# AIMLAB_TESTSTATION_ADC_V1.net
KiCad netlist of a schematic drawn in Altium Designer
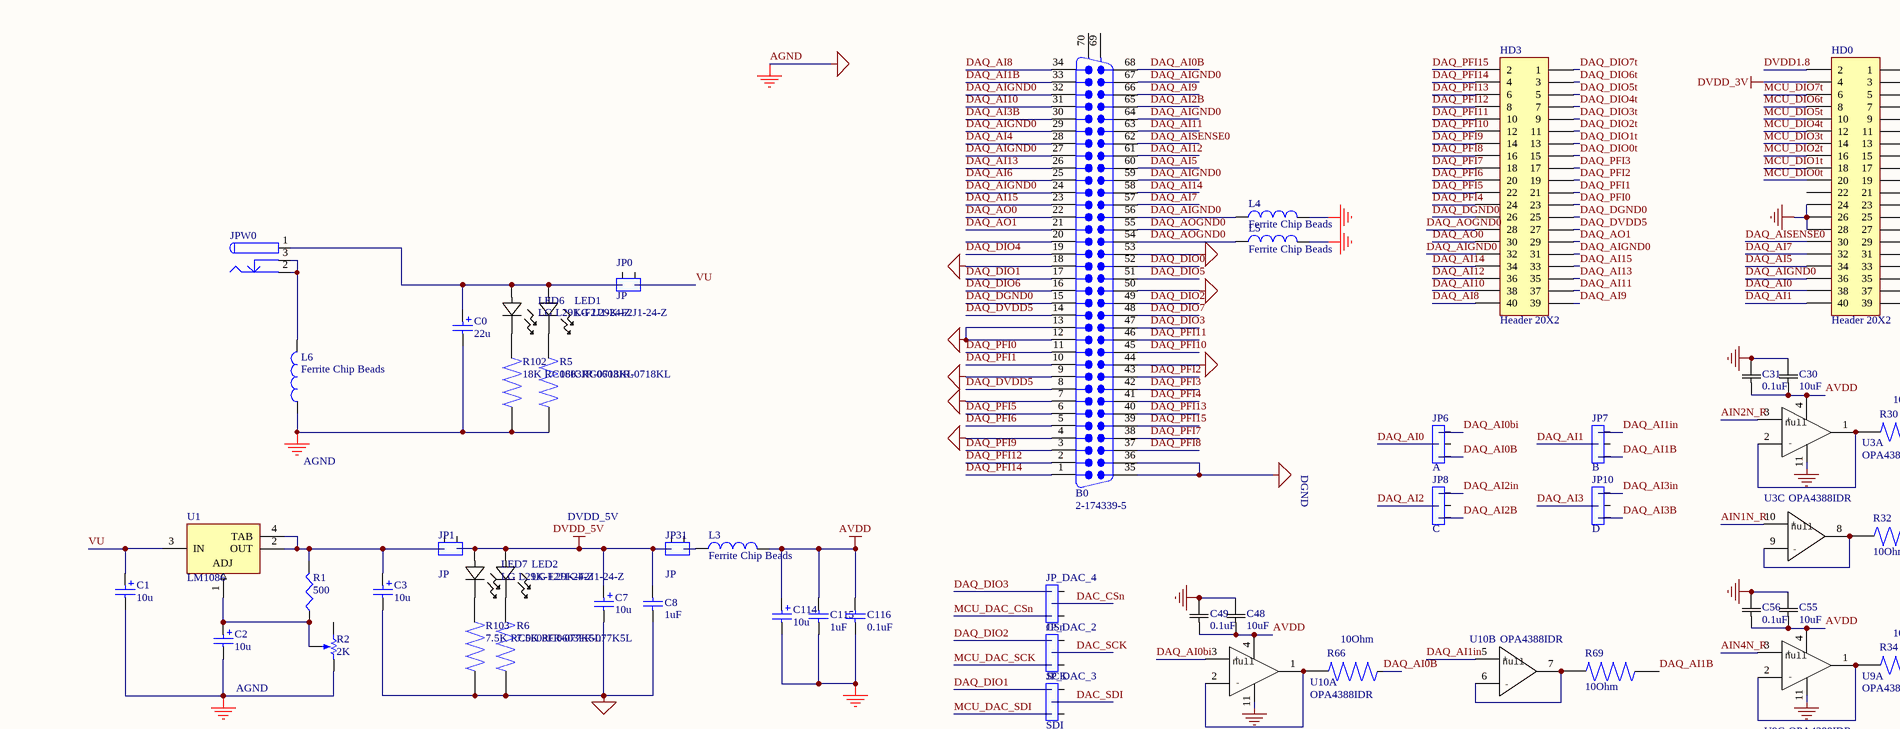
[diagram p0: AIMLAB_TESTSTATION_ADC_V1.schdoc, top left]
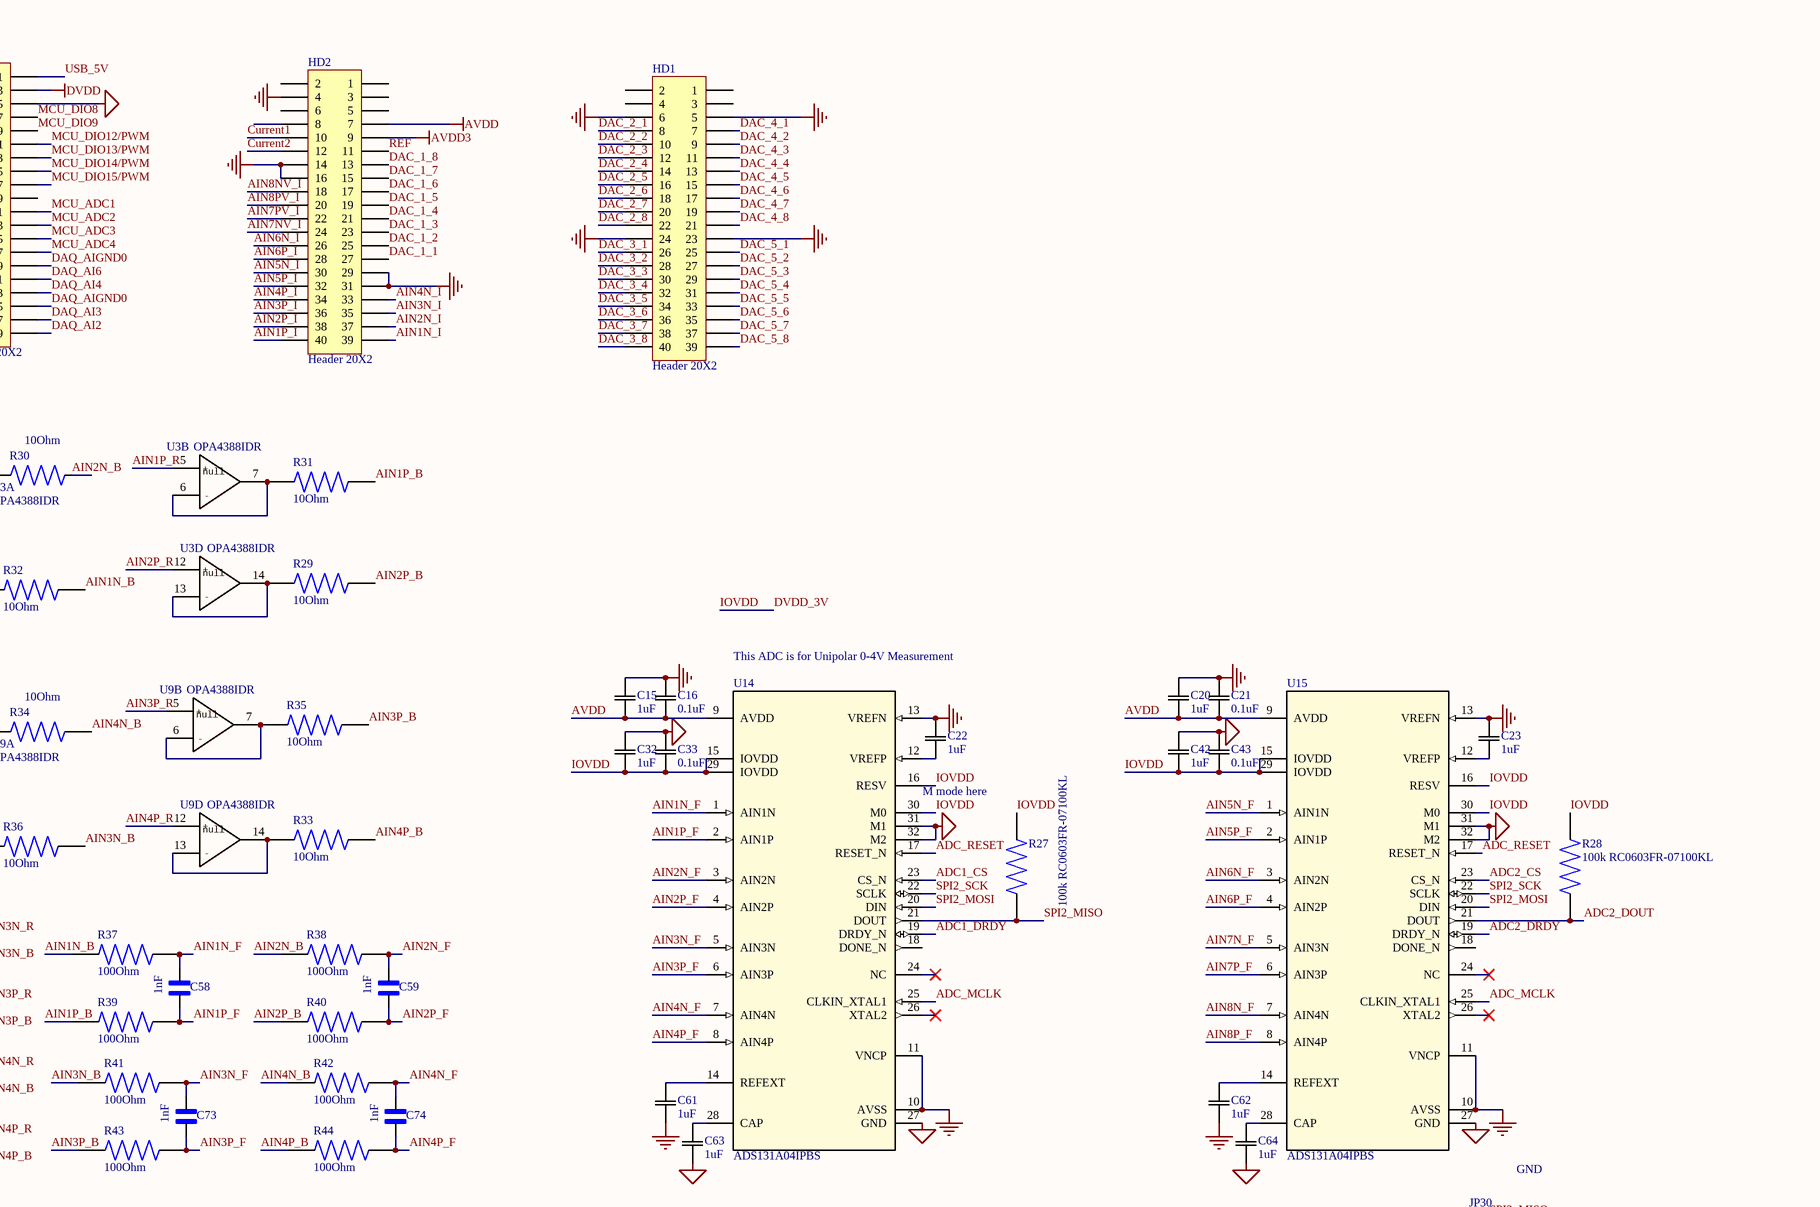
[diagram p1: AIMLAB_TESTSTATION_ADC_V1.schdoc, top right]
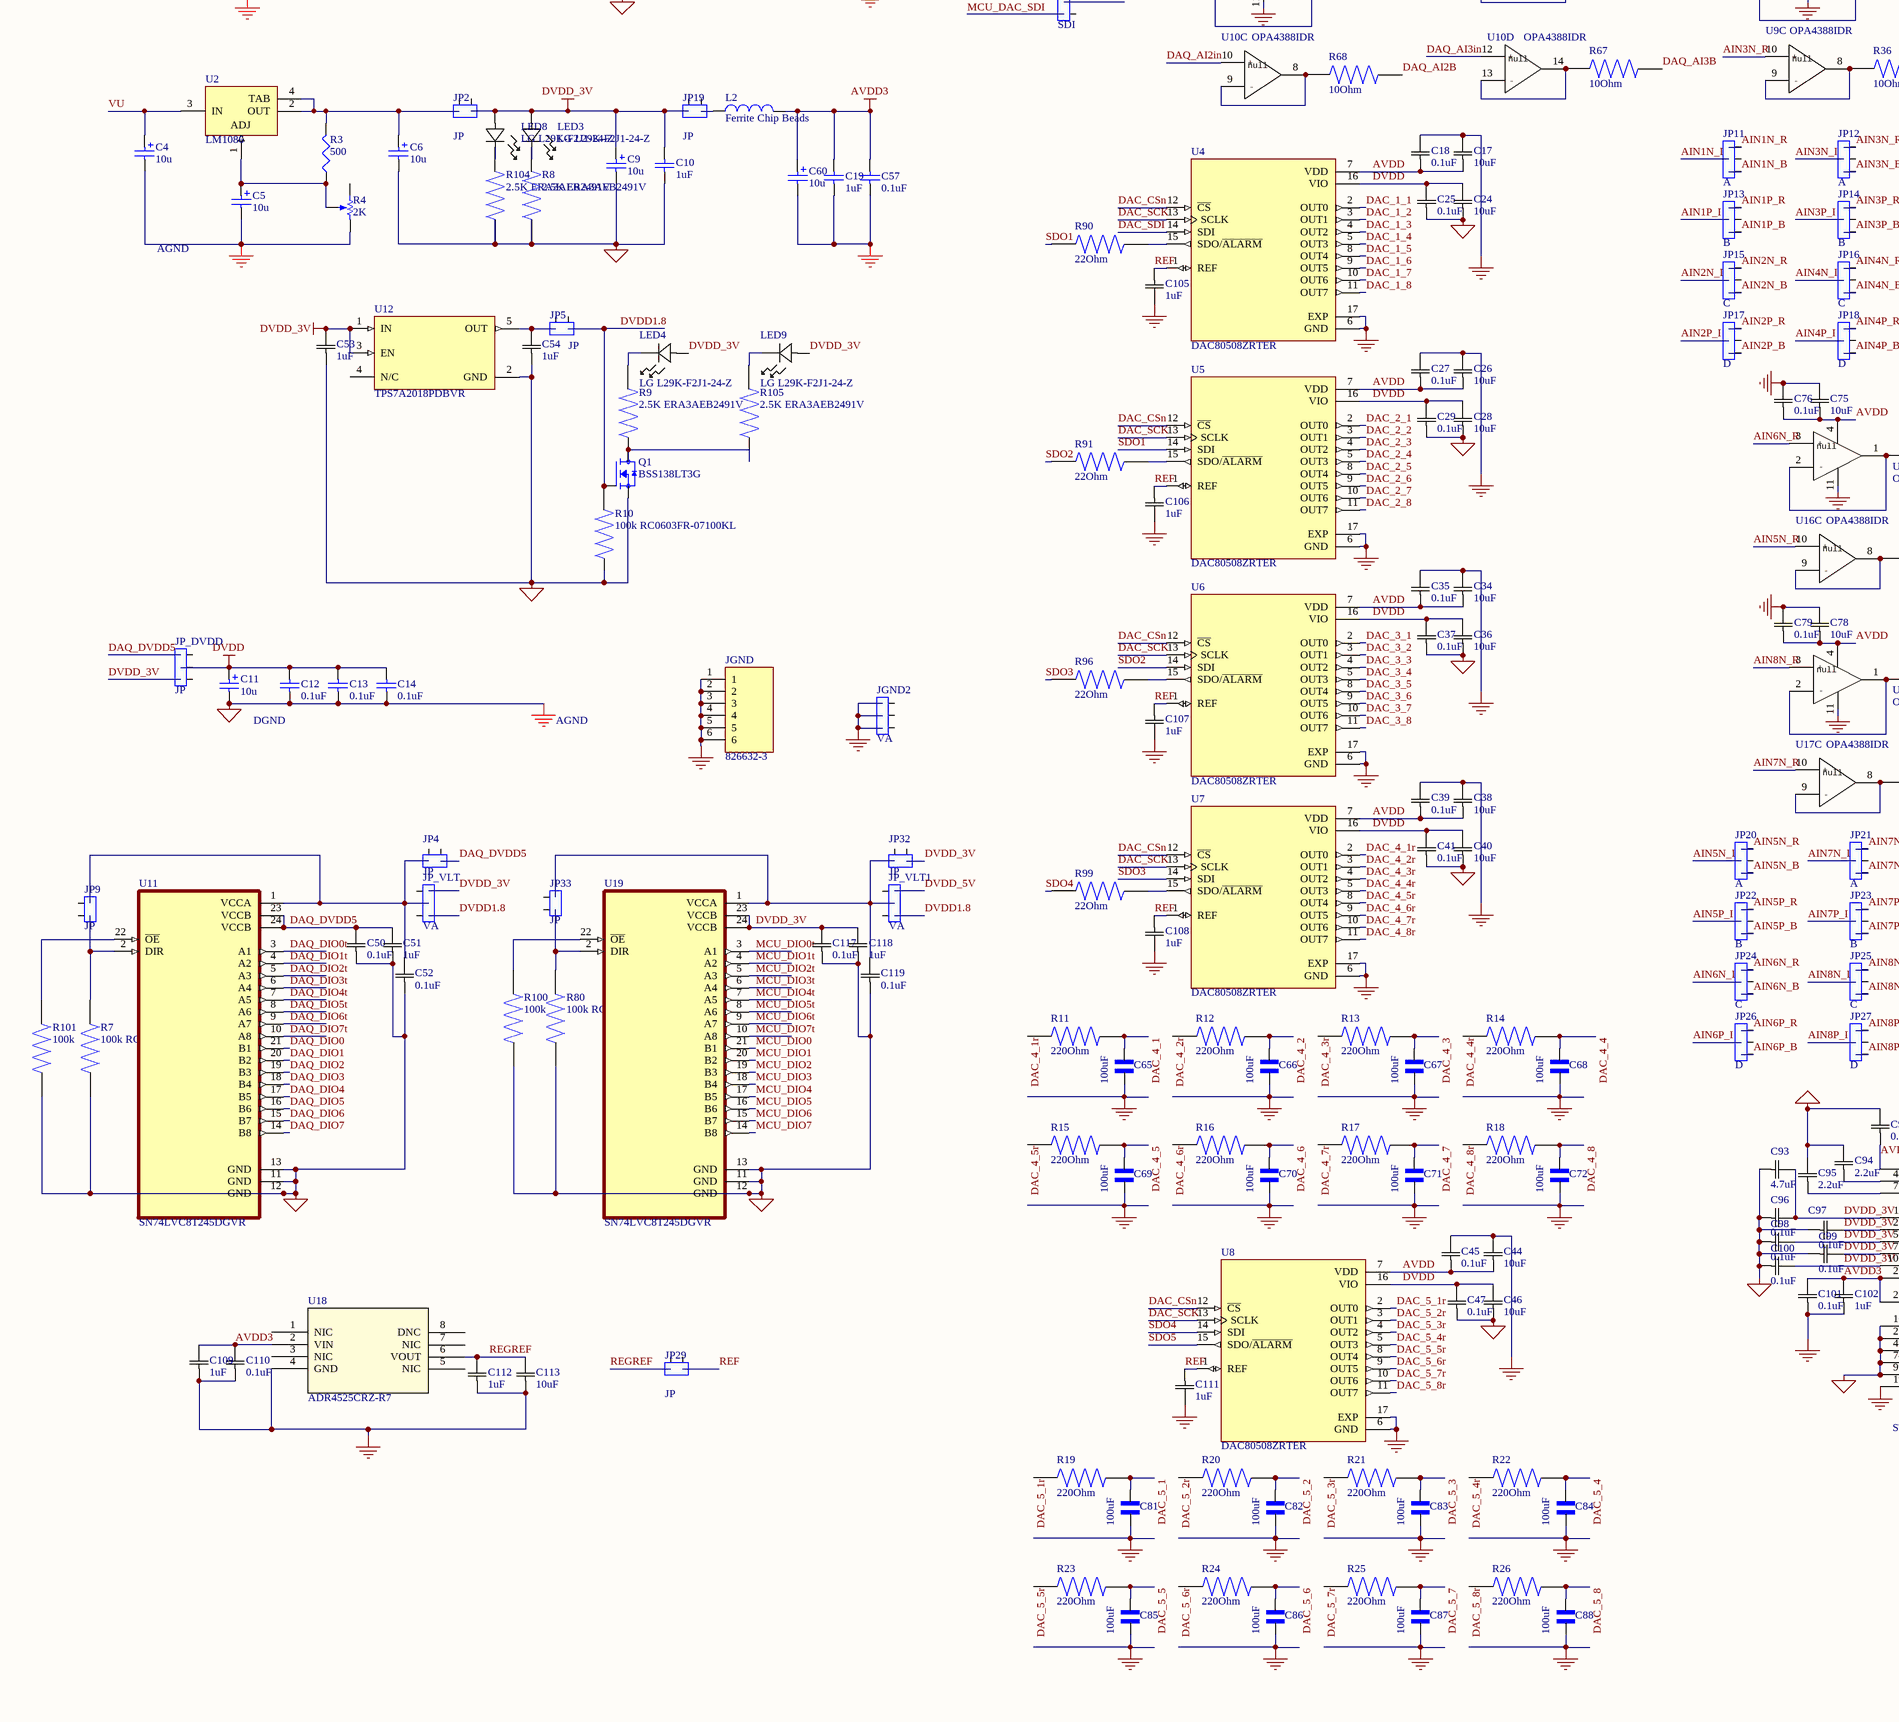
[diagram p2: AIMLAB_TESTSTATION_ADC_V1.schdoc, bottom left]
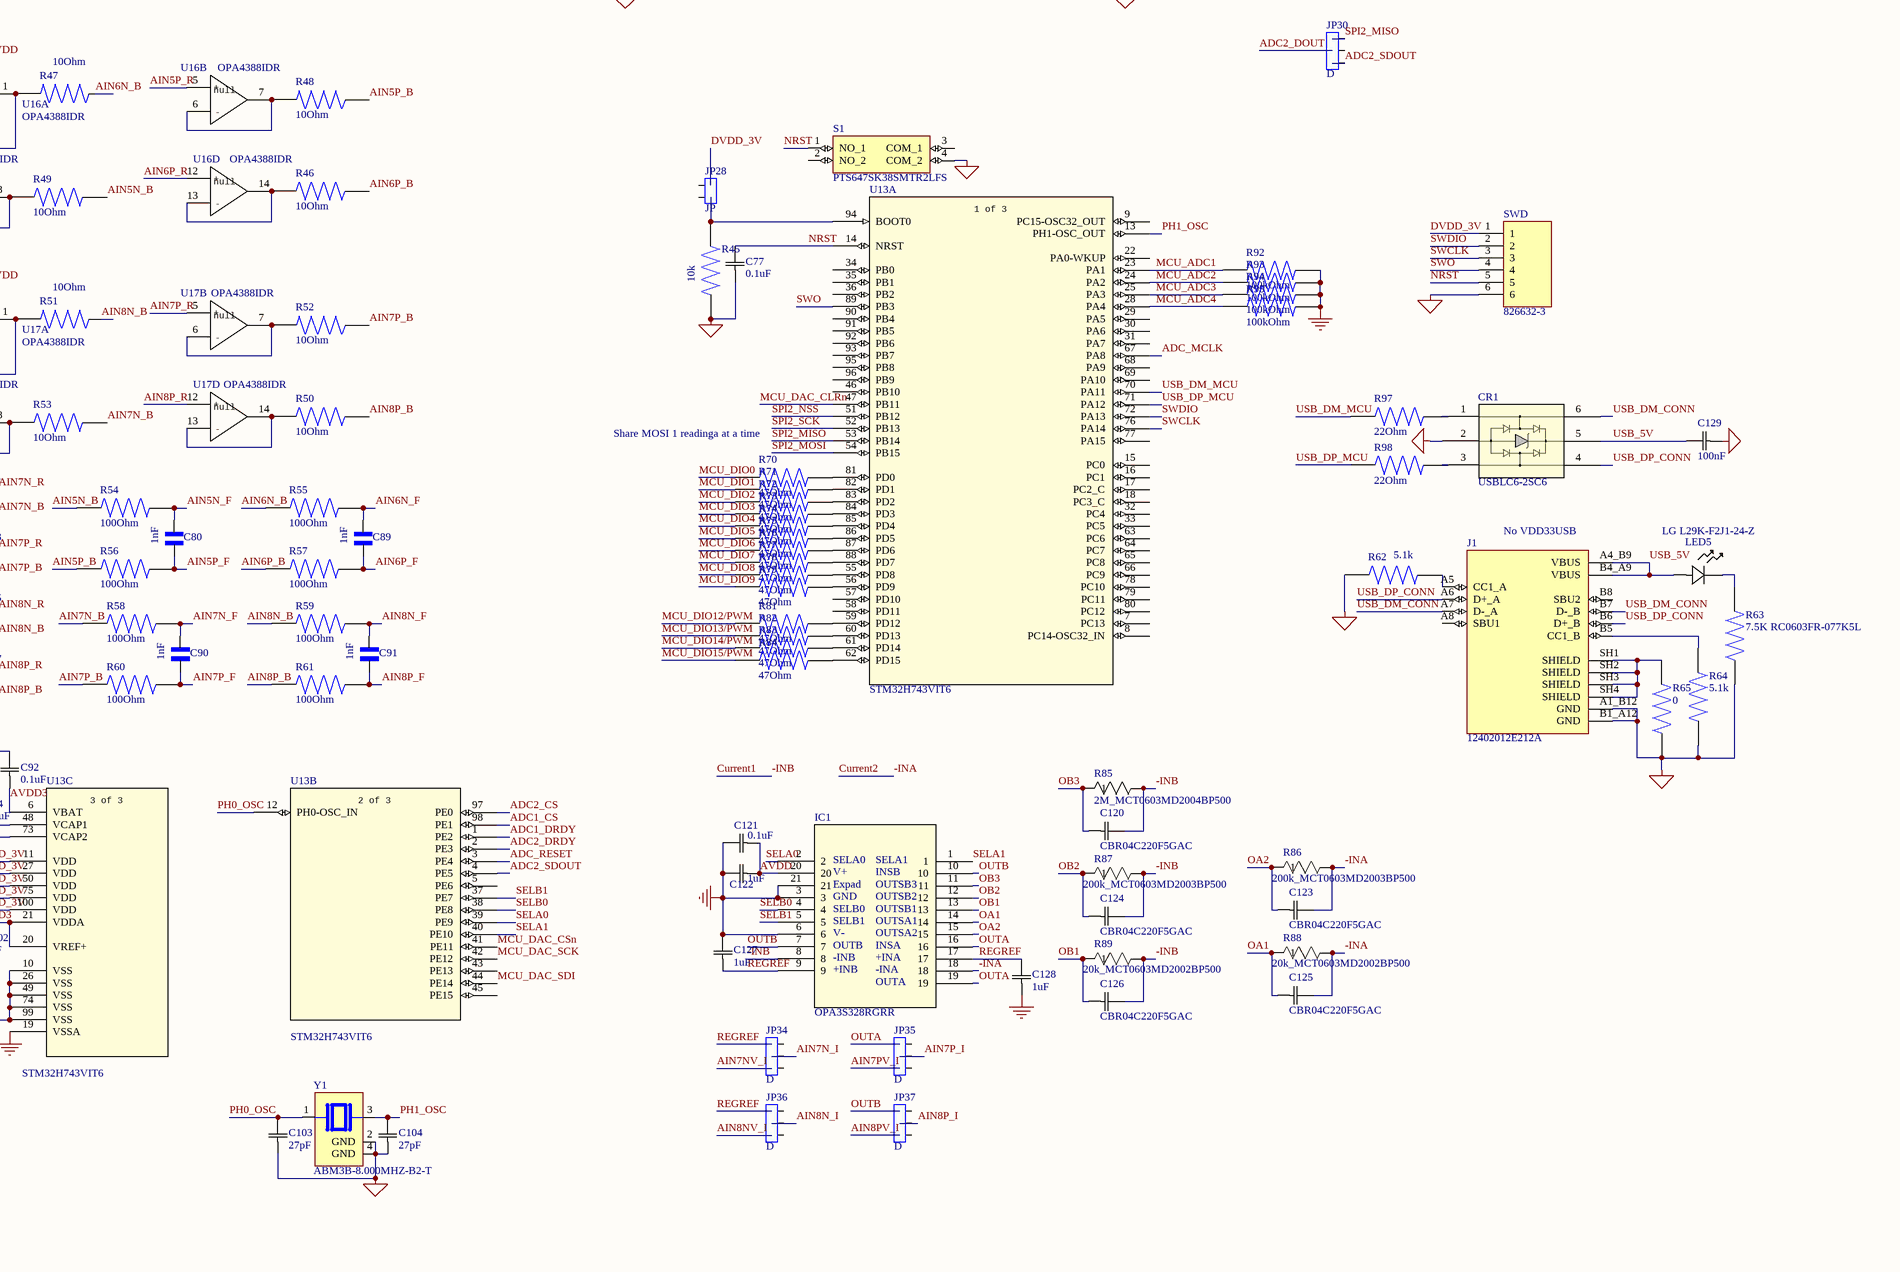
[diagram p3: AIMLAB_TESTSTATION_ADC_V1.schdoc, bottom right]

(export (version "E")
  (design (tool "Eeschema 10.0.6"))
  (components
    (comp (ref "B0")
      (value "2-174339-5")
      (footprint "newconn68:CONN68_5174339_TEC")
      (description "Cap Header, Vertical /M2.5 AMPLIMITE 050 Series II")
      (fields (field (name "PUBLISHER") "Altium Limited"))
      (libsource (lib "AMP D Subminiature 050 Series") (part "2-174339-5"))
    )
    (comp (ref "C0")
      (value "22u")
      (footprint "AimLab_TestStationM-v1.3.1-150922:PolarizedCap")
      (description "Polarized Capacitor (Surface Mount)")
      (fields (field (name "PUBLISHER") "Altium Limited"))
      (libsource (lib "Miscellaneous Devices") (part "Cap Pol3"))
    )
    (comp (ref "C1")
      (value "10u")
      (footprint "AimLab_TestStationM-v1.3.1-150922:PolarizedCap")
      (description "Polarized Capacitor (Surface Mount)")
      (fields (field (name "PUBLISHER") "Altium Limited"))
      (libsource (lib "Miscellaneous Devices") (part "Cap Pol3"))
    )
    (comp (ref "C2")
      (value "10u")
      (footprint "AimLab_TestStationM-v1.3.1-150922:PolarizedCap")
      (description "Polarized Capacitor (Surface Mount)")
      (fields (field (name "PUBLISHER") "Altium Limited"))
      (libsource (lib "Miscellaneous Devices") (part "Cap Pol3"))
    )
    (comp (ref "C3")
      (value "10u")
      (footprint "AimLab_TestStationM-v1.3.1-150922:PolarizedCap")
      (description "Polarized Capacitor (Surface Mount)")
      (fields (field (name "PUBLISHER") "Altium Limited"))
      (libsource (lib "Miscellaneous Devices") (part "Cap Pol3"))
    )
    (comp (ref "C4")
      (value "10u")
      (footprint "AimLab_TestStationM-v1.3.1-150922:PolarizedCap")
      (description "Polarized Capacitor (Surface Mount)")
      (fields (field (name "PUBLISHER") "Altium Limited"))
      (libsource (lib "Miscellaneous Devices") (part "Cap Pol3"))
    )
    (comp (ref "C5")
      (value "10u")
      (footprint "PolarizedCap")
      (description "Polarized Capacitor (Surface Mount)")
      (fields (field (name "PUBLISHER") "Altium Limited"))
      (libsource (lib "Miscellaneous Devices") (part "Cap Pol3"))
    )
    (comp (ref "C6")
      (value "10u")
      (footprint "AimLab_TestStationM-v1.3.1-150922:PolarizedCap")
      (description "Polarized Capacitor (Surface Mount)")
      (fields (field (name "PUBLISHER") "Altium Limited"))
      (libsource (lib "Miscellaneous Devices") (part "Cap Pol3"))
    )
    (comp (ref "C7")
      (value "10u")
      (footprint "AimLab_TestStationM-v1.3.1-150922:PolarizedCap")
      (description "Polarized Capacitor (Surface Mount)")
      (fields (field (name "PUBLISHER") "Altium Limited"))
      (libsource (lib "Miscellaneous Devices") (part "Cap Pol3"))
    )
    (comp (ref "C8")
      (value "1uF")
      (footprint "CAPC2012X140N")
      (description "Capacitor")
      (fields (field (name "PUBLISHER") "Altium Limited"))
      (libsource (lib "Miscellaneous Devices") (part "Cap"))
    )
    (comp (ref "C9")
      (value "10u")
      (footprint "AimLab_TestStationM-v1.3.1-150922:PolarizedCap")
      (description "Polarized Capacitor (Surface Mount)")
      (fields (field (name "PUBLISHER") "Altium Limited"))
      (libsource (lib "Miscellaneous Devices") (part "Cap Pol3"))
    )
    (comp (ref "C10")
      (value "1uF")
      (footprint "CAPC2012X140N")
      (description "Capacitor")
      (fields (field (name "PUBLISHER") "Altium Limited"))
      (libsource (lib "Miscellaneous Devices") (part "Cap"))
    )
    (comp (ref "C11")
      (value "10u")
      (footprint "AimLab_TestStationM-v1.3.1-150922:PolarizedCap")
      (description "Polarized Capacitor (Surface Mount)")
      (fields (field (name "PUBLISHER") "Altium Limited"))
      (libsource (lib "Miscellaneous Devices") (part "Cap Pol3"))
    )
    (comp (ref "C12")
      (value "0.1uF")
      (footprint "CAPC2012X140N")
      (description "Capacitor")
      (fields (field (name "PUBLISHER") "Altium Limited"))
      (libsource (lib "Miscellaneous Devices") (part "Cap"))
    )
    (comp (ref "C13")
      (value "0.1uF")
      (footprint "CAPC2012X140N")
      (description "Capacitor")
      (fields (field (name "PUBLISHER") "Altium Limited"))
      (libsource (lib "Miscellaneous Devices") (part "Cap"))
    )
    (comp (ref "C14")
      (value "0.1uF")
      (footprint "CAPC2012X140N")
      (description "Capacitor")
      (fields (field (name "PUBLISHER") "Altium Limited"))
      (libsource (lib "Miscellaneous Devices") (part "Cap"))
    )
    (comp (ref "C15")
      (value "1uF")
      (footprint "CAPC1608X90")
      (description "No Description Available")
      (fields
        (field (name "MANUFACTURER_PART_NUMBER") "CC0603KRX7R7BB105")
        (field (name "COPYRIGHT") "Copyright (C) 2025 Ultra Librarian. All rights reserved.")
      )
      (libsource (lib "AIMLAB_TESTSTATION-V1.3.1-150922_1") (part "CC0603KRX7R7BB105"))
    )
    (comp (ref "C16")
      (value "0.1uF")
      (footprint "CAPC1608X90")
      (description "No Description Available")
      (fields
        (field (name "MANUFACTURER_PART_NUMBER") "CC0603KRX7R7BB104")
        (field (name "COPYRIGHT") "Copyright (C) 2025 Ultra Librarian. All rights reserved.")
      )
      (libsource (lib "CC0603KRX7R7BB104") (part "CC0603KRX7R7BB104"))
    )
    (comp (ref "C17")
      (value "10uF")
      (footprint "CAPC2012X140N")
      (description "No Description Available")
      (fields
        (field (name "MANUFACTURER_PART_NUMBER") "CL21B106KOQNNNE")
        (field (name "COPYRIGHT") "Copyright (C) 2025 Ultra Librarian. All rights reserved.")
      )
      (libsource (lib "CL21B106KOQNNNE") (part "CL21B106KOQNNNE"))
    )
    (comp (ref "C18")
      (value "0.1uF")
      (footprint "CAPC1608X90")
      (description "No Description Available")
      (fields
        (field (name "MANUFACTURER_PART_NUMBER") "CC0603KRX7R7BB104")
        (field (name "COPYRIGHT") "Copyright (C) 2025 Ultra Librarian. All rights reserved.")
      )
      (libsource (lib "CC0603KRX7R7BB104") (part "CC0603KRX7R7BB104"))
    )
    (comp (ref "C19")
      (value "1uF")
      (footprint "CAPC2012X140N")
      (description "Capacitor")
      (fields (field (name "PUBLISHER") "Altium Limited"))
      (libsource (lib "Miscellaneous Devices") (part "Cap"))
    )
    (comp (ref "C20")
      (value "1uF")
      (footprint "CAPC1608X90")
      (description "No Description Available")
      (fields
        (field (name "MANUFACTURER_PART_NUMBER") "CC0603KRX7R7BB105")
        (field (name "COPYRIGHT") "Copyright (C) 2025 Ultra Librarian. All rights reserved.")
      )
      (libsource (lib "AIMLAB_TESTSTATION-V1.3.1-150922_1") (part "CC0603KRX7R7BB105"))
    )
    (comp (ref "C21")
      (value "0.1uF")
      (footprint "CAPC1608X90")
      (description "No Description Available")
      (fields
        (field (name "MANUFACTURER_PART_NUMBER") "CC0603KRX7R7BB104")
        (field (name "COPYRIGHT") "Copyright (C) 2025 Ultra Librarian. All rights reserved.")
      )
      (libsource (lib "CC0603KRX7R7BB104") (part "CC0603KRX7R7BB104"))
    )
    (comp (ref "C22")
      (value "1uF")
      (footprint "CAPC1608X90")
      (description "No Description Available")
      (fields
        (field (name "MANUFACTURER_PART_NUMBER") "CC0603KRX7R7BB105")
        (field (name "COPYRIGHT") "Copyright (C) 2025 Ultra Librarian. All rights reserved.")
      )
      (libsource (lib "AIMLAB_TESTSTATION-V1.3.1-150922_1") (part "CC0603KRX7R7BB105"))
    )
    (comp (ref "C23")
      (value "1uF")
      (footprint "CAPC1608X90")
      (description "No Description Available")
      (fields
        (field (name "MANUFACTURER_PART_NUMBER") "CC0603KRX7R7BB105")
        (field (name "COPYRIGHT") "Copyright (C) 2025 Ultra Librarian. All rights reserved.")
      )
      (libsource (lib "AIMLAB_TESTSTATION-V1.3.1-150922_1") (part "CC0603KRX7R7BB105"))
    )
    (comp (ref "C24")
      (value "10uF")
      (footprint "CAPC2012X140N")
      (description "No Description Available")
      (fields
        (field (name "MANUFACTURER_PART_NUMBER") "CL21B106KOQNNNE")
        (field (name "COPYRIGHT") "Copyright (C) 2025 Ultra Librarian. All rights reserved.")
      )
      (libsource (lib "CL21B106KOQNNNE") (part "CL21B106KOQNNNE"))
    )
    (comp (ref "C25")
      (value "0.1uF")
      (footprint "CAPC1608X90")
      (description "No Description Available")
      (fields
        (field (name "MANUFACTURER_PART_NUMBER") "CC0603KRX7R7BB104")
        (field (name "COPYRIGHT") "Copyright (C) 2025 Ultra Librarian. All rights reserved.")
      )
      (libsource (lib "CC0603KRX7R7BB104") (part "CC0603KRX7R7BB104"))
    )
    (comp (ref "C26")
      (value "10uF")
      (footprint "CAPC2012X140N")
      (description "No Description Available")
      (fields
        (field (name "MANUFACTURER_PART_NUMBER") "CL21B106KOQNNNE")
        (field (name "COPYRIGHT") "Copyright (C) 2025 Ultra Librarian. All rights reserved.")
      )
      (libsource (lib "CL21B106KOQNNNE") (part "CL21B106KOQNNNE"))
    )
    (comp (ref "C27")
      (value "0.1uF")
      (footprint "CAPC1608X90")
      (description "No Description Available")
      (fields
        (field (name "MANUFACTURER_PART_NUMBER") "CC0603KRX7R7BB104")
        (field (name "COPYRIGHT") "Copyright (C) 2025 Ultra Librarian. All rights reserved.")
      )
      (libsource (lib "CC0603KRX7R7BB104") (part "CC0603KRX7R7BB104"))
    )
    (comp (ref "C28")
      (value "10uF")
      (footprint "CAPC2012X140N")
      (description "No Description Available")
      (fields
        (field (name "MANUFACTURER_PART_NUMBER") "CL21B106KOQNNNE")
        (field (name "COPYRIGHT") "Copyright (C) 2025 Ultra Librarian. All rights reserved.")
      )
      (libsource (lib "CL21B106KOQNNNE") (part "CL21B106KOQNNNE"))
    )
    (comp (ref "C29")
      (value "0.1uF")
      (footprint "CAPC1608X90")
      (description "No Description Available")
      (fields
        (field (name "MANUFACTURER_PART_NUMBER") "CC0603KRX7R7BB104")
        (field (name "COPYRIGHT") "Copyright (C) 2025 Ultra Librarian. All rights reserved.")
      )
      (libsource (lib "CC0603KRX7R7BB104") (part "CC0603KRX7R7BB104"))
    )
    (comp (ref "C30")
      (value "10uF")
      (footprint "CAPC2012X140N")
      (description "No Description Available")
      (fields
        (field (name "MANUFACTURER_PART_NUMBER") "CL21B106KOQNNNE")
        (field (name "COPYRIGHT") "Copyright (C) 2025 Ultra Librarian. All rights reserved.")
      )
      (libsource (lib "CL21B106KOQNNNE") (part "CL21B106KOQNNNE"))
    )
    (comp (ref "C31")
      (value "0.1uF")
      (footprint "CAPC1608X90")
      (description "No Description Available")
      (fields
        (field (name "MANUFACTURER_PART_NUMBER") "CC0603KRX7R7BB104")
        (field (name "COPYRIGHT") "Copyright (C) 2025 Ultra Librarian. All rights reserved.")
      )
      (libsource (lib "CC0603KRX7R7BB104") (part "CC0603KRX7R7BB104"))
    )
    (comp (ref "C32")
      (value "1uF")
      (footprint "CAPC1608X90")
      (description "No Description Available")
      (fields
        (field (name "MANUFACTURER_PART_NUMBER") "CC0603KRX7R7BB105")
        (field (name "COPYRIGHT") "Copyright (C) 2025 Ultra Librarian. All rights reserved.")
      )
      (libsource (lib "AIMLAB_TESTSTATION-V1.3.1-150922_1") (part "CC0603KRX7R7BB105"))
    )
    (comp (ref "C33")
      (value "0.1uF")
      (footprint "CAPC1608X90")
      (description "No Description Available")
      (fields
        (field (name "MANUFACTURER_PART_NUMBER") "CC0603KRX7R7BB104")
        (field (name "COPYRIGHT") "Copyright (C) 2025 Ultra Librarian. All rights reserved.")
      )
      (libsource (lib "CC0603KRX7R7BB104") (part "CC0603KRX7R7BB104"))
    )
    (comp (ref "C34")
      (value "10uF")
      (footprint "CAPC2012X140N")
      (description "No Description Available")
      (fields
        (field (name "MANUFACTURER_PART_NUMBER") "CL21B106KOQNNNE")
        (field (name "COPYRIGHT") "Copyright (C) 2025 Ultra Librarian. All rights reserved.")
      )
      (libsource (lib "CL21B106KOQNNNE") (part "CL21B106KOQNNNE"))
    )
    (comp (ref "C35")
      (value "0.1uF")
      (footprint "CAPC1608X90")
      (description "No Description Available")
      (fields
        (field (name "MANUFACTURER_PART_NUMBER") "CC0603KRX7R7BB104")
        (field (name "COPYRIGHT") "Copyright (C) 2025 Ultra Librarian. All rights reserved.")
      )
      (libsource (lib "CC0603KRX7R7BB104") (part "CC0603KRX7R7BB104"))
    )
    (comp (ref "C36")
      (value "10uF")
      (footprint "CAPC2012X140N")
      (description "No Description Available")
      (fields
        (field (name "MANUFACTURER_PART_NUMBER") "CL21B106KOQNNNE")
        (field (name "COPYRIGHT") "Copyright (C) 2025 Ultra Librarian. All rights reserved.")
      )
      (libsource (lib "CL21B106KOQNNNE") (part "CL21B106KOQNNNE"))
    )
    (comp (ref "C37")
      (value "0.1uF")
      (footprint "CAPC1608X90")
      (description "No Description Available")
      (fields
        (field (name "MANUFACTURER_PART_NUMBER") "CC0603KRX7R7BB104")
        (field (name "COPYRIGHT") "Copyright (C) 2025 Ultra Librarian. All rights reserved.")
      )
      (libsource (lib "CC0603KRX7R7BB104") (part "CC0603KRX7R7BB104"))
    )
    (comp (ref "C38")
      (value "10uF")
      (footprint "CAPC2012X140N")
      (description "No Description Available")
      (fields
        (field (name "MANUFACTURER_PART_NUMBER") "CL21B106KOQNNNE")
        (field (name "COPYRIGHT") "Copyright (C) 2025 Ultra Librarian. All rights reserved.")
      )
      (libsource (lib "CL21B106KOQNNNE") (part "CL21B106KOQNNNE"))
    )
    (comp (ref "C39")
      (value "0.1uF")
      (footprint "CAPC1608X90")
      (description "No Description Available")
      (fields
        (field (name "MANUFACTURER_PART_NUMBER") "CC0603KRX7R7BB104")
        (field (name "COPYRIGHT") "Copyright (C) 2025 Ultra Librarian. All rights reserved.")
      )
      (libsource (lib "CC0603KRX7R7BB104") (part "CC0603KRX7R7BB104"))
    )
    (comp (ref "C40")
      (value "10uF")
      (footprint "CAPC2012X140N")
      (description "No Description Available")
      (fields
        (field (name "MANUFACTURER_PART_NUMBER") "CL21B106KOQNNNE")
        (field (name "COPYRIGHT") "Copyright (C) 2025 Ultra Librarian. All rights reserved.")
      )
      (libsource (lib "CL21B106KOQNNNE") (part "CL21B106KOQNNNE"))
    )
    (comp (ref "C41")
      (value "0.1uF")
      (footprint "CAPC1608X90")
      (description "No Description Available")
      (fields
        (field (name "MANUFACTURER_PART_NUMBER") "CC0603KRX7R7BB104")
        (field (name "COPYRIGHT") "Copyright (C) 2025 Ultra Librarian. All rights reserved.")
      )
      (libsource (lib "CC0603KRX7R7BB104") (part "CC0603KRX7R7BB104"))
    )
    (comp (ref "C42")
      (value "1uF")
      (footprint "CAPC1608X90")
      (description "No Description Available")
      (fields
        (field (name "MANUFACTURER_PART_NUMBER") "CC0603KRX7R7BB105")
        (field (name "COPYRIGHT") "Copyright (C) 2025 Ultra Librarian. All rights reserved.")
      )
      (libsource (lib "AIMLAB_TESTSTATION-V1.3.1-150922_1") (part "CC0603KRX7R7BB105"))
    )
    (comp (ref "C43")
      (value "0.1uF")
      (footprint "CAPC1608X90")
      (description "No Description Available")
      (fields
        (field (name "MANUFACTURER_PART_NUMBER") "CC0603KRX7R7BB104")
        (field (name "COPYRIGHT") "Copyright (C) 2025 Ultra Librarian. All rights reserved.")
      )
      (libsource (lib "CC0603KRX7R7BB104") (part "CC0603KRX7R7BB104"))
    )
    (comp (ref "C44")
      (value "10uF")
      (footprint "CAPC2012X140N")
      (description "No Description Available")
      (fields
        (field (name "MANUFACTURER_PART_NUMBER") "CL21B106KOQNNNE")
        (field (name "COPYRIGHT") "Copyright (C) 2025 Ultra Librarian. All rights reserved.")
      )
      (libsource (lib "CL21B106KOQNNNE") (part "CL21B106KOQNNNE"))
    )
    (comp (ref "C45")
      (value "0.1uF")
      (footprint "CAPC1608X90")
      (description "No Description Available")
      (fields
        (field (name "MANUFACTURER_PART_NUMBER") "CC0603KRX7R7BB104")
        (field (name "COPYRIGHT") "Copyright (C) 2025 Ultra Librarian. All rights reserved.")
      )
      (libsource (lib "CC0603KRX7R7BB104") (part "CC0603KRX7R7BB104"))
    )
    (comp (ref "C46")
      (value "10uF")
      (footprint "CAPC2012X140N")
      (description "No Description Available")
      (fields
        (field (name "MANUFACTURER_PART_NUMBER") "CL21B106KOQNNNE")
        (field (name "COPYRIGHT") "Copyright (C) 2025 Ultra Librarian. All rights reserved.")
      )
      (libsource (lib "CL21B106KOQNNNE") (part "CL21B106KOQNNNE"))
    )
    (comp (ref "C47")
      (value "0.1uF")
      (footprint "CAPC1608X90")
      (description "No Description Available")
      (fields
        (field (name "MANUFACTURER_PART_NUMBER") "CC0603KRX7R7BB104")
        (field (name "COPYRIGHT") "Copyright (C) 2025 Ultra Librarian. All rights reserved.")
      )
      (libsource (lib "CC0603KRX7R7BB104") (part "CC0603KRX7R7BB104"))
    )
    (comp (ref "C48")
      (value "10uF")
      (footprint "CAPC2012X140N")
      (description "No Description Available")
      (fields
        (field (name "MANUFACTURER_PART_NUMBER") "CL21B106KOQNNNE")
        (field (name "COPYRIGHT") "Copyright (C) 2025 Ultra Librarian. All rights reserved.")
      )
      (libsource (lib "CL21B106KOQNNNE") (part "CL21B106KOQNNNE"))
    )
    (comp (ref "C49")
      (value "0.1uF")
      (footprint "CAPC1608X90")
      (description "No Description Available")
      (fields
        (field (name "MANUFACTURER_PART_NUMBER") "CC0603KRX7R7BB104")
        (field (name "COPYRIGHT") "Copyright (C) 2025 Ultra Librarian. All rights reserved.")
      )
      (libsource (lib "CC0603KRX7R7BB104") (part "CC0603KRX7R7BB104"))
    )
    (comp (ref "C50")
      (value "0.1uF")
      (footprint "CAPC1608X90")
      (description "No Description Available")
      (fields
        (field (name "MANUFACTURER_PART_NUMBER") "CC0603KRX7R7BB104")
        (field (name "COPYRIGHT") "Copyright (C) 2025 Ultra Librarian. All rights reserved.")
      )
      (libsource (lib "AIMLAB_TESTSTATION-V1.3.1-150922_1") (part "CC0603KRX7R7BB104"))
    )
    (comp (ref "C51")
      (value "1uF")
      (footprint "CAPC1608X90")
      (description "No Description Available")
      (fields
        (field (name "MANUFACTURER_PART_NUMBER") "CC0603KRX7R7BB105")
        (field (name "COPYRIGHT") "Copyright (C) 2025 Ultra Librarian. All rights reserved.")
      )
      (libsource (lib "AIMLAB_TESTSTATION-V1.3.1-150922_1") (part "CC0603KRX7R7BB105"))
    )
    (comp (ref "C52")
      (value "0.1uF")
      (footprint "CAPC1608X90")
      (description "No Description Available")
      (fields
        (field (name "MANUFACTURER_PART_NUMBER") "CC0603KRX7R7BB104")
        (field (name "COPYRIGHT") "Copyright (C) 2025 Ultra Librarian. All rights reserved.")
      )
      (libsource (lib "AIMLAB_TESTSTATION-V1.3.1-150922_1") (part "CC0603KRX7R7BB104"))
    )
    (comp (ref "C53")
      (value "1uF")
      (footprint "CAPC2012X140N")
      (description "No Description Available")
      (fields
        (field (name "MANUFACTURER_PART_NUMBER") "CC0603KRX7R7BB105")
        (field (name "COPYRIGHT") "Copyright (C) 2025 Ultra Librarian. All rights reserved.")
      )
      (libsource (lib "CC0603KRX7R7BB105") (part "CC0603KRX7R7BB105"))
    )
    (comp (ref "C54")
      (value "1uF")
      (footprint "CAPC2012X140N")
      (description "No Description Available")
      (fields
        (field (name "MANUFACTURER_PART_NUMBER") "CC0603KRX7R7BB105")
        (field (name "COPYRIGHT") "Copyright (C) 2025 Ultra Librarian. All rights reserved.")
      )
      (libsource (lib "CC0603KRX7R7BB105") (part "CC0603KRX7R7BB105"))
    )
    (comp (ref "C55")
      (value "10uF")
      (footprint "CAPC2012X140N")
      (description "No Description Available")
      (fields
        (field (name "MANUFACTURER_PART_NUMBER") "CL21B106KOQNNNE")
        (field (name "COPYRIGHT") "Copyright (C) 2025 Ultra Librarian. All rights reserved.")
      )
      (libsource (lib "CL21B106KOQNNNE") (part "CL21B106KOQNNNE"))
    )
    (comp (ref "C56")
      (value "0.1uF")
      (footprint "CAPC1608X90")
      (description "No Description Available")
      (fields
        (field (name "MANUFACTURER_PART_NUMBER") "CC0603KRX7R7BB104")
        (field (name "COPYRIGHT") "Copyright (C) 2025 Ultra Librarian. All rights reserved.")
      )
      (libsource (lib "CC0603KRX7R7BB104") (part "CC0603KRX7R7BB104"))
    )
    (comp (ref "C57")
      (value "0.1uF")
      (footprint "CAPC2012X140N")
      (description "Capacitor")
      (fields (field (name "PUBLISHER") "Altium Limited"))
      (libsource (lib "Miscellaneous Devices") (part "Cap"))
    )
    (comp (ref "C58")
      (value "1nF")
      (footprint "CAPC2012X145N")
      (description "100 ÂµF Â±20% 6.3V Ceramic Capacitor X5R 0805 (2012 Metric)")
      (fields (field (name "MF") "Murata") (field (name "MP") "GRM21BR60J107ME15L"))
      (libsource (lib "GRM21BR60J107ME15L") (part "GRM21BR60J107ME15L"))
    )
    (comp (ref "C59")
      (value "1nF")
      (footprint "CAPC2012X145N")
      (description "100 ÂµF Â±20% 6.3V Ceramic Capacitor X5R 0805 (2012 Metric)")
      (fields (field (name "MF") "Murata") (field (name "MP") "GRM21BR60J107ME15L"))
      (libsource (lib "GRM21BR60J107ME15L") (part "GRM21BR60J107ME15L"))
    )
    (comp (ref "C60")
      (value "10u")
      (footprint "AimLab_TestStationM-v1.3.1-150922:PolarizedCap")
      (description "Polarized Capacitor (Surface Mount)")
      (fields (field (name "PUBLISHER") "Altium Limited"))
      (libsource (lib "Miscellaneous Devices") (part "Cap Pol3"))
    )
    (comp (ref "C61")
      (value "1uF")
      (footprint "CAPC1608X90")
      (description "No Description Available")
      (fields
        (field (name "MANUFACTURER_PART_NUMBER") "CC0603KRX7R7BB105")
        (field (name "COPYRIGHT") "Copyright (C) 2025 Ultra Librarian. All rights reserved.")
      )
      (libsource (lib "AIMLAB_TESTSTATION-V1.3.1-150922_1") (part "CC0603KRX7R7BB105"))
    )
    (comp (ref "C62")
      (value "1uF")
      (footprint "CAPC1608X90")
      (description "No Description Available")
      (fields
        (field (name "MANUFACTURER_PART_NUMBER") "CC0603KRX7R7BB105")
        (field (name "COPYRIGHT") "Copyright (C) 2025 Ultra Librarian. All rights reserved.")
      )
      (libsource (lib "AIMLAB_TESTSTATION-V1.3.1-150922_1") (part "CC0603KRX7R7BB105"))
    )
    (comp (ref "C63")
      (value "1uF")
      (footprint "CAPC1608X90")
      (description "No Description Available")
      (fields
        (field (name "MANUFACTURER_PART_NUMBER") "CC0603KRX7R7BB105")
        (field (name "COPYRIGHT") "Copyright (C) 2025 Ultra Librarian. All rights reserved.")
      )
      (libsource (lib "AIMLAB_TESTSTATION-V1.3.1-150922_1") (part "CC0603KRX7R7BB105"))
    )
    (comp (ref "C64")
      (value "1uF")
      (footprint "CAPC1608X90")
      (description "No Description Available")
      (fields
        (field (name "MANUFACTURER_PART_NUMBER") "CC0603KRX7R7BB105")
        (field (name "COPYRIGHT") "Copyright (C) 2025 Ultra Librarian. All rights reserved.")
      )
      (libsource (lib "AIMLAB_TESTSTATION-V1.3.1-150922_1") (part "CC0603KRX7R7BB105"))
    )
    (comp (ref "C65")
      (value "100uF")
      (footprint "CAPC2012X145N")
      (description "100 ÂµF Â±20% 6.3V Ceramic Capacitor X5R 0805 (2012 Metric)")
      (fields (field (name "MF") "Murata") (field (name "MP") "GRM21BR60J107ME15L"))
      (libsource (lib "GRM21BR60J107ME15L") (part "GRM21BR60J107ME15L"))
    )
    (comp (ref "C66")
      (value "100uF")
      (footprint "CAPC2012X145N")
      (description "100 ÂµF Â±20% 6.3V Ceramic Capacitor X5R 0805 (2012 Metric)")
      (fields (field (name "MF") "Murata") (field (name "MP") "GRM21BR60J107ME15L"))
      (libsource (lib "GRM21BR60J107ME15L") (part "GRM21BR60J107ME15L"))
    )
    (comp (ref "C67")
      (value "100uF")
      (footprint "CAPC2012X145N")
      (description "100 ÂµF Â±20% 6.3V Ceramic Capacitor X5R 0805 (2012 Metric)")
      (fields (field (name "MF") "Murata") (field (name "MP") "GRM21BR60J107ME15L"))
      (libsource (lib "GRM21BR60J107ME15L") (part "GRM21BR60J107ME15L"))
    )
    (comp (ref "C68")
      (value "100uF")
      (footprint "CAPC2012X145N")
      (description "100 ÂµF Â±20% 6.3V Ceramic Capacitor X5R 0805 (2012 Metric)")
      (fields (field (name "MF") "Murata") (field (name "MP") "GRM21BR60J107ME15L"))
      (libsource (lib "GRM21BR60J107ME15L") (part "GRM21BR60J107ME15L"))
    )
    (comp (ref "C69")
      (value "100uF")
      (footprint "CAPC2012X145N")
      (description "100 ÂµF Â±20% 6.3V Ceramic Capacitor X5R 0805 (2012 Metric)")
      (fields (field (name "MF") "Murata") (field (name "MP") "GRM21BR60J107ME15L"))
      (libsource (lib "GRM21BR60J107ME15L") (part "GRM21BR60J107ME15L"))
    )
    (comp (ref "C70")
      (value "100uF")
      (footprint "CAPC2012X145N")
      (description "100 ÂµF Â±20% 6.3V Ceramic Capacitor X5R 0805 (2012 Metric)")
      (fields (field (name "MF") "Murata") (field (name "MP") "GRM21BR60J107ME15L"))
      (libsource (lib "GRM21BR60J107ME15L") (part "GRM21BR60J107ME15L"))
    )
    (comp (ref "C71")
      (value "100uF")
      (footprint "CAPC2012X145N")
      (description "100 ÂµF Â±20% 6.3V Ceramic Capacitor X5R 0805 (2012 Metric)")
      (fields (field (name "MF") "Murata") (field (name "MP") "GRM21BR60J107ME15L"))
      (libsource (lib "GRM21BR60J107ME15L") (part "GRM21BR60J107ME15L"))
    )
    (comp (ref "C72")
      (value "100uF")
      (footprint "CAPC2012X145N")
      (description "100 ÂµF Â±20% 6.3V Ceramic Capacitor X5R 0805 (2012 Metric)")
      (fields (field (name "MF") "Murata") (field (name "MP") "GRM21BR60J107ME15L"))
      (libsource (lib "GRM21BR60J107ME15L") (part "GRM21BR60J107ME15L"))
    )
    (comp (ref "C73")
      (value "1nF")
      (footprint "CAPC2012X145N")
      (description "100 ÂµF Â±20% 6.3V Ceramic Capacitor X5R 0805 (2012 Metric)")
      (fields (field (name "MF") "Murata") (field (name "MP") "GRM21BR60J107ME15L"))
      (libsource (lib "GRM21BR60J107ME15L") (part "GRM21BR60J107ME15L"))
    )
    (comp (ref "C74")
      (value "1nF")
      (footprint "CAPC2012X145N")
      (description "100 ÂµF Â±20% 6.3V Ceramic Capacitor X5R 0805 (2012 Metric)")
      (fields (field (name "MF") "Murata") (field (name "MP") "GRM21BR60J107ME15L"))
      (libsource (lib "GRM21BR60J107ME15L") (part "GRM21BR60J107ME15L"))
    )
    (comp (ref "C75")
      (value "10uF")
      (footprint "CAPC2012X140N")
      (description "No Description Available")
      (fields
        (field (name "MANUFACTURER_PART_NUMBER") "CL21B106KOQNNNE")
        (field (name "COPYRIGHT") "Copyright (C) 2025 Ultra Librarian. All rights reserved.")
      )
      (libsource (lib "CL21B106KOQNNNE") (part "CL21B106KOQNNNE"))
    )
    (comp (ref "C76")
      (value "0.1uF")
      (footprint "CAPC1608X90")
      (description "No Description Available")
      (fields
        (field (name "MANUFACTURER_PART_NUMBER") "CC0603KRX7R7BB104")
        (field (name "COPYRIGHT") "Copyright (C) 2025 Ultra Librarian. All rights reserved.")
      )
      (libsource (lib "CC0603KRX7R7BB104") (part "CC0603KRX7R7BB104"))
    )
    (comp (ref "C77")
      (value "0.1uF")
      (footprint "CAPC1608X90")
      (description "No Description Available")
      (fields
        (field (name "MANUFACTURER_PART_NUMBER") "CC0603KRX7R7BB104")
        (field (name "COPYRIGHT") "Copyright (C) 2025 Ultra Librarian. All rights reserved.")
      )
      (libsource (lib "CC0603KRX7R7BB104") (part "CC0603KRX7R7BB104"))
    )
    (comp (ref "C78")
      (value "10uF")
      (footprint "CAPC2012X140N")
      (description "No Description Available")
      (fields
        (field (name "MANUFACTURER_PART_NUMBER") "CL21B106KOQNNNE")
        (field (name "COPYRIGHT") "Copyright (C) 2025 Ultra Librarian. All rights reserved.")
      )
      (libsource (lib "CL21B106KOQNNNE") (part "CL21B106KOQNNNE"))
    )
    (comp (ref "C79")
      (value "0.1uF")
      (footprint "CAPC1608X90")
      (description "No Description Available")
      (fields
        (field (name "MANUFACTURER_PART_NUMBER") "CC0603KRX7R7BB104")
        (field (name "COPYRIGHT") "Copyright (C) 2025 Ultra Librarian. All rights reserved.")
      )
      (libsource (lib "CC0603KRX7R7BB104") (part "CC0603KRX7R7BB104"))
    )
    (comp (ref "C80")
      (value "1nF")
      (footprint "CAPC2012X145N")
      (description "100 ÂµF Â±20% 6.3V Ceramic Capacitor X5R 0805 (2012 Metric)")
      (fields (field (name "MF") "Murata") (field (name "MP") "GRM21BR60J107ME15L"))
      (libsource (lib "GRM21BR60J107ME15L") (part "GRM21BR60J107ME15L"))
    )
    (comp (ref "C81")
      (value "100uF")
      (footprint "CAPC2012X145N")
      (description "100 ÂµF Â±20% 6.3V Ceramic Capacitor X5R 0805 (2012 Metric)")
      (fields (field (name "MF") "Murata") (field (name "MP") "GRM21BR60J107ME15L"))
      (libsource (lib "GRM21BR60J107ME15L") (part "GRM21BR60J107ME15L"))
    )
    (comp (ref "C82")
      (value "100uF")
      (footprint "CAPC2012X145N")
      (description "100 ÂµF Â±20% 6.3V Ceramic Capacitor X5R 0805 (2012 Metric)")
      (fields (field (name "MF") "Murata") (field (name "MP") "GRM21BR60J107ME15L"))
      (libsource (lib "GRM21BR60J107ME15L") (part "GRM21BR60J107ME15L"))
    )
    (comp (ref "C83")
      (value "100uF")
      (footprint "CAPC2012X145N")
      (description "100 ÂµF Â±20% 6.3V Ceramic Capacitor X5R 0805 (2012 Metric)")
      (fields (field (name "MF") "Murata") (field (name "MP") "GRM21BR60J107ME15L"))
      (libsource (lib "GRM21BR60J107ME15L") (part "GRM21BR60J107ME15L"))
    )
    (comp (ref "C84")
      (value "100uF")
      (footprint "CAPC2012X145N")
      (description "100 ÂµF Â±20% 6.3V Ceramic Capacitor X5R 0805 (2012 Metric)")
      (fields (field (name "MF") "Murata") (field (name "MP") "GRM21BR60J107ME15L"))
      (libsource (lib "GRM21BR60J107ME15L") (part "GRM21BR60J107ME15L"))
    )
    (comp (ref "C85")
      (value "100uF")
      (footprint "CAPC2012X145N")
      (description "100 ÂµF Â±20% 6.3V Ceramic Capacitor X5R 0805 (2012 Metric)")
      (fields (field (name "MF") "Murata") (field (name "MP") "GRM21BR60J107ME15L"))
      (libsource (lib "GRM21BR60J107ME15L") (part "GRM21BR60J107ME15L"))
    )
    (comp (ref "C86")
      (value "100uF")
      (footprint "CAPC2012X145N")
      (description "100 ÂµF Â±20% 6.3V Ceramic Capacitor X5R 0805 (2012 Metric)")
      (fields (field (name "MF") "Murata") (field (name "MP") "GRM21BR60J107ME15L"))
      (libsource (lib "GRM21BR60J107ME15L") (part "GRM21BR60J107ME15L"))
    )
    (comp (ref "C87")
      (value "100uF")
      (footprint "CAPC2012X145N")
      (description "100 ÂµF Â±20% 6.3V Ceramic Capacitor X5R 0805 (2012 Metric)")
      (fields (field (name "MF") "Murata") (field (name "MP") "GRM21BR60J107ME15L"))
      (libsource (lib "GRM21BR60J107ME15L") (part "GRM21BR60J107ME15L"))
    )
    (comp (ref "C88")
      (value "100uF")
      (footprint "CAPC2012X145N")
      (description "100 ÂµF Â±20% 6.3V Ceramic Capacitor X5R 0805 (2012 Metric)")
      (fields (field (name "MF") "Murata") (field (name "MP") "GRM21BR60J107ME15L"))
      (libsource (lib "GRM21BR60J107ME15L") (part "GRM21BR60J107ME15L"))
    )
    (comp (ref "C89")
      (value "1nF")
      (footprint "CAPC2012X145N")
      (description "100 ÂµF Â±20% 6.3V Ceramic Capacitor X5R 0805 (2012 Metric)")
      (fields (field (name "MF") "Murata") (field (name "MP") "GRM21BR60J107ME15L"))
      (libsource (lib "GRM21BR60J107ME15L") (part "GRM21BR60J107ME15L"))
    )
    (comp (ref "C90")
      (value "1nF")
      (footprint "CAPC2012X145N")
      (description "100 ÂµF Â±20% 6.3V Ceramic Capacitor X5R 0805 (2012 Metric)")
      (fields (field (name "MF") "Murata") (field (name "MP") "GRM21BR60J107ME15L"))
      (libsource (lib "GRM21BR60J107ME15L") (part "GRM21BR60J107ME15L"))
    )
    (comp (ref "C91")
      (value "1nF")
      (footprint "CAPC2012X145N")
      (description "100 ÂµF Â±20% 6.3V Ceramic Capacitor X5R 0805 (2012 Metric)")
      (fields (field (name "MF") "Murata") (field (name "MP") "GRM21BR60J107ME15L"))
      (libsource (lib "GRM21BR60J107ME15L") (part "GRM21BR60J107ME15L"))
    )
    (comp (ref "C92")
      (value "0.1uF")
      (footprint "CAPC1608X90")
      (description "No Description Available")
      (fields
        (field (name "MANUFACTURER_PART_NUMBER") "CC0603KRX7R7BB104")
        (field (name "COPYRIGHT") "Copyright (C) 2025 Ultra Librarian. All rights reserved.")
      )
      (libsource (lib "CC0603KRX7R7BB104") (part "CC0603KRX7R7BB104"))
    )
    (comp (ref "C93")
      (value "4.7uF")
      (footprint "CAPC1608X90")
      (description "No Description Available")
      (fields
        (field (name "MANUFACTURER_PART_NUMBER") "CC0603KRX7R7BB105")
        (field (name "COPYRIGHT") "Copyright (C) 2025 Ultra Librarian. All rights reserved.")
      )
      (libsource (lib "AIMLAB_TESTSTATION-V1.3.1-150922_1") (part "CC0603KRX7R7BB105"))
    )
    (comp (ref "C94")
      (value "2.2uF")
      (footprint "CAPC1608X90")
      (description "No Description Available")
      (fields
        (field (name "MANUFACTURER_PART_NUMBER") "CC0603KRX7R7BB105")
        (field (name "COPYRIGHT") "Copyright (C) 2025 Ultra Librarian. All rights reserved.")
      )
      (libsource (lib "AIMLAB_TESTSTATION-V1.3.1-150922_1") (part "CC0603KRX7R7BB105"))
    )
    (comp (ref "C95")
      (value "2.2uF")
      (footprint "CAPC1608X90")
      (description "No Description Available")
      (fields
        (field (name "MANUFACTURER_PART_NUMBER") "CC0603KRX7R7BB105")
        (field (name "COPYRIGHT") "Copyright (C) 2025 Ultra Librarian. All rights reserved.")
      )
      (libsource (lib "AIMLAB_TESTSTATION-V1.3.1-150922_1") (part "CC0603KRX7R7BB105"))
    )
    (comp (ref "C96")
      (value "0.1uF")
      (footprint "CAPC1608X90")
      (description "No Description Available")
      (fields
        (field (name "MANUFACTURER_PART_NUMBER") "CC0603KRX7R7BB104")
        (field (name "COPYRIGHT") "Copyright (C) 2025 Ultra Librarian. All rights reserved.")
      )
      (libsource (lib "CC0603KRX7R7BB104") (part "CC0603KRX7R7BB104"))
    )
    (comp (ref "C97")
      (value "0.1uF")
      (footprint "CAPC1608X90")
      (description "No Description Available")
      (fields
        (field (name "MANUFACTURER_PART_NUMBER") "CC0603KRX7R7BB104")
        (field (name "COPYRIGHT") "Copyright (C) 2025 Ultra Librarian. All rights reserved.")
      )
      (libsource (lib "CC0603KRX7R7BB104") (part "CC0603KRX7R7BB104"))
    )
    (comp (ref "C98")
      (value "0.1uF")
      (footprint "CAPC1608X90")
      (description "No Description Available")
      (fields
        (field (name "MANUFACTURER_PART_NUMBER") "CC0603KRX7R7BB104")
        (field (name "COPYRIGHT") "Copyright (C) 2025 Ultra Librarian. All rights reserved.")
      )
      (libsource (lib "CC0603KRX7R7BB104") (part "CC0603KRX7R7BB104"))
    )
    (comp (ref "C99")
      (value "0.1uF")
      (footprint "CAPC1608X90")
      (description "No Description Available")
      (fields
        (field (name "MANUFACTURER_PART_NUMBER") "CC0603KRX7R7BB104")
        (field (name "COPYRIGHT") "Copyright (C) 2025 Ultra Librarian. All rights reserved.")
      )
      (libsource (lib "CC0603KRX7R7BB104") (part "CC0603KRX7R7BB104"))
    )
    (comp (ref "C100")
      (value "0.1uF")
      (footprint "CAPC1608X90")
      (description "No Description Available")
      (fields
        (field (name "MANUFACTURER_PART_NUMBER") "CC0603KRX7R7BB104")
        (field (name "COPYRIGHT") "Copyright (C) 2025 Ultra Librarian. All rights reserved.")
      )
      (libsource (lib "CC0603KRX7R7BB104") (part "CC0603KRX7R7BB104"))
    )
    (comp (ref "C101")
      (value "0.1uF")
      (footprint "CAPC1608X90")
      (description "No Description Available")
      (fields
        (field (name "MANUFACTURER_PART_NUMBER") "CC0603KRX7R7BB104")
        (field (name "COPYRIGHT") "Copyright (C) 2025 Ultra Librarian. All rights reserved.")
      )
      (libsource (lib "CC0603KRX7R7BB104") (part "CC0603KRX7R7BB104"))
    )
    (comp (ref "C102")
      (value "1uF")
      (footprint "CAPC1608X90")
      (description "No Description Available")
      (fields
        (field (name "MANUFACTURER_PART_NUMBER") "CC0603KRX7R7BB105")
        (field (name "COPYRIGHT") "Copyright (C) 2025 Ultra Librarian. All rights reserved.")
      )
      (libsource (lib "AIMLAB_TESTSTATION-V1.3.1-150922_1") (part "CC0603KRX7R7BB105"))
    )
    (comp (ref "C103")
      (value "27pF")
      (footprint "CAPC1608X90")
      (description "No Description Available")
      (fields
        (field (name "MANUFACTURER_PART_NUMBER") "CC0603KRX7R7BB105")
        (field (name "COPYRIGHT") "Copyright (C) 2025 Ultra Librarian. All rights reserved.")
      )
      (libsource (lib "AIMLAB_TESTSTATION-V1.3.1-150922_1") (part "CC0603KRX7R7BB105"))
    )
    (comp (ref "C104")
      (value "27pF")
      (footprint "CAPC1608X90")
      (description "No Description Available")
      (fields
        (field (name "MANUFACTURER_PART_NUMBER") "CC0603KRX7R7BB105")
        (field (name "COPYRIGHT") "Copyright (C) 2025 Ultra Librarian. All rights reserved.")
      )
      (libsource (lib "AIMLAB_TESTSTATION-V1.3.1-150922_1") (part "CC0603KRX7R7BB105"))
    )
    (comp (ref "C105")
      (value "1uF")
      (footprint "CAPC1608X90")
      (description "No Description Available")
      (fields
        (field (name "MANUFACTURER_PART_NUMBER") "CC0603KRX7R7BB105")
        (field (name "COPYRIGHT") "Copyright (C) 2025 Ultra Librarian. All rights reserved.")
      )
      (libsource (lib "CC0603KRX7R7BB105") (part "CC0603KRX7R7BB105"))
    )
    (comp (ref "C106")
      (value "1uF")
      (footprint "CAPC1608X90")
      (description "No Description Available")
      (fields
        (field (name "MANUFACTURER_PART_NUMBER") "CC0603KRX7R7BB105")
        (field (name "COPYRIGHT") "Copyright (C) 2025 Ultra Librarian. All rights reserved.")
      )
      (libsource (lib "CC0603KRX7R7BB105") (part "CC0603KRX7R7BB105"))
    )
    (comp (ref "C107")
      (value "1uF")
      (footprint "CAPC1608X90")
      (description "No Description Available")
      (fields
        (field (name "MANUFACTURER_PART_NUMBER") "CC0603KRX7R7BB105")
        (field (name "COPYRIGHT") "Copyright (C) 2025 Ultra Librarian. All rights reserved.")
      )
      (libsource (lib "CC0603KRX7R7BB105") (part "CC0603KRX7R7BB105"))
    )
    (comp (ref "C108")
      (value "1uF")
      (footprint "CAPC1608X90")
      (description "No Description Available")
      (fields
        (field (name "MANUFACTURER_PART_NUMBER") "CC0603KRX7R7BB105")
        (field (name "COPYRIGHT") "Copyright (C) 2025 Ultra Librarian. All rights reserved.")
      )
      (libsource (lib "CC0603KRX7R7BB105") (part "CC0603KRX7R7BB105"))
    )
    (comp (ref "C109")
      (value "1uF")
      (footprint "CAPC1608X90")
      (description "No Description Available")
      (fields
        (field (name "MANUFACTURER_PART_NUMBER") "CC0603KRX7R7BB105")
        (field (name "COPYRIGHT") "Copyright (C) 2025 Ultra Librarian. All rights reserved.")
      )
      (libsource (lib "CC0603KRX7R7BB105") (part "CC0603KRX7R7BB105"))
    )
    (comp (ref "C110")
      (value "0.1uF")
      (footprint "CAPC1608X90")
      (description "No Description Available")
      (fields
        (field (name "MANUFACTURER_PART_NUMBER") "CC0603KRX7R7BB104")
        (field (name "COPYRIGHT") "Copyright (C) 2025 Ultra Librarian. All rights reserved.")
      )
      (libsource (lib "CC0603KRX7R7BB104") (part "CC0603KRX7R7BB104"))
    )
    (comp (ref "C111")
      (value "1uF")
      (footprint "CAPC1608X90")
      (description "No Description Available")
      (fields
        (field (name "MANUFACTURER_PART_NUMBER") "CC0603KRX7R7BB105")
        (field (name "COPYRIGHT") "Copyright (C) 2025 Ultra Librarian. All rights reserved.")
      )
      (libsource (lib "CC0603KRX7R7BB105") (part "CC0603KRX7R7BB105"))
    )
    (comp (ref "C112")
      (value "1uF")
      (footprint "CAPC1608X90")
      (description "No Description Available")
      (fields
        (field (name "MANUFACTURER_PART_NUMBER") "CC0603KRX7R7BB105")
        (field (name "COPYRIGHT") "Copyright (C) 2025 Ultra Librarian. All rights reserved.")
      )
      (libsource (lib "CC0603KRX7R7BB105") (part "CC0603KRX7R7BB105"))
    )
    (comp (ref "C113")
      (value "10uF")
      (footprint "CAPC2012X140N")
      (description "No Description Available")
      (fields
        (field (name "MANUFACTURER_PART_NUMBER") "CL21B106KOQNNNE")
        (field (name "COPYRIGHT") "Copyright (C) 2025 Ultra Librarian. All rights reserved.")
      )
      (libsource (lib "CL21B106KOQNNNE") (part "CL21B106KOQNNNE"))
    )
    (comp (ref "C114")
      (value "10u")
      (footprint "PolarizedCap")
      (description "Polarized Capacitor (Surface Mount)")
      (fields (field (name "PUBLISHER") "Altium Limited"))
      (libsource (lib "Miscellaneous Devices") (part "Cap Pol3"))
    )
    (comp (ref "C115")
      (value "1uF")
      (footprint "CAPC2012X140N")
      (description "Capacitor")
      (fields (field (name "PUBLISHER") "Altium Limited"))
      (libsource (lib "Miscellaneous Devices") (part "Cap"))
    )
    (comp (ref "C116")
      (value "0.1uF")
      (footprint "CAPC2012X140N")
      (description "Capacitor")
      (fields (field (name "PUBLISHER") "Altium Limited"))
      (libsource (lib "Miscellaneous Devices") (part "Cap"))
    )
    (comp (ref "C117")
      (value "0.1uF")
      (footprint "CAPC1608X90")
      (description "No Description Available")
      (fields
        (field (name "MANUFACTURER_PART_NUMBER") "CC0603KRX7R7BB104")
        (field (name "COPYRIGHT") "Copyright (C) 2025 Ultra Librarian. All rights reserved.")
      )
      (libsource (lib "AIMLAB_TESTSTATION-V1.3.1-150922_1") (part "CC0603KRX7R7BB104"))
    )
    (comp (ref "C118")
      (value "1uF")
      (footprint "CAPC1608X90")
      (description "No Description Available")
      (fields
        (field (name "MANUFACTURER_PART_NUMBER") "CC0603KRX7R7BB105")
        (field (name "COPYRIGHT") "Copyright (C) 2025 Ultra Librarian. All rights reserved.")
      )
      (libsource (lib "AIMLAB_TESTSTATION-V1.3.1-150922_1") (part "CC0603KRX7R7BB105"))
    )
    (comp (ref "C119")
      (value "0.1uF")
      (footprint "CAPC1608X90")
      (description "No Description Available")
      (fields
        (field (name "MANUFACTURER_PART_NUMBER") "CC0603KRX7R7BB104")
        (field (name "COPYRIGHT") "Copyright (C) 2025 Ultra Librarian. All rights reserved.")
      )
      (libsource (lib "AIMLAB_TESTSTATION-V1.3.1-150922_1") (part "CC0603KRX7R7BB104"))
    )
    (comp (ref "C120")
      (value "CBR04C220F5GAC")
      (footprint "CAPC1005X55N")
      (fields (field (name "COPYRIGHT") "Copyright (C) 2025 Ultra Librarian. All rights reserved."))
      (libsource (lib "CBR04C220F5GAC") (part "CBR04C220F5GAC"))
    )
    (comp (ref "C121")
      (value "0.1uF")
      (footprint "CAPC1608X90")
      (description "No Description Available")
      (fields
        (field (name "MANUFACTURER_PART_NUMBER") "CC0603KRX7R7BB105")
        (field (name "COPYRIGHT") "Copyright (C) 2025 Ultra Librarian. All rights reserved.")
      )
      (libsource (lib "CC0603KRX7R7BB105") (part "CC0603KRX7R7BB105"))
    )
    (comp (ref "C122")
      (value "1uF")
      (footprint "CAPC1608X90")
      (description "No Description Available")
      (fields
        (field (name "MANUFACTURER_PART_NUMBER") "CC0603KRX7R7BB105")
        (field (name "COPYRIGHT") "Copyright (C) 2025 Ultra Librarian. All rights reserved.")
      )
      (libsource (lib "CC0603KRX7R7BB105") (part "CC0603KRX7R7BB105"))
    )
    (comp (ref "C123")
      (value "CBR04C220F5GAC")
      (footprint "CAPC1005X55N")
      (fields (field (name "COPYRIGHT") "Copyright (C) 2025 Ultra Librarian. All rights reserved."))
      (libsource (lib "CBR04C220F5GAC") (part "CBR04C220F5GAC"))
    )
    (comp (ref "C124")
      (value "CBR04C220F5GAC")
      (footprint "CAPC1005X55N")
      (fields (field (name "COPYRIGHT") "Copyright (C) 2025 Ultra Librarian. All rights reserved."))
      (libsource (lib "CBR04C220F5GAC") (part "CBR04C220F5GAC"))
    )
    (comp (ref "C125")
      (value "CBR04C220F5GAC")
      (footprint "CAPC1005X55N")
      (fields (field (name "COPYRIGHT") "Copyright (C) 2025 Ultra Librarian. All rights reserved."))
      (libsource (lib "CBR04C220F5GAC") (part "CBR04C220F5GAC"))
    )
    (comp (ref "C126")
      (value "CBR04C220F5GAC")
      (footprint "CAPC1005X55N")
      (fields (field (name "COPYRIGHT") "Copyright (C) 2025 Ultra Librarian. All rights reserved."))
      (libsource (lib "CBR04C220F5GAC") (part "CBR04C220F5GAC"))
    )
    (comp (ref "C127")
      (value "1uF")
      (footprint "CAPC1608X90")
      (description "No Description Available")
      (fields
        (field (name "MANUFACTURER_PART_NUMBER") "CC0603KRX7R7BB105")
        (field (name "COPYRIGHT") "Copyright (C) 2025 Ultra Librarian. All rights reserved.")
      )
      (libsource (lib "CC0603KRX7R7BB105") (part "CC0603KRX7R7BB105"))
    )
    (comp (ref "C128")
      (value "1uF")
      (footprint "CAPC1608X90")
      (description "No Description Available")
      (fields
        (field (name "MANUFACTURER_PART_NUMBER") "CC0603KRX7R7BB105")
        (field (name "COPYRIGHT") "Copyright (C) 2025 Ultra Librarian. All rights reserved.")
      )
      (libsource (lib "CC0603KRX7R7BB105") (part "CC0603KRX7R7BB105"))
    )
    (comp (ref "C129")
      (value "100nF")
      (footprint "CAPC1608X90")
      (description "No Description Available")
      (fields
        (field (name "MANUFACTURER_PART_NUMBER") "CC0603KRX7R7BB105")
        (field (name "COPYRIGHT") "Copyright (C) 2025 Ultra Librarian. All rights reserved.")
      )
      (libsource (lib "AIMLAB_TESTSTATION-V1.3.1-150922_1") (part "CC0603KRX7R7BB105"))
    )
    (comp (ref "CR1")
      (value "USBLC6-2SC6")
      (footprint "SOT23-6L_STM")
      (description "ESD Protection for USB 2.0 High Speed")
      (fields (field (name "COPYRIGHT") "Copyright (C) 2025 Ultra Librarian. All rights reserved."))
      (libsource (lib "USBLC6-2SC6") (part "USBLC6-2SC6"))
    )
    (comp (ref "HD0")
      (value "Header 20X2")
      (footprint "ZIF40")
      (description "Header, 20-Pin, Dual row")
      (fields (field (name "PUBLISHER") "Altium Limited"))
      (libsource (lib "Miscellaneous Connectors") (part "Header 20X2"))
    )
    (comp (ref "HD1")
      (value "Header 20X2")
      (footprint "ZIF40")
      (description "Header, 20-Pin, Dual row")
      (fields (field (name "PUBLISHER") "Altium Limited"))
      (libsource (lib "Miscellaneous Connectors") (part "Header 20X2"))
    )
    (comp (ref "HD2")
      (value "Header 20X2")
      (footprint "ZIF40")
      (description "Header, 20-Pin, Dual row")
      (fields (field (name "PUBLISHER") "Altium Limited"))
      (libsource (lib "Miscellaneous Connectors") (part "Header 20X2"))
    )
    (comp (ref "HD3")
      (value "Header 20X2")
      (footprint "ZIF40")
      (description "Header, 20-Pin, Dual row")
      (fields (field (name "PUBLISHER") "Altium Limited"))
      (libsource (lib "Miscellaneous Connectors") (part "Header 20X2"))
    )
    (comp (ref "IC1")
      (value "OPA3S328RGRR")
      (footprint "VQFN20_3P5X3P5_TEX")
      (fields (field (name "COPYRIGHT") "Copyright (C) 2026 Ultra Librarian. All rights reserved."))
      (libsource (lib "OPA3S328RGRR") (part "OPA3S328RGRR"))
    )
    (comp (ref "J1")
      (value "12402012E212A")
      (footprint "12402012E212A:AMPHENOL_12402012E212A")
      (description "USB2.0, Type C, Top mount, CH 1.68mm, Dual Row SMT")
      (fields (field (name "MF") "Amphenol ICC (Commercial Products)"))
      (libsource (lib "12402012E212A") (part "12402012E212A"))
    )
    (comp (ref "JGND")
      (value "826632-3")
      (footprint "TE_826632-3")
      (description "PCB Breakaway Header, 2.54mm, 3 Way 2 Row, Gold, AMPMODU Headers Series ¦ TE Connectivity 826632-3")
      (fields (field (name "MF") "TE Connectivity"))
      (libsource (lib "826632-3") (part "826632-3"))
    )
    (comp (ref "JGND2")
      (value "VA")
      (footprint "HDR1X3")
      (description "Jumper")
      (libsource (lib "AIMLAB_TESTSTATION-V1.3.1-150922_1") (part "JP3_1"))
    )
    (comp (ref "JP0")
      (value "JP")
      (footprint "AimLab_TestStationM-v1.3.1-150922:HDR1X2")
      (description "Jumper")
      (libsource (lib "MySchLib") (part "JP2"))
    )
    (comp (ref "JP1")
      (value "JP")
      (footprint "AimLab_TestStationM-v1.3.1-150922:HDR1X2")
      (description "Jumper")
      (libsource (lib "MySchLib") (part "JP2"))
    )
    (comp (ref "JP2")
      (value "JP")
      (footprint "AimLab_TestStationM-v1.3.1-150922:HDR1X2")
      (description "Jumper")
      (libsource (lib "MySchLib") (part "JP2"))
    )
    (comp (ref "JP4")
      (value "JP")
      (footprint "AimLab_TestStationM-v1.3.1-150922:HDR1X2")
      (description "Jumper")
      (libsource (lib "") (part "JP2_1"))
    )
    (comp (ref "JP5")
      (value "JP")
      (footprint "AimLab_TestStationM-v1.3.1-150922:HDR1X2")
      (description "Jumper")
      (libsource (lib "MySchLib") (part "JP2"))
    )
    (comp (ref "JP6")
      (value "A")
      (footprint "JumperRes")
      (description "Jumper")
      (libsource (lib "AIMLAB_TESTSTATION-V1.3.1-150922_1") (part "JP3_1"))
    )
    (comp (ref "JP7")
      (value "B")
      (footprint "JumperRes")
      (description "Jumper")
      (libsource (lib "AIMLAB_TESTSTATION-V1.3.1-150922_1") (part "JP3_1"))
    )
    (comp (ref "JP8")
      (value "C")
      (footprint "JumperRes")
      (description "Jumper")
      (libsource (lib "AIMLAB_TESTSTATION-V1.3.1-150922_1") (part "JP3_1"))
    )
    (comp (ref "JP9")
      (value "JP")
      (footprint "HDR1X2")
      (description "Jumper")
      (libsource (lib "AIMLAB_TESTSTATION-V1.3.1-150922_1") (part "JP2"))
    )
    (comp (ref "JP10")
      (value "D")
      (footprint "JumperRes")
      (description "Jumper")
      (libsource (lib "AIMLAB_TESTSTATION-V1.3.1-150922_1") (part "JP3_1"))
    )
    (comp (ref "JP11")
      (value "A")
      (footprint "JumperRes")
      (description "Jumper")
      (libsource (lib "AIMLAB_TESTSTATION-V1.3.1-150922_1") (part "JP3_1"))
    )
    (comp (ref "JP12")
      (value "A")
      (footprint "JumperRes")
      (description "Jumper")
      (libsource (lib "AIMLAB_TESTSTATION-V1.3.1-150922_1") (part "JP3_1"))
    )
    (comp (ref "JP13")
      (value "B")
      (footprint "JumperRes")
      (description "Jumper")
      (libsource (lib "AIMLAB_TESTSTATION-V1.3.1-150922_1") (part "JP3_1"))
    )
    (comp (ref "JP14")
      (value "B")
      (footprint "JumperRes")
      (description "Jumper")
      (libsource (lib "AIMLAB_TESTSTATION-V1.3.1-150922_1") (part "JP3_1"))
    )
    (comp (ref "JP15")
      (value "C")
      (footprint "JumperRes")
      (description "Jumper")
      (libsource (lib "AIMLAB_TESTSTATION-V1.3.1-150922_1") (part "JP3_1"))
    )
    (comp (ref "JP16")
      (value "C")
      (footprint "JumperRes")
      (description "Jumper")
      (libsource (lib "AIMLAB_TESTSTATION-V1.3.1-150922_1") (part "JP3_1"))
    )
    (comp (ref "JP17")
      (value "D")
      (footprint "JumperRes")
      (description "Jumper")
      (libsource (lib "AIMLAB_TESTSTATION-V1.3.1-150922_1") (part "JP3_1"))
    )
    (comp (ref "JP18")
      (value "D")
      (footprint "JumperRes")
      (description "Jumper")
      (libsource (lib "AIMLAB_TESTSTATION-V1.3.1-150922_1") (part "JP3_1"))
    )
    (comp (ref "JP19")
      (value "JP")
      (footprint "AimLab_TestStationM-v1.3.1-150922:HDR1X2")
      (description "Jumper")
      (libsource (lib "MySchLib") (part "JP2"))
    )
    (comp (ref "JP20")
      (value "A")
      (footprint "JumperRes")
      (description "Jumper")
      (libsource (lib "AIMLAB_TESTSTATION-V1.3.1-150922_1") (part "JP3_1"))
    )
    (comp (ref "JP21")
      (value "A")
      (footprint "JumperRes")
      (description "Jumper")
      (libsource (lib "AIMLAB_TESTSTATION-V1.3.1-150922_1") (part "JP3_1"))
    )
    (comp (ref "JP22")
      (value "B")
      (footprint "JumperRes")
      (description "Jumper")
      (libsource (lib "AIMLAB_TESTSTATION-V1.3.1-150922_1") (part "JP3_1"))
    )
    (comp (ref "JP23")
      (value "B")
      (footprint "JumperRes")
      (description "Jumper")
      (libsource (lib "AIMLAB_TESTSTATION-V1.3.1-150922_1") (part "JP3_1"))
    )
    (comp (ref "JP24")
      (value "C")
      (footprint "JumperRes")
      (description "Jumper")
      (libsource (lib "AIMLAB_TESTSTATION-V1.3.1-150922_1") (part "JP3_1"))
    )
    (comp (ref "JP25")
      (value "C")
      (footprint "JumperRes")
      (description "Jumper")
      (libsource (lib "AIMLAB_TESTSTATION-V1.3.1-150922_1") (part "JP3_1"))
    )
    (comp (ref "JP26")
      (value "D")
      (footprint "JumperRes")
      (description "Jumper")
      (libsource (lib "AIMLAB_TESTSTATION-V1.3.1-150922_1") (part "JP3_1"))
    )
    (comp (ref "JP27")
      (value "D")
      (footprint "JumperRes")
      (description "Jumper")
      (libsource (lib "AIMLAB_TESTSTATION-V1.3.1-150922_1") (part "JP3_1"))
    )
    (comp (ref "JP28")
      (value "JP")
      (footprint "AimLab_TestStationM-v1.3.1-150922:HDR1X2")
      (description "Jumper")
      (libsource (lib "") (part "JP2_2"))
    )
    (comp (ref "JP29")
      (value "JP")
      (footprint "AIMLAB_TESTSTATION_ADC_V1:CAPC1608X90")
      (description "Jumper")
      (libsource (lib "MySchLib") (part "JP2"))
    )
    (comp (ref "JP30")
      (value "D")
      (footprint "JumperRes")
      (description "Jumper")
      (libsource (lib "AIMLAB_TESTSTATION-V1.3.1-150922_1") (part "JP3_1"))
    )
    (comp (ref "JP31")
      (value "JP")
      (footprint "HDR1X2")
      (description "Jumper")
      (libsource (lib "MySchLib") (part "JP2"))
    )
    (comp (ref "JP32")
      (value "JP")
      (footprint "HDR1X2")
      (description "Jumper")
      (libsource (lib "") (part "JP2_1"))
    )
    (comp (ref "JP33")
      (value "JP")
      (footprint "HDR1X2")
      (description "Jumper")
      (libsource (lib "AIMLAB_TESTSTATION-V1.3.1-150922_1") (part "JP2"))
    )
    (comp (ref "JP34")
      (value "D")
      (footprint "JumperRes")
      (description "Jumper")
      (libsource (lib "AIMLAB_TESTSTATION-V1.3.1-150922_1") (part "JP3_1"))
    )
    (comp (ref "JP35")
      (value "D")
      (footprint "JumperRes")
      (description "Jumper")
      (libsource (lib "AIMLAB_TESTSTATION-V1.3.1-150922_1") (part "JP3_1"))
    )
    (comp (ref "JP36")
      (value "D")
      (footprint "JumperRes")
      (description "Jumper")
      (libsource (lib "AIMLAB_TESTSTATION-V1.3.1-150922_1") (part "JP3_1"))
    )
    (comp (ref "JP37")
      (value "D")
      (footprint "JumperRes")
      (description "Jumper")
      (libsource (lib "AIMLAB_TESTSTATION-V1.3.1-150922_1") (part "JP3_1"))
    )
    (comp (ref "JPW0")
      (value "~")
      (footprint "AimLab_TestStationM-v1.3.1-150922:KLD-0202_")
      (description "Low Voltage Power Supply Connector")
      (fields (field (name "PUBLISHER") "Altium Limited"))
      (libsource (lib "MySchLib") (part "PWR2.5"))
    )
    (comp (ref "JP_DAC_2")
      (value "SCK")
      (footprint "HDR1X3")
      (description "Jumper")
      (libsource (lib "MySchLib") (part "JP3"))
    )
    (comp (ref "JP_DAC_3")
      (value "SDI")
      (footprint "HDR1X3")
      (description "Jumper")
      (libsource (lib "MySchLib") (part "JP3"))
    )
    (comp (ref "JP_DAC_4")
      (value "CSn")
      (footprint "HDR1X3")
      (description "Jumper")
      (libsource (lib "MySchLib") (part "JP3"))
    )
    (comp (ref "JP_DVDD")
      (value "JP")
      (footprint "AimLab_TestStationM-v1.3.1-150922:HDR1X3")
      (description "Jumper")
      (libsource (lib "MySchLib") (part "JP3"))
    )
    (comp (ref "JP_VLT")
      (value "VA")
      (footprint "HDR1X3")
      (description "Jumper")
      (libsource (lib "") (part "JP3_1_1"))
    )
    (comp (ref "JP_VLT1")
      (value "VA")
      (footprint "HDR1X3")
      (description "Jumper")
      (libsource (lib "") (part "JP3_1_1"))
    )
    (comp (ref "L2")
      (value "Ferrite Chip Beads")
      (footprint "AimLab_TestStationM-v1.3.1-150922:Inductor")
      (fields (field (name "PUBLISHER") "Altium Limited"))
      (libsource (lib "Miscellaneous Devices") (part "Inductor"))
    )
    (comp (ref "L3")
      (value "Ferrite Chip Beads")
      (footprint "Inductor")
      (fields (field (name "PUBLISHER") "Altium Limited"))
      (libsource (lib "Miscellaneous Devices") (part "Inductor"))
    )
    (comp (ref "L4")
      (value "Ferrite Chip Beads")
      (footprint "Inductor")
      (fields (field (name "PUBLISHER") "Altium Limited"))
      (libsource (lib "Miscellaneous Devices") (part "Inductor"))
    )
    (comp (ref "L5")
      (value "Ferrite Chip Beads")
      (footprint "Inductor")
      (fields (field (name "PUBLISHER") "Altium Limited"))
      (libsource (lib "Miscellaneous Devices") (part "Inductor"))
    )
    (comp (ref "L6")
      (value "Ferrite Chip Beads")
      (footprint "Inductor")
      (fields (field (name "PUBLISHER") "Altium Limited"))
      (libsource (lib "Miscellaneous Devices") (part "Inductor"))
    )
    (comp (ref "LED1")
      (value "LG L29K-F2J1-24-Z")
      (footprint "CAPC1608X90")
      (description "Description")
      (fields (field (name "COPYRIGHT") "Copyright (C) 2025 Ultra Librarian. All rights reserved."))
      (libsource (lib "LGL29K-F2J1-24-Z") (part "LG L29K-F2J1-24-Z"))
    )
    (comp (ref "LED2")
      (value "LG L29K-F2J1-24-Z")
      (footprint "CAPC1608X90")
      (description "Description")
      (fields (field (name "COPYRIGHT") "Copyright (C) 2025 Ultra Librarian. All rights reserved."))
      (libsource (lib "LGL29K-F2J1-24-Z") (part "LG L29K-F2J1-24-Z"))
    )
    (comp (ref "LED3")
      (value "LG L29K-F2J1-24-Z")
      (footprint "CAPC1608X90")
      (description "Description")
      (fields (field (name "COPYRIGHT") "Copyright (C) 2025 Ultra Librarian. All rights reserved."))
      (libsource (lib "LGL29K-F2J1-24-Z") (part "LG L29K-F2J1-24-Z"))
    )
    (comp (ref "LED4")
      (value "LG L29K-F2J1-24-Z")
      (footprint "CAPC1608X90")
      (description "Description")
      (fields (field (name "COPYRIGHT") "Copyright (C) 2025 Ultra Librarian. All rights reserved."))
      (libsource (lib "LGL29K-F2J1-24-Z") (part "LG L29K-F2J1-24-Z"))
    )
    (comp (ref "LED5")
      (value "LG L29K-F2J1-24-Z")
      (footprint "CAPC1608X90")
      (description "Description")
      (fields (field (name "COPYRIGHT") "Copyright (C) 2025 Ultra Librarian. All rights reserved."))
      (libsource (lib "LGL29K-F2J1-24-Z") (part "LG L29K-F2J1-24-Z"))
    )
    (comp (ref "LED6")
      (value "LG L29K-F2J1-24-Z")
      (footprint "CAPC1608X90")
      (description "Description")
      (fields (field (name "COPYRIGHT") "Copyright (C) 2025 Ultra Librarian. All rights reserved."))
      (libsource (lib "LGL29K-F2J1-24-Z") (part "LG L29K-F2J1-24-Z"))
    )
    (comp (ref "LED7")
      (value "LG L29K-F2J1-24-Z")
      (footprint "CAPC1608X90")
      (description "Description")
      (fields (field (name "COPYRIGHT") "Copyright (C) 2025 Ultra Librarian. All rights reserved."))
      (libsource (lib "LGL29K-F2J1-24-Z") (part "LG L29K-F2J1-24-Z"))
    )
    (comp (ref "LED8")
      (value "LG L29K-F2J1-24-Z")
      (footprint "CAPC1608X90")
      (description "Description")
      (fields (field (name "COPYRIGHT") "Copyright (C) 2025 Ultra Librarian. All rights reserved."))
      (libsource (lib "LGL29K-F2J1-24-Z") (part "LG L29K-F2J1-24-Z"))
    )
    (comp (ref "LED9")
      (value "LG L29K-F2J1-24-Z")
      (footprint "CAPC1608X90")
      (description "Description")
      (fields (field (name "COPYRIGHT") "Copyright (C) 2025 Ultra Librarian. All rights reserved."))
      (libsource (lib "LGL29K-F2J1-24-Z") (part "LG L29K-F2J1-24-Z"))
    )
    (comp (ref "Q1")
      (value "BSS138LT3G")
      (footprint "SOT95P237X111-3N:SOT95P237X111-3N")
      (fields (field (name "MF") "{'manufacturer': u'onsemi'}"))
      (libsource (lib "BSS138LT3G") (part "BSS138LT3G"))
    )
    (comp (ref "R1")
      (value "500")
      (footprint "AimLab_TestStationM-v1.3.1-150922:Resistor")
      (description "Resistor")
      (fields (field (name "PUBLISHER") "Altium Limited"))
      (libsource (lib "Miscellaneous Devices") (part "Res3"))
    )
    (comp (ref "R2")
      (value "2K")
      (footprint "AimLab_TestStationM-v1.3.1-150922:POT4MM-2")
      (description "Potentiometer")
      (fields (field (name "PUBLISHER") "Altium Limited"))
      (libsource (lib "MySchLib") (part "POT_"))
    )
    (comp (ref "R3")
      (value "500")
      (footprint "AimLab_TestStationM-v1.3.1-150922:Resistor")
      (description "Resistor")
      (fields (field (name "PUBLISHER") "Altium Limited"))
      (libsource (lib "Miscellaneous Devices") (part "Res3"))
    )
    (comp (ref "R4")
      (value "2K")
      (footprint "AimLab_TestStationM-v1.3.1-150922:POT4MM-2")
      (description "Potentiometer")
      (fields (field (name "PUBLISHER") "Altium Limited"))
      (libsource (lib "MySchLib") (part "POT_"))
    )
    (comp (ref "R5")
      (value "18K RC0603JR-0718KL")
      (footprint "RES_ERA3AEB2491V:RES_ERA3AEB2491V")
      (fields (field (name "MP") "ERA3AEB2491V"))
      (libsource (lib "ERA3AEB2491V") (part "ERA3AEB2491V"))
    )
    (comp (ref "R6")
      (value "7.5K RC0603FR-077K5L")
      (footprint "RES_ERA3AEB2491V:RES_ERA3AEB2491V")
      (fields (field (name "MP") "ERA3AEB2491V"))
      (libsource (lib "ERA3AEB2491V") (part "ERA3AEB2491V"))
    )
    (comp (ref "R7")
      (value "100k RC0603FR-07100KL")
      (footprint "RES_ERA3AEB2491V")
      (fields (field (name "MP") "ERA3AEB2491V"))
      (libsource (lib "ERA3AEB2491V") (part "ERA3AEB2491V"))
    )
    (comp (ref "R8")
      (value "2.5K ERA3AEB2491V")
      (footprint "RES_ERA3AEB2491V:RES_ERA3AEB2491V")
      (fields (field (name "MP") "ERA3AEB2491V"))
      (libsource (lib "ERA3AEB2491V") (part "ERA3AEB2491V"))
    )
    (comp (ref "R9")
      (value "2.5K ERA3AEB2491V")
      (footprint "RES_ERA3AEB2491V:RES_ERA3AEB2491V")
      (fields (field (name "MP") "ERA3AEB2491V"))
      (libsource (lib "ERA3AEB2491V") (part "ERA3AEB2491V"))
    )
    (comp (ref "R10")
      (value "100k RC0603FR-07100KL")
      (footprint "RES_ERA3AEB2491V:RES_ERA3AEB2491V")
      (fields (field (name "MP") "ERA3AEB2491V"))
      (libsource (lib "ERA3AEB2491V") (part "ERA3AEB2491V"))
    )
    (comp (ref "R11")
      (value "220Ohm")
      (footprint "RESC1608X50N:RESC1608X50N")
      (description "RG1608P-221-B-T5")
      (libsource (lib "RG1608P-221-B-T5") (part "RG1608P-221-B-T5"))
    )
    (comp (ref "R12")
      (value "220Ohm")
      (footprint "RESC1608X50N:RESC1608X50N")
      (description "RG1608P-221-B-T5")
      (libsource (lib "RG1608P-221-B-T5") (part "RG1608P-221-B-T5"))
    )
    (comp (ref "R13")
      (value "220Ohm")
      (footprint "RESC1608X50N:RESC1608X50N")
      (description "RG1608P-221-B-T5")
      (libsource (lib "RG1608P-221-B-T5") (part "RG1608P-221-B-T5"))
    )
    (comp (ref "R14")
      (value "220Ohm")
      (footprint "RESC1608X50N:RESC1608X50N")
      (description "RG1608P-221-B-T5")
      (libsource (lib "RG1608P-221-B-T5") (part "RG1608P-221-B-T5"))
    )
    (comp (ref "R15")
      (value "220Ohm")
      (footprint "RESC1608X50N:RESC1608X50N")
      (description "RG1608P-221-B-T5")
      (libsource (lib "RG1608P-221-B-T5") (part "RG1608P-221-B-T5"))
    )
    (comp (ref "R16")
      (value "220Ohm")
      (footprint "RESC1608X50N:RESC1608X50N")
      (description "RG1608P-221-B-T5")
      (libsource (lib "RG1608P-221-B-T5") (part "RG1608P-221-B-T5"))
    )
    (comp (ref "R17")
      (value "220Ohm")
      (footprint "RESC1608X50N:RESC1608X50N")
      (description "RG1608P-221-B-T5")
      (libsource (lib "RG1608P-221-B-T5") (part "RG1608P-221-B-T5"))
    )
    (comp (ref "R18")
      (value "220Ohm")
      (footprint "RESC1608X50N:RESC1608X50N")
      (description "RG1608P-221-B-T5")
      (libsource (lib "RG1608P-221-B-T5") (part "RG1608P-221-B-T5"))
    )
    (comp (ref "R19")
      (value "220Ohm")
      (footprint "RESC1608X50N:RESC1608X50N")
      (description "RG1608P-221-B-T5")
      (libsource (lib "RG1608P-221-B-T5") (part "RG1608P-221-B-T5"))
    )
    (comp (ref "R20")
      (value "220Ohm")
      (footprint "RESC1608X50N:RESC1608X50N")
      (description "RG1608P-221-B-T5")
      (libsource (lib "RG1608P-221-B-T5") (part "RG1608P-221-B-T5"))
    )
    (comp (ref "R21")
      (value "220Ohm")
      (footprint "RESC1608X50N:RESC1608X50N")
      (description "RG1608P-221-B-T5")
      (libsource (lib "RG1608P-221-B-T5") (part "RG1608P-221-B-T5"))
    )
    (comp (ref "R22")
      (value "220Ohm")
      (footprint "RESC1608X50N:RESC1608X50N")
      (description "RG1608P-221-B-T5")
      (libsource (lib "RG1608P-221-B-T5") (part "RG1608P-221-B-T5"))
    )
    (comp (ref "R23")
      (value "220Ohm")
      (footprint "RESC1608X50N:RESC1608X50N")
      (description "RG1608P-221-B-T5")
      (libsource (lib "RG1608P-221-B-T5") (part "RG1608P-221-B-T5"))
    )
    (comp (ref "R24")
      (value "220Ohm")
      (footprint "RESC1608X50N:RESC1608X50N")
      (description "RG1608P-221-B-T5")
      (libsource (lib "RG1608P-221-B-T5") (part "RG1608P-221-B-T5"))
    )
    (comp (ref "R25")
      (value "220Ohm")
      (footprint "RESC1608X50N:RESC1608X50N")
      (description "RG1608P-221-B-T5")
      (libsource (lib "RG1608P-221-B-T5") (part "RG1608P-221-B-T5"))
    )
    (comp (ref "R26")
      (value "220Ohm")
      (footprint "RESC1608X50N:RESC1608X50N")
      (description "RG1608P-221-B-T5")
      (libsource (lib "RG1608P-221-B-T5") (part "RG1608P-221-B-T5"))
    )
    (comp (ref "R27")
      (value "100k RC0603FR-07100KL")
      (footprint "RES_ERA3AEB2491V:RES_ERA3AEB2491V")
      (fields (field (name "MP") "ERA3AEB2491V"))
      (libsource (lib "ERA3AEB2491V") (part "ERA3AEB2491V"))
    )
    (comp (ref "R28")
      (value "100k RC0603FR-07100KL")
      (footprint "RES_ERA3AEB2491V:RES_ERA3AEB2491V")
      (fields (field (name "MP") "ERA3AEB2491V"))
      (libsource (lib "ERA3AEB2491V") (part "ERA3AEB2491V"))
    )
    (comp (ref "R29")
      (value "10Ohm")
      (footprint "RESC1608X50N:RESC1608X50N")
      (description "RG1608P-221-B-T5")
      (libsource (lib "RG1608P-221-B-T5") (part "RG1608P-221-B-T5"))
    )
    (comp (ref "R30")
      (value "10Ohm")
      (footprint "RESC1608X50N:RESC1608X50N")
      (description "RG1608P-221-B-T5")
      (libsource (lib "RG1608P-221-B-T5") (part "RG1608P-221-B-T5"))
    )
    (comp (ref "R31")
      (value "10Ohm")
      (footprint "RESC1608X50N:RESC1608X50N")
      (description "RG1608P-221-B-T5")
      (libsource (lib "RG1608P-221-B-T5") (part "RG1608P-221-B-T5"))
    )
    (comp (ref "R32")
      (value "10Ohm")
      (footprint "RESC1608X50N:RESC1608X50N")
      (description "RG1608P-221-B-T5")
      (libsource (lib "RG1608P-221-B-T5") (part "RG1608P-221-B-T5"))
    )
    (comp (ref "R33")
      (value "10Ohm")
      (footprint "RESC1608X50N:RESC1608X50N")
      (description "RG1608P-221-B-T5")
      (libsource (lib "RG1608P-221-B-T5") (part "RG1608P-221-B-T5"))
    )
    (comp (ref "R34")
      (value "10Ohm")
      (footprint "RESC1608X50N:RESC1608X50N")
      (description "RG1608P-221-B-T5")
      (libsource (lib "RG1608P-221-B-T5") (part "RG1608P-221-B-T5"))
    )
    (comp (ref "R35")
      (value "10Ohm")
      (footprint "RESC1608X50N:RESC1608X50N")
      (description "RG1608P-221-B-T5")
      (libsource (lib "RG1608P-221-B-T5") (part "RG1608P-221-B-T5"))
    )
    (comp (ref "R36")
      (value "10Ohm")
      (footprint "RESC1608X50N:RESC1608X50N")
      (description "RG1608P-221-B-T5")
      (libsource (lib "RG1608P-221-B-T5") (part "RG1608P-221-B-T5"))
    )
    (comp (ref "R37")
      (value "100Ohm")
      (footprint "RESC1608X50N:RESC1608X50N")
      (description "RG1608P-221-B-T5")
      (libsource (lib "RG1608P-221-B-T5") (part "RG1608P-221-B-T5"))
    )
    (comp (ref "R38")
      (value "100Ohm")
      (footprint "RESC1608X50N:RESC1608X50N")
      (description "RG1608P-221-B-T5")
      (libsource (lib "RG1608P-221-B-T5") (part "RG1608P-221-B-T5"))
    )
    (comp (ref "R39")
      (value "100Ohm")
      (footprint "RESC1608X50N:RESC1608X50N")
      (description "RG1608P-221-B-T5")
      (libsource (lib "RG1608P-221-B-T5") (part "RG1608P-221-B-T5"))
    )
    (comp (ref "R40")
      (value "100Ohm")
      (footprint "RESC1608X50N:RESC1608X50N")
      (description "RG1608P-221-B-T5")
      (libsource (lib "RG1608P-221-B-T5") (part "RG1608P-221-B-T5"))
    )
    (comp (ref "R41")
      (value "100Ohm")
      (footprint "RESC1608X50N:RESC1608X50N")
      (description "RG1608P-221-B-T5")
      (libsource (lib "RG1608P-221-B-T5") (part "RG1608P-221-B-T5"))
    )
    (comp (ref "R42")
      (value "100Ohm")
      (footprint "RESC1608X50N:RESC1608X50N")
      (description "RG1608P-221-B-T5")
      (libsource (lib "RG1608P-221-B-T5") (part "RG1608P-221-B-T5"))
    )
    (comp (ref "R43")
      (value "100Ohm")
      (footprint "RESC1608X50N:RESC1608X50N")
      (description "RG1608P-221-B-T5")
      (libsource (lib "RG1608P-221-B-T5") (part "RG1608P-221-B-T5"))
    )
    (comp (ref "R44")
      (value "100Ohm")
      (footprint "RESC1608X50N:RESC1608X50N")
      (description "RG1608P-221-B-T5")
      (libsource (lib "RG1608P-221-B-T5") (part "RG1608P-221-B-T5"))
    )
    (comp (ref "R45")
      (value "10k")
      (footprint "RES_ERA3AEB2491V:RES_ERA3AEB2491V")
      (fields (field (name "MP") "ERA3AEB2491V"))
      (libsource (lib "ERA3AEB2491V") (part "ERA3AEB2491V"))
    )
    (comp (ref "R46")
      (value "10Ohm")
      (footprint "RESC1608X50N:RESC1608X50N")
      (description "RG1608P-221-B-T5")
      (libsource (lib "RG1608P-221-B-T5") (part "RG1608P-221-B-T5"))
    )
    (comp (ref "R47")
      (value "10Ohm")
      (footprint "RESC1608X50N:RESC1608X50N")
      (description "RG1608P-221-B-T5")
      (libsource (lib "RG1608P-221-B-T5") (part "RG1608P-221-B-T5"))
    )
    (comp (ref "R48")
      (value "10Ohm")
      (footprint "RESC1608X50N:RESC1608X50N")
      (description "RG1608P-221-B-T5")
      (libsource (lib "RG1608P-221-B-T5") (part "RG1608P-221-B-T5"))
    )
    (comp (ref "R49")
      (value "10Ohm")
      (footprint "RESC1608X50N:RESC1608X50N")
      (description "RG1608P-221-B-T5")
      (libsource (lib "RG1608P-221-B-T5") (part "RG1608P-221-B-T5"))
    )
    (comp (ref "R50")
      (value "10Ohm")
      (footprint "RESC1608X50N:RESC1608X50N")
      (description "RG1608P-221-B-T5")
      (libsource (lib "RG1608P-221-B-T5") (part "RG1608P-221-B-T5"))
    )
    (comp (ref "R51")
      (value "10Ohm")
      (footprint "RESC1608X50N:RESC1608X50N")
      (description "RG1608P-221-B-T5")
      (libsource (lib "RG1608P-221-B-T5") (part "RG1608P-221-B-T5"))
    )
    (comp (ref "R52")
      (value "10Ohm")
      (footprint "RESC1608X50N:RESC1608X50N")
      (description "RG1608P-221-B-T5")
      (libsource (lib "RG1608P-221-B-T5") (part "RG1608P-221-B-T5"))
    )
    (comp (ref "R53")
      (value "10Ohm")
      (footprint "RESC1608X50N:RESC1608X50N")
      (description "RG1608P-221-B-T5")
      (libsource (lib "RG1608P-221-B-T5") (part "RG1608P-221-B-T5"))
    )
    (comp (ref "R54")
      (value "100Ohm")
      (footprint "RESC1608X50N:RESC1608X50N")
      (description "RG1608P-221-B-T5")
      (libsource (lib "RG1608P-221-B-T5") (part "RG1608P-221-B-T5"))
    )
    (comp (ref "R55")
      (value "100Ohm")
      (footprint "RESC1608X50N:RESC1608X50N")
      (description "RG1608P-221-B-T5")
      (libsource (lib "RG1608P-221-B-T5") (part "RG1608P-221-B-T5"))
    )
    (comp (ref "R56")
      (value "100Ohm")
      (footprint "RESC1608X50N:RESC1608X50N")
      (description "RG1608P-221-B-T5")
      (libsource (lib "RG1608P-221-B-T5") (part "RG1608P-221-B-T5"))
    )
    (comp (ref "R57")
      (value "100Ohm")
      (footprint "RESC1608X50N:RESC1608X50N")
      (description "RG1608P-221-B-T5")
      (libsource (lib "RG1608P-221-B-T5") (part "RG1608P-221-B-T5"))
    )
    (comp (ref "R58")
      (value "100Ohm")
      (footprint "RESC1608X50N:RESC1608X50N")
      (description "RG1608P-221-B-T5")
      (libsource (lib "RG1608P-221-B-T5") (part "RG1608P-221-B-T5"))
    )
    (comp (ref "R59")
      (value "100Ohm")
      (footprint "RESC1608X50N:RESC1608X50N")
      (description "RG1608P-221-B-T5")
      (libsource (lib "RG1608P-221-B-T5") (part "RG1608P-221-B-T5"))
    )
    (comp (ref "R60")
      (value "100Ohm")
      (footprint "RESC1608X50N:RESC1608X50N")
      (description "RG1608P-221-B-T5")
      (libsource (lib "RG1608P-221-B-T5") (part "RG1608P-221-B-T5"))
    )
    (comp (ref "R61")
      (value "100Ohm")
      (footprint "RESC1608X50N:RESC1608X50N")
      (description "RG1608P-221-B-T5")
      (libsource (lib "RG1608P-221-B-T5") (part "RG1608P-221-B-T5"))
    )
    (comp (ref "R62")
      (value "5.1k")
      (footprint "RES_ERA3AEB2491V:RES_ERA3AEB2491V")
      (fields (field (name "MP") "ERA3AEB2491V"))
      (libsource (lib "ERA3AEB2491V") (part "ERA3AEB2491V"))
    )
    (comp (ref "R63")
      (value "7.5K RC0603FR-077K5L")
      (footprint "RES_ERA3AEB2491V:RES_ERA3AEB2491V")
      (fields (field (name "MP") "ERA3AEB2491V"))
      (libsource (lib "ERA3AEB2491V") (part "ERA3AEB2491V"))
    )
    (comp (ref "R64")
      (value "5.1k")
      (footprint "RES_ERA3AEB2491V:RES_ERA3AEB2491V")
      (fields (field (name "MP") "ERA3AEB2491V"))
      (libsource (lib "ERA3AEB2491V") (part "ERA3AEB2491V"))
    )
    (comp (ref "R65")
      (value "0")
      (footprint "RES_ERA3AEB2491V:RES_ERA3AEB2491V")
      (fields (field (name "MP") "ERA3AEB2491V"))
      (libsource (lib "ERA3AEB2491V") (part "ERA3AEB2491V"))
    )
    (comp (ref "R66")
      (value "10Ohm")
      (footprint "RESC1608X50N:RESC1608X50N")
      (description "RG1608P-221-B-T5")
      (libsource (lib "RG1608P-221-B-T5") (part "RG1608P-221-B-T5"))
    )
    (comp (ref "R67")
      (value "10Ohm")
      (footprint "RESC1608X50N:RESC1608X50N")
      (description "RG1608P-221-B-T5")
      (libsource (lib "RG1608P-221-B-T5") (part "RG1608P-221-B-T5"))
    )
    (comp (ref "R68")
      (value "10Ohm")
      (footprint "RESC1608X50N:RESC1608X50N")
      (description "RG1608P-221-B-T5")
      (libsource (lib "RG1608P-221-B-T5") (part "RG1608P-221-B-T5"))
    )
    (comp (ref "R69")
      (value "10Ohm")
      (footprint "RESC1608X50N:RESC1608X50N")
      (description "RG1608P-221-B-T5")
      (libsource (lib "RG1608P-221-B-T5") (part "RG1608P-221-B-T5"))
    )
    (comp (ref "R70")
      (value "47Ohm")
      (footprint "CAPC1608X90")
      (fields (field (name "MP") "ERA3AEB2491V"))
      (libsource (lib "ERA3AEB2491V") (part "ERA3AEB2491V"))
    )
    (comp (ref "R71")
      (value "47Ohm")
      (footprint "CAPC1608X90")
      (fields (field (name "MP") "ERA3AEB2491V"))
      (libsource (lib "ERA3AEB2491V") (part "ERA3AEB2491V"))
    )
    (comp (ref "R72")
      (value "47Ohm")
      (footprint "CAPC1608X90")
      (fields (field (name "MP") "ERA3AEB2491V"))
      (libsource (lib "ERA3AEB2491V") (part "ERA3AEB2491V"))
    )
    (comp (ref "R73")
      (value "47Ohm")
      (footprint "CAPC1608X90")
      (fields (field (name "MP") "ERA3AEB2491V"))
      (libsource (lib "ERA3AEB2491V") (part "ERA3AEB2491V"))
    )
    (comp (ref "R74")
      (value "47Ohm")
      (footprint "CAPC1608X90")
      (fields (field (name "MP") "ERA3AEB2491V"))
      (libsource (lib "ERA3AEB2491V") (part "ERA3AEB2491V"))
    )
    (comp (ref "R75")
      (value "47Ohm")
      (footprint "CAPC1608X90")
      (fields (field (name "MP") "ERA3AEB2491V"))
      (libsource (lib "ERA3AEB2491V") (part "ERA3AEB2491V"))
    )
    (comp (ref "R76")
      (value "47Ohm")
      (footprint "CAPC1608X90")
      (fields (field (name "MP") "ERA3AEB2491V"))
      (libsource (lib "ERA3AEB2491V") (part "ERA3AEB2491V"))
    )
    (comp (ref "R77")
      (value "47Ohm")
      (footprint "CAPC1608X90")
      (fields (field (name "MP") "ERA3AEB2491V"))
      (libsource (lib "ERA3AEB2491V") (part "ERA3AEB2491V"))
    )
    (comp (ref "R78")
      (value "47Ohm")
      (footprint "CAPC1608X90")
      (fields (field (name "MP") "ERA3AEB2491V"))
      (libsource (lib "ERA3AEB2491V") (part "ERA3AEB2491V"))
    )
    (comp (ref "R79")
      (value "47Ohm")
      (footprint "CAPC1608X90")
      (fields (field (name "MP") "ERA3AEB2491V"))
      (libsource (lib "ERA3AEB2491V") (part "ERA3AEB2491V"))
    )
    (comp (ref "R80")
      (value "100k RC0603FR-07100KL")
      (footprint "RES_ERA3AEB2491V")
      (fields (field (name "MP") "ERA3AEB2491V"))
      (libsource (lib "ERA3AEB2491V") (part "ERA3AEB2491V"))
    )
    (comp (ref "R81")
      (value "47Ohm")
      (footprint "CAPC1608X90")
      (fields (field (name "MP") "ERA3AEB2491V"))
      (libsource (lib "ERA3AEB2491V") (part "ERA3AEB2491V"))
    )
    (comp (ref "R82")
      (value "47Ohm")
      (footprint "CAPC1608X90")
      (fields (field (name "MP") "ERA3AEB2491V"))
      (libsource (lib "ERA3AEB2491V") (part "ERA3AEB2491V"))
    )
    (comp (ref "R83")
      (value "47Ohm")
      (footprint "CAPC1608X90")
      (fields (field (name "MP") "ERA3AEB2491V"))
      (libsource (lib "ERA3AEB2491V") (part "ERA3AEB2491V"))
    )
    (comp (ref "R84")
      (value "47Ohm")
      (footprint "CAPC1608X90")
      (fields (field (name "MP") "ERA3AEB2491V"))
      (libsource (lib "ERA3AEB2491V") (part "ERA3AEB2491V"))
    )
    (comp (ref "R85")
      (value "2M_MCT0603MD2004BP500")
      (footprint "AIMLAB_TESTSTATION_ADC_V1:CAPC1608X90")
      (description "MCT 0603-25 0.1% AT P5 2M0")
      (fields
        (field (name "MANUFACTURER_PART_NUMBER") "MCT0603MD2004BP500")
        (field (name "COPYRIGHT") "Copyright (C) 2025 Ultra Librarian. All rights reserved.")
      )
      (libsource (lib "MCT0603MD2004BP500") (part "MCT0603MD2004BP500"))
    )
    (comp (ref "R86")
      (value "200k_MCT0603MD2003BP500")
      (footprint "CAPC1608X90")
      (description "MCT 0603-25 0.1% AT P5 2M0")
      (fields
        (field (name "MANUFACTURER_PART_NUMBER") "MCT0603MD2004BP500")
        (field (name "COPYRIGHT") "Copyright (C) 2025 Ultra Librarian. All rights reserved.")
      )
      (libsource (lib "MCT0603MD2004BP500") (part "MCT0603MD2004BP500"))
    )
    (comp (ref "R87")
      (value "200k_MCT0603MD2003BP500")
      (footprint "CAPC1608X90")
      (description "MCT 0603-25 0.1% AT P5 2M0")
      (fields
        (field (name "MANUFACTURER_PART_NUMBER") "MCT0603MD2004BP500")
        (field (name "COPYRIGHT") "Copyright (C) 2025 Ultra Librarian. All rights reserved.")
      )
      (libsource (lib "MCT0603MD2004BP500") (part "MCT0603MD2004BP500"))
    )
    (comp (ref "R88")
      (value "20k_MCT0603MD2002BP500")
      (footprint "CAPC1608X90")
      (description "MCT 0603-25 0.1% AT P5 2M0")
      (fields
        (field (name "MANUFACTURER_PART_NUMBER") "MCT0603MD2004BP500")
        (field (name "COPYRIGHT") "Copyright (C) 2025 Ultra Librarian. All rights reserved.")
      )
      (libsource (lib "MCT0603MD2004BP500") (part "MCT0603MD2004BP500"))
    )
    (comp (ref "R89")
      (value "20k_MCT0603MD2002BP500")
      (footprint "CAPC1608X90")
      (description "MCT 0603-25 0.1% AT P5 2M0")
      (fields
        (field (name "MANUFACTURER_PART_NUMBER") "MCT0603MD2004BP500")
        (field (name "COPYRIGHT") "Copyright (C) 2025 Ultra Librarian. All rights reserved.")
      )
      (libsource (lib "MCT0603MD2004BP500") (part "MCT0603MD2004BP500"))
    )
    (comp (ref "R90")
      (value "22Ohm")
      (footprint "RES_ERA3AEB2491V")
      (fields (field (name "MP") "ERA3AEB2491V"))
      (libsource (lib "ERA3AEB2491V") (part "ERA3AEB2491V"))
    )
    (comp (ref "R91")
      (value "22Ohm")
      (footprint "RES_ERA3AEB2491V")
      (fields (field (name "MP") "ERA3AEB2491V"))
      (libsource (lib "ERA3AEB2491V") (part "ERA3AEB2491V"))
    )
    (comp (ref "R92")
      (value "100kOhm")
      (footprint "CAPC1608X90")
      (fields (field (name "MP") "ERA3AEB2491V"))
      (libsource (lib "ERA3AEB2491V") (part "ERA3AEB2491V"))
    )
    (comp (ref "R93")
      (value "100kOhm")
      (footprint "CAPC1608X90")
      (fields (field (name "MP") "ERA3AEB2491V"))
      (libsource (lib "ERA3AEB2491V") (part "ERA3AEB2491V"))
    )
    (comp (ref "R94")
      (value "100kOhm")
      (footprint "CAPC1608X90")
      (fields (field (name "MP") "ERA3AEB2491V"))
      (libsource (lib "ERA3AEB2491V") (part "ERA3AEB2491V"))
    )
    (comp (ref "R95")
      (value "100kOhm")
      (footprint "CAPC1608X90")
      (fields (field (name "MP") "ERA3AEB2491V"))
      (libsource (lib "ERA3AEB2491V") (part "ERA3AEB2491V"))
    )
    (comp (ref "R96")
      (value "22Ohm")
      (footprint "RES_ERA3AEB2491V")
      (fields (field (name "MP") "ERA3AEB2491V"))
      (libsource (lib "ERA3AEB2491V") (part "ERA3AEB2491V"))
    )
    (comp (ref "R97")
      (value "22Ohm")
      (footprint "RES_ERA3AEB2491V")
      (fields (field (name "MP") "ERA3AEB2491V"))
      (libsource (lib "ERA3AEB2491V") (part "ERA3AEB2491V"))
    )
    (comp (ref "R98")
      (value "22Ohm")
      (footprint "RES_ERA3AEB2491V")
      (fields (field (name "MP") "ERA3AEB2491V"))
      (libsource (lib "ERA3AEB2491V") (part "ERA3AEB2491V"))
    )
    (comp (ref "R99")
      (value "22Ohm")
      (footprint "RES_ERA3AEB2491V")
      (fields (field (name "MP") "ERA3AEB2491V"))
      (libsource (lib "ERA3AEB2491V") (part "ERA3AEB2491V"))
    )
    (comp (ref "R100")
      (value "100k")
      (footprint "RES_ERA3AEB2491V")
      (fields (field (name "MP") "ERA3AEB2491V"))
      (libsource (lib "ERA3AEB2491V") (part "ERA3AEB2491V"))
    )
    (comp (ref "R101")
      (value "100k")
      (footprint "RES_ERA3AEB2491V")
      (fields (field (name "MP") "ERA3AEB2491V"))
      (libsource (lib "ERA3AEB2491V") (part "ERA3AEB2491V"))
    )
    (comp (ref "R102")
      (value "18K RC0603JR-0718KL")
      (footprint "RES_ERA3AEB2491V")
      (fields (field (name "MP") "ERA3AEB2491V"))
      (libsource (lib "ERA3AEB2491V") (part "ERA3AEB2491V"))
    )
    (comp (ref "R103")
      (value "7.5K RC0603FR-077K5L")
      (footprint "RES_ERA3AEB2491V")
      (fields (field (name "MP") "ERA3AEB2491V"))
      (libsource (lib "ERA3AEB2491V") (part "ERA3AEB2491V"))
    )
    (comp (ref "R104")
      (value "2.5K ERA3AEB2491V")
      (footprint "RES_ERA3AEB2491V")
      (fields (field (name "MP") "ERA3AEB2491V"))
      (libsource (lib "ERA3AEB2491V") (part "ERA3AEB2491V"))
    )
    (comp (ref "R105")
      (value "2.5K ERA3AEB2491V")
      (footprint "RES_ERA3AEB2491V")
      (fields (field (name "MP") "ERA3AEB2491V"))
      (libsource (lib "ERA3AEB2491V") (part "ERA3AEB2491V"))
    )
    (comp (ref "S1")
      (value "PTS647SK38SMTR2LFS")
      (footprint "PTS647SK38SMTR2LFS")
      (description "Tactile Switch SPST-NO Top Actuated Surface Mount")
      (fields (field (name "MF") "C&K") (field (name "MP") "PTS 647 SK38 SMTR2 LFS"))
      (libsource (lib "PTS647SK38SMTR2LFS") (part "PTS647SK38SMTR2LFS"))
    )
    (comp (ref "SWD")
      (value "826632-3")
      (footprint "TE_826632-3:TE_826632-3")
      (description "PCB Breakaway Header, 2.54mm, 3 Way 2 Row, Gold, AMPMODU Headers Series ¦ TE Connectivity 826632-3")
      (fields (field (name "MF") "TE Connectivity"))
      (libsource (lib "826632-3") (part "826632-3"))
    )
    (comp (ref "U1")
      (value "LM1086")
      (footprint "AimLab_TestStationM-v1.3.1-150922:TO-263-3")
      (libsource (lib "MySchLib") (part "LM1086"))
    )
    (comp (ref "U2")
      (value "LM1086")
      (footprint "AimLab_TestStationM-v1.3.1-150922:TO-263-3")
      (libsource (lib "MySchLib") (part "LM1086"))
    )
    (comp (ref "U3")
      (value "OPA4388IDR")
      (footprint "D0014A-IPC_A")
      (fields (field (name "COPYRIGHT") "Copyright (C) 2026 Ultra Librarian. All rights reserved."))
      (libsource (lib "OPA4388IDR") (part "OPA4388IDR"))
    )
    (comp (ref "U4")
      (value "DAC80508ZRTER")
      (footprint "QFN50P300X300X80-17N")
      (libsource (lib "DAC80508ZRTER") (part "DAC80508ZRTER"))
    )
    (comp (ref "U5")
      (value "DAC80508ZRTER")
      (footprint "QFN50P300X300X80-17N")
      (libsource (lib "DAC80508ZRTER") (part "DAC80508ZRTER"))
    )
    (comp (ref "U6")
      (value "DAC80508ZRTER")
      (footprint "QFN50P300X300X80-17N")
      (libsource (lib "DAC80508ZRTER") (part "DAC80508ZRTER"))
    )
    (comp (ref "U7")
      (value "DAC80508ZRTER")
      (footprint "QFN50P300X300X80-17N")
      (libsource (lib "DAC80508ZRTER") (part "DAC80508ZRTER"))
    )
    (comp (ref "U8")
      (value "DAC80508ZRTER")
      (footprint "QFN50P300X300X80-17N")
      (libsource (lib "DAC80508ZRTER") (part "DAC80508ZRTER"))
    )
    (comp (ref "U9")
      (value "OPA4388IDR")
      (footprint "D0014A-IPC_A")
      (fields (field (name "COPYRIGHT") "Copyright (C) 2026 Ultra Librarian. All rights reserved."))
      (libsource (lib "OPA4388IDR") (part "OPA4388IDR"))
    )
    (comp (ref "U10")
      (value "OPA4388IDR")
      (footprint "D0014A-IPC_A")
      (fields (field (name "COPYRIGHT") "Copyright (C) 2026 Ultra Librarian. All rights reserved."))
      (libsource (lib "OPA4388IDR") (part "OPA4388IDR"))
    )
    (comp (ref "U11")
      (value "SN74LVC8T245DGVR")
      (footprint "SOP40P640X120-24N:SOP40P640X120-24N")
      (libsource (lib "SN74LVC8T245DGVR") (part "SN74LVC8T245DGVR"))
    )
    (comp (ref "U12")
      (value "TPS7A2018PDBVR")
      (footprint "SOT95P280X145-5N")
      (fields (field (name "MF") "{'manufacturer': u'Texas Instruments'}"))
      (libsource (lib "TPS7A2018PDBVR") (part "TPS7A2018PDBVR"))
    )
    (comp (ref "U13")
      (value "STM32H743VIT6")
      (footprint "LQFP100-14x14mm")
      (fields (field (name "COPYRIGHT") "Copyright (C) 2025 Ultra Librarian. All rights reserved."))
      (libsource (lib "STM32H743VIT6") (part "STM32H743VIT6"))
    )
    (comp (ref "U14")
      (value "ADS131A04IPBS")
      (footprint "PBS0032A_N")
      (description "24-bit 128-kSPS 4-channel simultaneous-sampling delta-sigma ADC 32-TQFP -40 to 125")
      (fields (field (name "COPYRIGHT") "Copyright (C) 2025 Ultra Librarian. All rights reserved."))
      (libsource (lib "ADS131A04IPBS") (part "ADS131A04IPBS"))
    )
    (comp (ref "U15")
      (value "ADS131A04IPBS")
      (footprint "PBS0032A_N")
      (description "24-bit 128-kSPS 4-channel simultaneous-sampling delta-sigma ADC 32-TQFP -40 to 125")
      (fields (field (name "COPYRIGHT") "Copyright (C) 2025 Ultra Librarian. All rights reserved."))
      (libsource (lib "ADS131A04IPBS") (part "ADS131A04IPBS"))
    )
    (comp (ref "U16")
      (value "OPA4388IDR")
      (footprint "D0014A-IPC_A")
      (fields (field (name "COPYRIGHT") "Copyright (C) 2026 Ultra Librarian. All rights reserved."))
      (libsource (lib "OPA4388IDR") (part "OPA4388IDR"))
    )
    (comp (ref "U17")
      (value "OPA4388IDR")
      (footprint "D0014A-IPC_A")
      (fields (field (name "COPYRIGHT") "Copyright (C) 2026 Ultra Librarian. All rights reserved."))
      (libsource (lib "OPA4388IDR") (part "OPA4388IDR"))
    )
    (comp (ref "U18")
      (value "ADR4525CRZ-R7")
      (footprint "R-8_ADI")
      (description "Ultra-Low-Noise, High-Accuracy 2.5V Voltage Reference")
      (fields (field (name "COPYRIGHT") "Copyright (C) 2025 Ultra Librarian. All rights reserved."))
      (libsource (lib "ADR4525CRZ-R7") (part "ADR4525CRZ-R7"))
    )
    (comp (ref "U19")
      (value "SN74LVC8T245DGVR")
      (footprint "SOP40P640X120-24N:SOP40P640X120-24N")
      (libsource (lib "SN74LVC8T245DGVR") (part "SN74LVC8T245DGVR"))
    )
    (comp (ref "Y1")
      (value "ABM3B-8.000MHZ-B2-T")
      (footprint "XTAL_ABM3B-8.000MHZ-B2-T")
      (description "8 MHz Â±20ppm Crystal 18pF 200 Ohms 4-SMD, No Lead")
      (fields (field (name "MF") "Abracon"))
      (libsource (lib "ABM3B-8.000MHZ-B2-T") (part "ABM3B-8.000MHZ-B2-T"))
    )
  )
  (nets
    (net (code "1") (name "/-INA") (class "Default")
      (node (ref "C123") (pin "2") (pinfunction "2_2") (pintype "passive"))
      (node (ref "C125") (pin "2") (pinfunction "2_2") (pintype "passive"))
      (node (ref "HD2") (pin "12") (pinfunction "12_12") (pintype "passive"))
      (node (ref "IC1") (pin "18") (pinfunction "18_18") (pintype "passive"))
      (node (ref "R86") (pin "2") (pinfunction "2_2") (pintype "passive"))
      (node (ref "R88") (pin "2") (pinfunction "2_2") (pintype "passive"))
    )
    (net (code "2") (name "/-INB") (class "Default")
      (node (ref "C120") (pin "2") (pinfunction "2_2") (pintype "passive"))
      (node (ref "C124") (pin "2") (pinfunction "2_2") (pintype "passive"))
      (node (ref "C126") (pin "2") (pinfunction "2_2") (pintype "passive"))
      (node (ref "HD2") (pin "10") (pinfunction "10_10") (pintype "passive"))
      (node (ref "IC1") (pin "8") (pinfunction "8_8") (pintype "passive"))
      (node (ref "R85") (pin "2") (pinfunction "2_2") (pintype "passive"))
      (node (ref "R87") (pin "2") (pinfunction "2_2") (pintype "passive"))
      (node (ref "R89") (pin "2") (pinfunction "2_2") (pintype "passive"))
    )
    (net (code "3") (name "/ADC1_CS") (class "Default")
      (node (ref "U13") (pin "98") (pinfunction "PE1_98") (pintype "bidirectional"))
      (node (ref "U14") (pin "23") (pinfunction "CS_N_23") (pintype "input"))
    )
    (net (code "4") (name "/ADC1_DRDY") (class "Default")
      (node (ref "U13") (pin "1") (pinfunction "PE2_1") (pintype "bidirectional"))
      (node (ref "U14") (pin "19") (pinfunction "DRDY_N_19") (pintype "bidirectional"))
    )
    (net (code "5") (name "/ADC2_CS") (class "Default")
      (node (ref "U13") (pin "97") (pinfunction "PE0_97") (pintype "bidirectional"))
      (node (ref "U15") (pin "23") (pinfunction "CS_N_23") (pintype "input"))
    )
    (net (code "6") (name "/ADC2_DOUT") (class "Default")
      (node (ref "JP30") (pin "2") (pinfunction "2_2") (pintype "passive"))
      (node (ref "R28") (pin "1") (pinfunction "1_1") (pintype "passive"))
      (node (ref "U15") (pin "21") (pinfunction "DOUT_21") (pintype "output"))
    )
    (net (code "7") (name "/ADC2_DRDY") (class "Default")
      (node (ref "U13") (pin "2") (pinfunction "PE3_2") (pintype "bidirectional"))
      (node (ref "U15") (pin "19") (pinfunction "DRDY_N_19") (pintype "bidirectional"))
    )
    (net (code "8") (name "/ADC2_SDOUT") (class "Default")
      (node (ref "JP30") (pin "3") (pinfunction "3_3") (pintype "passive"))
      (node (ref "U13") (pin "4") (pinfunction "PE5_4") (pintype "bidirectional"))
    )
    (net (code "9") (name "/ADC_MCLK") (class "Default")
      (node (ref "U13") (pin "67") (pinfunction "PA8_67") (pintype "bidirectional"))
      (node (ref "U14") (pin "25") (pinfunction "CLKIN_XTAL1_25") (pintype "input"))
      (node (ref "U15") (pin "25") (pinfunction "CLKIN_XTAL1_25") (pintype "input"))
    )
    (net (code "10") (name "/ADC_RESET") (class "Default")
      (node (ref "U13") (pin "3") (pinfunction "PE4_3") (pintype "bidirectional"))
      (node (ref "U14") (pin "17") (pinfunction "RESET_N_17") (pintype "input"))
      (node (ref "U15") (pin "17") (pinfunction "RESET_N_17") (pintype "input"))
    )
    (net (code "11") (name "/AIN1N_B") (class "Default")
      (node (ref "JP11") (pin "3") (pinfunction "3_3") (pintype "passive"))
      (node (ref "R32") (pin "2") (pinfunction "2_2") (pintype "passive"))
      (node (ref "R37") (pin "1") (pinfunction "1_1") (pintype "passive"))
    )
    (net (code "12") (name "/AIN1N_F") (class "Default")
      (node (ref "C58") (pin "2") (pinfunction "2_2") (pintype "passive"))
      (node (ref "R37") (pin "2") (pinfunction "2_2") (pintype "passive"))
      (node (ref "U14") (pin "1") (pinfunction "AIN1N_1") (pintype "input"))
    )
    (net (code "13") (name "/AIN1N_I") (class "Default")
      (node (ref "HD2") (pin "39") (pinfunction "39_39") (pintype "passive"))
      (node (ref "JP11") (pin "2") (pinfunction "2_2") (pintype "passive"))
    )
    (net (code "14") (name "/AIN1N_R") (class "Default")
      (node (ref "JP11") (pin "1") (pinfunction "1_1") (pintype "passive"))
      (node (ref "U3") (pin "10") (pinfunction "+IN_C_10") (pintype "tri_state"))
    )
    (net (code "15") (name "/AIN1P_B") (class "Default")
      (node (ref "JP13") (pin "3") (pinfunction "3_3") (pintype "passive"))
      (node (ref "R31") (pin "1") (pinfunction "1_1") (pintype "passive"))
      (node (ref "R39") (pin "1") (pinfunction "1_1") (pintype "passive"))
    )
    (net (code "16") (name "/AIN1P_F") (class "Default")
      (node (ref "C58") (pin "1") (pinfunction "1_1") (pintype "passive"))
      (node (ref "R39") (pin "2") (pinfunction "2_2") (pintype "passive"))
      (node (ref "U14") (pin "2") (pinfunction "AIN1P_2") (pintype "input"))
    )
    (net (code "17") (name "/AIN1P_I") (class "Default")
      (node (ref "HD2") (pin "40") (pinfunction "40_40") (pintype "passive"))
      (node (ref "JP13") (pin "2") (pinfunction "2_2") (pintype "passive"))
    )
    (net (code "18") (name "/AIN1P_R") (class "Default")
      (node (ref "JP13") (pin "1") (pinfunction "1_1") (pintype "passive"))
      (node (ref "U3") (pin "5") (pinfunction "+IN_B_5") (pintype "tri_state"))
    )
    (net (code "19") (name "/AIN2N_B") (class "Default")
      (node (ref "JP15") (pin "3") (pinfunction "3_3") (pintype "passive"))
      (node (ref "R30") (pin "1") (pinfunction "1_1") (pintype "passive"))
      (node (ref "R38") (pin "1") (pinfunction "1_1") (pintype "passive"))
    )
    (net (code "20") (name "/AIN2N_F") (class "Default")
      (node (ref "C59") (pin "2") (pinfunction "2_2") (pintype "passive"))
      (node (ref "R38") (pin "2") (pinfunction "2_2") (pintype "passive"))
      (node (ref "U14") (pin "3") (pinfunction "AIN2N_3") (pintype "input"))
    )
    (net (code "21") (name "/AIN2N_I") (class "Default")
      (node (ref "HD2") (pin "37") (pinfunction "37_37") (pintype "passive"))
      (node (ref "JP15") (pin "2") (pinfunction "2_2") (pintype "passive"))
    )
    (net (code "22") (name "/AIN2N_R") (class "Default")
      (node (ref "JP15") (pin "1") (pinfunction "1_1") (pintype "passive"))
      (node (ref "U3") (pin "3") (pinfunction "+IN_A_3") (pintype "tri_state"))
    )
    (net (code "23") (name "/AIN2P_B") (class "Default")
      (node (ref "JP17") (pin "3") (pinfunction "3_3") (pintype "passive"))
      (node (ref "R29") (pin "2") (pinfunction "2_2") (pintype "passive"))
      (node (ref "R40") (pin "1") (pinfunction "1_1") (pintype "passive"))
    )
    (net (code "24") (name "/AIN2P_F") (class "Default")
      (node (ref "C59") (pin "1") (pinfunction "1_1") (pintype "passive"))
      (node (ref "R40") (pin "2") (pinfunction "2_2") (pintype "passive"))
      (node (ref "U14") (pin "4") (pinfunction "AIN2P_4") (pintype "input"))
    )
    (net (code "25") (name "/AIN2P_I") (class "Default")
      (node (ref "HD2") (pin "38") (pinfunction "38_38") (pintype "passive"))
      (node (ref "JP17") (pin "2") (pinfunction "2_2") (pintype "passive"))
    )
    (net (code "26") (name "/AIN2P_R") (class "Default")
      (node (ref "JP17") (pin "1") (pinfunction "1_1") (pintype "passive"))
      (node (ref "U3") (pin "12") (pinfunction "+IN_D_12") (pintype "tri_state"))
    )
    (net (code "27") (name "/AIN3N_B") (class "Default")
      (node (ref "JP12") (pin "3") (pinfunction "3_3") (pintype "passive"))
      (node (ref "R36") (pin "2") (pinfunction "2_2") (pintype "passive"))
      (node (ref "R41") (pin "1") (pinfunction "1_1") (pintype "passive"))
    )
    (net (code "28") (name "/AIN3N_F") (class "Default")
      (node (ref "C73") (pin "2") (pinfunction "2_2") (pintype "passive"))
      (node (ref "R41") (pin "2") (pinfunction "2_2") (pintype "passive"))
      (node (ref "U14") (pin "5") (pinfunction "AIN3N_5") (pintype "input"))
    )
    (net (code "29") (name "/AIN3N_I") (class "Default")
      (node (ref "HD2") (pin "35") (pinfunction "35_35") (pintype "passive"))
      (node (ref "JP12") (pin "2") (pinfunction "2_2") (pintype "passive"))
    )
    (net (code "30") (name "/AIN3N_R") (class "Default")
      (node (ref "JP12") (pin "1") (pinfunction "1_1") (pintype "passive"))
      (node (ref "U9") (pin "10") (pinfunction "+IN_C_10") (pintype "tri_state"))
    )
    (net (code "31") (name "/AIN3P_B") (class "Default")
      (node (ref "JP14") (pin "3") (pinfunction "3_3") (pintype "passive"))
      (node (ref "R35") (pin "1") (pinfunction "1_1") (pintype "passive"))
      (node (ref "R43") (pin "1") (pinfunction "1_1") (pintype "passive"))
    )
    (net (code "32") (name "/AIN3P_F") (class "Default")
      (node (ref "C73") (pin "1") (pinfunction "1_1") (pintype "passive"))
      (node (ref "R43") (pin "2") (pinfunction "2_2") (pintype "passive"))
      (node (ref "U14") (pin "6") (pinfunction "AIN3P_6") (pintype "input"))
    )
    (net (code "33") (name "/AIN3P_I") (class "Default")
      (node (ref "HD2") (pin "36") (pinfunction "36_36") (pintype "passive"))
      (node (ref "JP14") (pin "2") (pinfunction "2_2") (pintype "passive"))
    )
    (net (code "34") (name "/AIN3P_R") (class "Default")
      (node (ref "JP14") (pin "1") (pinfunction "1_1") (pintype "passive"))
      (node (ref "U9") (pin "5") (pinfunction "+IN_B_5") (pintype "tri_state"))
    )
    (net (code "35") (name "/AIN4N_B") (class "Default")
      (node (ref "JP16") (pin "3") (pinfunction "3_3") (pintype "passive"))
      (node (ref "R34") (pin "1") (pinfunction "1_1") (pintype "passive"))
      (node (ref "R42") (pin "1") (pinfunction "1_1") (pintype "passive"))
    )
    (net (code "36") (name "/AIN4N_F") (class "Default")
      (node (ref "C74") (pin "2") (pinfunction "2_2") (pintype "passive"))
      (node (ref "R42") (pin "2") (pinfunction "2_2") (pintype "passive"))
      (node (ref "U14") (pin "7") (pinfunction "AIN4N_7") (pintype "input"))
    )
    (net (code "37") (name "/AIN4N_I") (class "Default")
      (node (ref "HD2") (pin "33") (pinfunction "33_33") (pintype "passive"))
      (node (ref "JP16") (pin "2") (pinfunction "2_2") (pintype "passive"))
    )
    (net (code "38") (name "/AIN4N_R") (class "Default")
      (node (ref "JP16") (pin "1") (pinfunction "1_1") (pintype "passive"))
      (node (ref "U9") (pin "3") (pinfunction "+IN_A_3") (pintype "tri_state"))
    )
    (net (code "39") (name "/AIN4P_B") (class "Default")
      (node (ref "JP18") (pin "3") (pinfunction "3_3") (pintype "passive"))
      (node (ref "R33") (pin "2") (pinfunction "2_2") (pintype "passive"))
      (node (ref "R44") (pin "1") (pinfunction "1_1") (pintype "passive"))
    )
    (net (code "40") (name "/AIN4P_F") (class "Default")
      (node (ref "C74") (pin "1") (pinfunction "1_1") (pintype "passive"))
      (node (ref "R44") (pin "2") (pinfunction "2_2") (pintype "passive"))
      (node (ref "U14") (pin "8") (pinfunction "AIN4P_8") (pintype "input"))
    )
    (net (code "41") (name "/AIN4P_I") (class "Default")
      (node (ref "HD2") (pin "34") (pinfunction "34_34") (pintype "passive"))
      (node (ref "JP18") (pin "2") (pinfunction "2_2") (pintype "passive"))
    )
    (net (code "42") (name "/AIN4P_R") (class "Default")
      (node (ref "JP18") (pin "1") (pinfunction "1_1") (pintype "passive"))
      (node (ref "U9") (pin "12") (pinfunction "+IN_D_12") (pintype "tri_state"))
    )
    (net (code "43") (name "/AIN5N_B") (class "Default")
      (node (ref "JP20") (pin "3") (pinfunction "3_3") (pintype "passive"))
      (node (ref "R49") (pin "2") (pinfunction "2_2") (pintype "passive"))
      (node (ref "R54") (pin "1") (pinfunction "1_1") (pintype "passive"))
    )
    (net (code "44") (name "/AIN5N_F") (class "Default")
      (node (ref "C80") (pin "2") (pinfunction "2_2") (pintype "passive"))
      (node (ref "R54") (pin "2") (pinfunction "2_2") (pintype "passive"))
      (node (ref "U15") (pin "1") (pinfunction "AIN1N_1") (pintype "input"))
    )
    (net (code "45") (name "/AIN5N_I") (class "Default")
      (node (ref "HD2") (pin "30") (pinfunction "30_30") (pintype "passive"))
      (node (ref "JP20") (pin "2") (pinfunction "2_2") (pintype "passive"))
    )
    (net (code "46") (name "/AIN5N_R") (class "Default")
      (node (ref "JP20") (pin "1") (pinfunction "1_1") (pintype "passive"))
      (node (ref "U16") (pin "10") (pinfunction "+IN_C_10") (pintype "tri_state"))
    )
    (net (code "47") (name "/AIN5P_B") (class "Default")
      (node (ref "JP22") (pin "3") (pinfunction "3_3") (pintype "passive"))
      (node (ref "R48") (pin "1") (pinfunction "1_1") (pintype "passive"))
      (node (ref "R56") (pin "1") (pinfunction "1_1") (pintype "passive"))
    )
    (net (code "48") (name "/AIN5P_F") (class "Default")
      (node (ref "C80") (pin "1") (pinfunction "1_1") (pintype "passive"))
      (node (ref "R56") (pin "2") (pinfunction "2_2") (pintype "passive"))
      (node (ref "U15") (pin "2") (pinfunction "AIN1P_2") (pintype "input"))
    )
    (net (code "49") (name "/AIN5P_I") (class "Default")
      (node (ref "HD2") (pin "32") (pinfunction "32_32") (pintype "passive"))
      (node (ref "JP22") (pin "2") (pinfunction "2_2") (pintype "passive"))
    )
    (net (code "50") (name "/AIN5P_R") (class "Default")
      (node (ref "JP22") (pin "1") (pinfunction "1_1") (pintype "passive"))
      (node (ref "U16") (pin "5") (pinfunction "+IN_B_5") (pintype "tri_state"))
    )
    (net (code "51") (name "/AIN6N_B") (class "Default")
      (node (ref "JP24") (pin "3") (pinfunction "3_3") (pintype "passive"))
      (node (ref "R47") (pin "1") (pinfunction "1_1") (pintype "passive"))
      (node (ref "R55") (pin "1") (pinfunction "1_1") (pintype "passive"))
    )
    (net (code "52") (name "/AIN6N_F") (class "Default")
      (node (ref "C89") (pin "2") (pinfunction "2_2") (pintype "passive"))
      (node (ref "R55") (pin "2") (pinfunction "2_2") (pintype "passive"))
      (node (ref "U15") (pin "3") (pinfunction "AIN2N_3") (pintype "input"))
    )
    (net (code "53") (name "/AIN6N_I") (class "Default")
      (node (ref "HD2") (pin "26") (pinfunction "26_26") (pintype "passive"))
      (node (ref "JP24") (pin "2") (pinfunction "2_2") (pintype "passive"))
    )
    (net (code "54") (name "/AIN6N_R") (class "Default")
      (node (ref "JP24") (pin "1") (pinfunction "1_1") (pintype "passive"))
      (node (ref "U16") (pin "3") (pinfunction "+IN_A_3") (pintype "tri_state"))
    )
    (net (code "55") (name "/AIN6P_B") (class "Default")
      (node (ref "JP26") (pin "3") (pinfunction "3_3") (pintype "passive"))
      (node (ref "R46") (pin "2") (pinfunction "2_2") (pintype "passive"))
      (node (ref "R57") (pin "1") (pinfunction "1_1") (pintype "passive"))
    )
    (net (code "56") (name "/AIN6P_F") (class "Default")
      (node (ref "C89") (pin "1") (pinfunction "1_1") (pintype "passive"))
      (node (ref "R57") (pin "2") (pinfunction "2_2") (pintype "passive"))
      (node (ref "U15") (pin "4") (pinfunction "AIN2P_4") (pintype "input"))
    )
    (net (code "57") (name "/AIN6P_I") (class "Default")
      (node (ref "HD2") (pin "28") (pinfunction "28_28") (pintype "passive"))
      (node (ref "JP26") (pin "2") (pinfunction "2_2") (pintype "passive"))
    )
    (net (code "58") (name "/AIN6P_R") (class "Default")
      (node (ref "JP26") (pin "1") (pinfunction "1_1") (pintype "passive"))
      (node (ref "U16") (pin "12") (pinfunction "+IN_D_12") (pintype "tri_state"))
    )
    (net (code "59") (name "/AIN7NV_I") (class "Default")
      (node (ref "HD2") (pin "24") (pinfunction "24_24") (pintype "passive"))
      (node (ref "JP34") (pin "3") (pinfunction "3_3") (pintype "passive"))
    )
    (net (code "60") (name "/AIN7N_B") (class "Default")
      (node (ref "JP21") (pin "3") (pinfunction "3_3") (pintype "passive"))
      (node (ref "R53") (pin "2") (pinfunction "2_2") (pintype "passive"))
      (node (ref "R58") (pin "1") (pinfunction "1_1") (pintype "passive"))
    )
    (net (code "61") (name "/AIN7N_F") (class "Default")
      (node (ref "C90") (pin "2") (pinfunction "2_2") (pintype "passive"))
      (node (ref "R58") (pin "2") (pinfunction "2_2") (pintype "passive"))
      (node (ref "U15") (pin "5") (pinfunction "AIN3N_5") (pintype "input"))
    )
    (net (code "62") (name "/AIN7N_I") (class "Default")
      (node (ref "JP21") (pin "2") (pinfunction "2_2") (pintype "passive"))
      (node (ref "JP34") (pin "2") (pinfunction "2_2") (pintype "passive"))
    )
    (net (code "63") (name "/AIN7N_R") (class "Default")
      (node (ref "JP21") (pin "1") (pinfunction "1_1") (pintype "passive"))
      (node (ref "U17") (pin "10") (pinfunction "+IN_C_10") (pintype "tri_state"))
    )
    (net (code "64") (name "/AIN7PV_I") (class "Default")
      (node (ref "HD2") (pin "22") (pinfunction "22_22") (pintype "passive"))
      (node (ref "JP35") (pin "3") (pinfunction "3_3") (pintype "passive"))
    )
    (net (code "65") (name "/AIN7P_B") (class "Default")
      (node (ref "JP23") (pin "3") (pinfunction "3_3") (pintype "passive"))
      (node (ref "R52") (pin "1") (pinfunction "1_1") (pintype "passive"))
      (node (ref "R60") (pin "1") (pinfunction "1_1") (pintype "passive"))
    )
    (net (code "66") (name "/AIN7P_F") (class "Default")
      (node (ref "C90") (pin "1") (pinfunction "1_1") (pintype "passive"))
      (node (ref "R60") (pin "2") (pinfunction "2_2") (pintype "passive"))
      (node (ref "U15") (pin "6") (pinfunction "AIN3P_6") (pintype "input"))
    )
    (net (code "67") (name "/AIN7P_I") (class "Default")
      (node (ref "JP23") (pin "2") (pinfunction "2_2") (pintype "passive"))
      (node (ref "JP35") (pin "2") (pinfunction "2_2") (pintype "passive"))
    )
    (net (code "68") (name "/AIN7P_R") (class "Default")
      (node (ref "JP23") (pin "1") (pinfunction "1_1") (pintype "passive"))
      (node (ref "U17") (pin "5") (pinfunction "+IN_B_5") (pintype "tri_state"))
    )
    (net (code "69") (name "/AIN8NV_I") (class "Default")
      (node (ref "HD2") (pin "18") (pinfunction "18_18") (pintype "passive"))
      (node (ref "JP36") (pin "3") (pinfunction "3_3") (pintype "passive"))
    )
    (net (code "70") (name "/AIN8N_B") (class "Default")
      (node (ref "JP25") (pin "3") (pinfunction "3_3") (pintype "passive"))
      (node (ref "R51") (pin "1") (pinfunction "1_1") (pintype "passive"))
      (node (ref "R59") (pin "1") (pinfunction "1_1") (pintype "passive"))
    )
    (net (code "71") (name "/AIN8N_F") (class "Default")
      (node (ref "C91") (pin "2") (pinfunction "2_2") (pintype "passive"))
      (node (ref "R59") (pin "2") (pinfunction "2_2") (pintype "passive"))
      (node (ref "U15") (pin "7") (pinfunction "AIN4N_7") (pintype "input"))
    )
    (net (code "72") (name "/AIN8N_I") (class "Default")
      (node (ref "JP25") (pin "2") (pinfunction "2_2") (pintype "passive"))
      (node (ref "JP36") (pin "2") (pinfunction "2_2") (pintype "passive"))
    )
    (net (code "73") (name "/AIN8N_R") (class "Default")
      (node (ref "JP25") (pin "1") (pinfunction "1_1") (pintype "passive"))
      (node (ref "U17") (pin "3") (pinfunction "+IN_A_3") (pintype "tri_state"))
    )
    (net (code "74") (name "/AIN8PV_I") (class "Default")
      (node (ref "HD2") (pin "20") (pinfunction "20_20") (pintype "passive"))
      (node (ref "JP37") (pin "3") (pinfunction "3_3") (pintype "passive"))
    )
    (net (code "75") (name "/AIN8P_B") (class "Default")
      (node (ref "JP27") (pin "3") (pinfunction "3_3") (pintype "passive"))
      (node (ref "R50") (pin "2") (pinfunction "2_2") (pintype "passive"))
      (node (ref "R61") (pin "1") (pinfunction "1_1") (pintype "passive"))
    )
    (net (code "76") (name "/AIN8P_F") (class "Default")
      (node (ref "C91") (pin "1") (pinfunction "1_1") (pintype "passive"))
      (node (ref "R61") (pin "2") (pinfunction "2_2") (pintype "passive"))
      (node (ref "U15") (pin "8") (pinfunction "AIN4P_8") (pintype "input"))
    )
    (net (code "77") (name "/AIN8P_I") (class "Default")
      (node (ref "JP27") (pin "2") (pinfunction "2_2") (pintype "passive"))
      (node (ref "JP37") (pin "2") (pinfunction "2_2") (pintype "passive"))
    )
    (net (code "78") (name "/AIN8P_R") (class "Default")
      (node (ref "JP27") (pin "1") (pinfunction "1_1") (pintype "passive"))
      (node (ref "U17") (pin "12") (pinfunction "+IN_D_12") (pintype "tri_state"))
    )
    (net (code "79") (name "/DAC_1_1") (class "Default")
      (node (ref "HD2") (pin "27") (pinfunction "27_27") (pintype "passive"))
      (node (ref "U4") (pin "2") (pinfunction "OUT0_2") (pintype "output"))
    )
    (net (code "80") (name "/DAC_1_2") (class "Default")
      (node (ref "HD2") (pin "25") (pinfunction "25_25") (pintype "passive"))
      (node (ref "U4") (pin "3") (pinfunction "OUT1_3") (pintype "output"))
    )
    (net (code "81") (name "/DAC_1_3") (class "Default")
      (node (ref "HD2") (pin "23") (pinfunction "23_23") (pintype "passive"))
      (node (ref "U4") (pin "4") (pinfunction "OUT2_4") (pintype "output"))
    )
    (net (code "82") (name "/DAC_1_4") (class "Default")
      (node (ref "HD2") (pin "21") (pinfunction "21_21") (pintype "passive"))
      (node (ref "U4") (pin "5") (pinfunction "OUT3_5") (pintype "output"))
    )
    (net (code "83") (name "/DAC_1_5") (class "Default")
      (node (ref "HD2") (pin "19") (pinfunction "19_19") (pintype "passive"))
      (node (ref "U4") (pin "8") (pinfunction "OUT4_8") (pintype "output"))
    )
    (net (code "84") (name "/DAC_1_6") (class "Default")
      (node (ref "HD2") (pin "17") (pinfunction "17_17") (pintype "passive"))
      (node (ref "U4") (pin "9") (pinfunction "OUT5_9") (pintype "output"))
    )
    (net (code "85") (name "/DAC_1_7") (class "Default")
      (node (ref "HD2") (pin "15") (pinfunction "15_15") (pintype "passive"))
      (node (ref "U4") (pin "10") (pinfunction "OUT6_10") (pintype "output"))
    )
    (net (code "86") (name "/DAC_1_8") (class "Default")
      (node (ref "HD2") (pin "13") (pinfunction "13_13") (pintype "passive"))
      (node (ref "U4") (pin "11") (pinfunction "OUT7_11") (pintype "output"))
    )
    (net (code "87") (name "/DAC_2_1") (class "Default")
      (node (ref "HD1") (pin "8") (pinfunction "8_8") (pintype "passive"))
      (node (ref "U5") (pin "2") (pinfunction "OUT0_2") (pintype "output"))
    )
    (net (code "88") (name "/DAC_2_2") (class "Default")
      (node (ref "HD1") (pin "10") (pinfunction "10_10") (pintype "passive"))
      (node (ref "U5") (pin "3") (pinfunction "OUT1_3") (pintype "output"))
    )
    (net (code "89") (name "/DAC_2_3") (class "Default")
      (node (ref "HD1") (pin "12") (pinfunction "12_12") (pintype "passive"))
      (node (ref "U5") (pin "4") (pinfunction "OUT2_4") (pintype "output"))
    )
    (net (code "90") (name "/DAC_2_4") (class "Default")
      (node (ref "HD1") (pin "14") (pinfunction "14_14") (pintype "passive"))
      (node (ref "U5") (pin "5") (pinfunction "OUT3_5") (pintype "output"))
    )
    (net (code "91") (name "/DAC_2_5") (class "Default")
      (node (ref "HD1") (pin "16") (pinfunction "16_16") (pintype "passive"))
      (node (ref "U5") (pin "8") (pinfunction "OUT4_8") (pintype "output"))
    )
    (net (code "92") (name "/DAC_2_6") (class "Default")
      (node (ref "HD1") (pin "18") (pinfunction "18_18") (pintype "passive"))
      (node (ref "U5") (pin "9") (pinfunction "OUT5_9") (pintype "output"))
    )
    (net (code "93") (name "/DAC_2_7") (class "Default")
      (node (ref "HD1") (pin "20") (pinfunction "20_20") (pintype "passive"))
      (node (ref "U5") (pin "10") (pinfunction "OUT6_10") (pintype "output"))
    )
    (net (code "94") (name "/DAC_2_8") (class "Default")
      (node (ref "HD1") (pin "22") (pinfunction "22_22") (pintype "passive"))
      (node (ref "U5") (pin "11") (pinfunction "OUT7_11") (pintype "output"))
    )
    (net (code "95") (name "/DAC_3_1") (class "Default")
      (node (ref "HD1") (pin "26") (pinfunction "26_26") (pintype "passive"))
      (node (ref "U6") (pin "2") (pinfunction "OUT0_2") (pintype "output"))
    )
    (net (code "96") (name "/DAC_3_2") (class "Default")
      (node (ref "HD1") (pin "28") (pinfunction "28_28") (pintype "passive"))
      (node (ref "U6") (pin "3") (pinfunction "OUT1_3") (pintype "output"))
    )
    (net (code "97") (name "/DAC_3_3") (class "Default")
      (node (ref "HD1") (pin "30") (pinfunction "30_30") (pintype "passive"))
      (node (ref "U6") (pin "4") (pinfunction "OUT2_4") (pintype "output"))
    )
    (net (code "98") (name "/DAC_3_4") (class "Default")
      (node (ref "HD1") (pin "32") (pinfunction "32_32") (pintype "passive"))
      (node (ref "U6") (pin "5") (pinfunction "OUT3_5") (pintype "output"))
    )
    (net (code "99") (name "/DAC_3_5") (class "Default")
      (node (ref "HD1") (pin "34") (pinfunction "34_34") (pintype "passive"))
      (node (ref "U6") (pin "8") (pinfunction "OUT4_8") (pintype "output"))
    )
    (net (code "100") (name "/DAC_3_6") (class "Default")
      (node (ref "HD1") (pin "36") (pinfunction "36_36") (pintype "passive"))
      (node (ref "U6") (pin "9") (pinfunction "OUT5_9") (pintype "output"))
    )
    (net (code "101") (name "/DAC_3_7") (class "Default")
      (node (ref "HD1") (pin "38") (pinfunction "38_38") (pintype "passive"))
      (node (ref "U6") (pin "10") (pinfunction "OUT6_10") (pintype "output"))
    )
    (net (code "102") (name "/DAC_3_8") (class "Default")
      (node (ref "HD1") (pin "40") (pinfunction "40_40") (pintype "passive"))
      (node (ref "U6") (pin "11") (pinfunction "OUT7_11") (pintype "output"))
    )
    (net (code "103") (name "/DAC_4_1") (class "Default")
      (node (ref "C65") (pin "2") (pinfunction "2_2") (pintype "passive"))
      (node (ref "HD1") (pin "7") (pinfunction "7_7") (pintype "passive"))
      (node (ref "R11") (pin "2") (pinfunction "2_2") (pintype "passive"))
    )
    (net (code "104") (name "/DAC_4_1r") (class "Default")
      (node (ref "R11") (pin "1") (pinfunction "1_1") (pintype "passive"))
      (node (ref "U7") (pin "2") (pinfunction "OUT0_2") (pintype "output"))
    )
    (net (code "105") (name "/DAC_4_2") (class "Default")
      (node (ref "C66") (pin "2") (pinfunction "2_2") (pintype "passive"))
      (node (ref "HD1") (pin "9") (pinfunction "9_9") (pintype "passive"))
      (node (ref "R12") (pin "2") (pinfunction "2_2") (pintype "passive"))
    )
    (net (code "106") (name "/DAC_4_2r") (class "Default")
      (node (ref "R12") (pin "1") (pinfunction "1_1") (pintype "passive"))
      (node (ref "U7") (pin "3") (pinfunction "OUT1_3") (pintype "output"))
    )
    (net (code "107") (name "/DAC_4_3") (class "Default")
      (node (ref "C67") (pin "2") (pinfunction "2_2") (pintype "passive"))
      (node (ref "HD1") (pin "11") (pinfunction "11_11") (pintype "passive"))
      (node (ref "R13") (pin "2") (pinfunction "2_2") (pintype "passive"))
    )
    (net (code "108") (name "/DAC_4_3r") (class "Default")
      (node (ref "R13") (pin "1") (pinfunction "1_1") (pintype "passive"))
      (node (ref "U7") (pin "4") (pinfunction "OUT2_4") (pintype "output"))
    )
    (net (code "109") (name "/DAC_4_4") (class "Default")
      (node (ref "C68") (pin "2") (pinfunction "2_2") (pintype "passive"))
      (node (ref "HD1") (pin "13") (pinfunction "13_13") (pintype "passive"))
      (node (ref "R14") (pin "2") (pinfunction "2_2") (pintype "passive"))
    )
    (net (code "110") (name "/DAC_4_4r") (class "Default")
      (node (ref "R14") (pin "1") (pinfunction "1_1") (pintype "passive"))
      (node (ref "U7") (pin "5") (pinfunction "OUT3_5") (pintype "output"))
    )
    (net (code "111") (name "/DAC_4_5") (class "Default")
      (node (ref "C69") (pin "2") (pinfunction "2_2") (pintype "passive"))
      (node (ref "HD1") (pin "15") (pinfunction "15_15") (pintype "passive"))
      (node (ref "R15") (pin "2") (pinfunction "2_2") (pintype "passive"))
    )
    (net (code "112") (name "/DAC_4_5r") (class "Default")
      (node (ref "R15") (pin "1") (pinfunction "1_1") (pintype "passive"))
      (node (ref "U7") (pin "8") (pinfunction "OUT4_8") (pintype "output"))
    )
    (net (code "113") (name "/DAC_4_6") (class "Default")
      (node (ref "C70") (pin "2") (pinfunction "2_2") (pintype "passive"))
      (node (ref "HD1") (pin "17") (pinfunction "17_17") (pintype "passive"))
      (node (ref "R16") (pin "2") (pinfunction "2_2") (pintype "passive"))
    )
    (net (code "114") (name "/DAC_4_6r") (class "Default")
      (node (ref "R16") (pin "1") (pinfunction "1_1") (pintype "passive"))
      (node (ref "U7") (pin "9") (pinfunction "OUT5_9") (pintype "output"))
    )
    (net (code "115") (name "/DAC_4_7") (class "Default")
      (node (ref "C71") (pin "2") (pinfunction "2_2") (pintype "passive"))
      (node (ref "HD1") (pin "19") (pinfunction "19_19") (pintype "passive"))
      (node (ref "R17") (pin "2") (pinfunction "2_2") (pintype "passive"))
    )
    (net (code "116") (name "/DAC_4_7r") (class "Default")
      (node (ref "R17") (pin "1") (pinfunction "1_1") (pintype "passive"))
      (node (ref "U7") (pin "10") (pinfunction "OUT6_10") (pintype "output"))
    )
    (net (code "117") (name "/DAC_4_8") (class "Default")
      (node (ref "C72") (pin "2") (pinfunction "2_2") (pintype "passive"))
      (node (ref "HD1") (pin "21") (pinfunction "21_21") (pintype "passive"))
      (node (ref "R18") (pin "2") (pinfunction "2_2") (pintype "passive"))
    )
    (net (code "118") (name "/DAC_4_8r") (class "Default")
      (node (ref "R18") (pin "1") (pinfunction "1_1") (pintype "passive"))
      (node (ref "U7") (pin "11") (pinfunction "OUT7_11") (pintype "output"))
    )
    (net (code "119") (name "/DAC_5_1") (class "Default")
      (node (ref "C81") (pin "2") (pinfunction "2_2") (pintype "passive"))
      (node (ref "HD1") (pin "25") (pinfunction "25_25") (pintype "passive"))
      (node (ref "R19") (pin "2") (pinfunction "2_2") (pintype "passive"))
    )
    (net (code "120") (name "/DAC_5_1r") (class "Default")
      (node (ref "R19") (pin "1") (pinfunction "1_1") (pintype "passive"))
      (node (ref "U8") (pin "2") (pinfunction "OUT0_2") (pintype "output"))
    )
    (net (code "121") (name "/DAC_5_2") (class "Default")
      (node (ref "C82") (pin "2") (pinfunction "2_2") (pintype "passive"))
      (node (ref "HD1") (pin "27") (pinfunction "27_27") (pintype "passive"))
      (node (ref "R20") (pin "2") (pinfunction "2_2") (pintype "passive"))
    )
    (net (code "122") (name "/DAC_5_2r") (class "Default")
      (node (ref "R20") (pin "1") (pinfunction "1_1") (pintype "passive"))
      (node (ref "U8") (pin "3") (pinfunction "OUT1_3") (pintype "output"))
    )
    (net (code "123") (name "/DAC_5_3") (class "Default")
      (node (ref "C83") (pin "2") (pinfunction "2_2") (pintype "passive"))
      (node (ref "HD1") (pin "29") (pinfunction "29_29") (pintype "passive"))
      (node (ref "R21") (pin "2") (pinfunction "2_2") (pintype "passive"))
    )
    (net (code "124") (name "/DAC_5_3r") (class "Default")
      (node (ref "R21") (pin "1") (pinfunction "1_1") (pintype "passive"))
      (node (ref "U8") (pin "4") (pinfunction "OUT2_4") (pintype "output"))
    )
    (net (code "125") (name "/DAC_5_4") (class "Default")
      (node (ref "C84") (pin "2") (pinfunction "2_2") (pintype "passive"))
      (node (ref "HD1") (pin "31") (pinfunction "31_31") (pintype "passive"))
      (node (ref "R22") (pin "2") (pinfunction "2_2") (pintype "passive"))
    )
    (net (code "126") (name "/DAC_5_4r") (class "Default")
      (node (ref "R22") (pin "1") (pinfunction "1_1") (pintype "passive"))
      (node (ref "U8") (pin "5") (pinfunction "OUT3_5") (pintype "output"))
    )
    (net (code "127") (name "/DAC_5_5") (class "Default")
      (node (ref "C85") (pin "2") (pinfunction "2_2") (pintype "passive"))
      (node (ref "HD1") (pin "33") (pinfunction "33_33") (pintype "passive"))
      (node (ref "R23") (pin "2") (pinfunction "2_2") (pintype "passive"))
    )
    (net (code "128") (name "/DAC_5_5r") (class "Default")
      (node (ref "R23") (pin "1") (pinfunction "1_1") (pintype "passive"))
      (node (ref "U8") (pin "8") (pinfunction "OUT4_8") (pintype "output"))
    )
    (net (code "129") (name "/DAC_5_6") (class "Default")
      (node (ref "C86") (pin "2") (pinfunction "2_2") (pintype "passive"))
      (node (ref "HD1") (pin "35") (pinfunction "35_35") (pintype "passive"))
      (node (ref "R24") (pin "2") (pinfunction "2_2") (pintype "passive"))
    )
    (net (code "130") (name "/DAC_5_6r") (class "Default")
      (node (ref "R24") (pin "1") (pinfunction "1_1") (pintype "passive"))
      (node (ref "U8") (pin "9") (pinfunction "OUT5_9") (pintype "output"))
    )
    (net (code "131") (name "/DAC_5_7") (class "Default")
      (node (ref "C87") (pin "2") (pinfunction "2_2") (pintype "passive"))
      (node (ref "HD1") (pin "37") (pinfunction "37_37") (pintype "passive"))
      (node (ref "R25") (pin "2") (pinfunction "2_2") (pintype "passive"))
    )
    (net (code "132") (name "/DAC_5_7r") (class "Default")
      (node (ref "R25") (pin "1") (pinfunction "1_1") (pintype "passive"))
      (node (ref "U8") (pin "10") (pinfunction "OUT6_10") (pintype "output"))
    )
    (net (code "133") (name "/DAC_5_8") (class "Default")
      (node (ref "C88") (pin "2") (pinfunction "2_2") (pintype "passive"))
      (node (ref "HD1") (pin "39") (pinfunction "39_39") (pintype "passive"))
      (node (ref "R26") (pin "2") (pinfunction "2_2") (pintype "passive"))
    )
    (net (code "134") (name "/DAC_5_8r") (class "Default")
      (node (ref "R26") (pin "1") (pinfunction "1_1") (pintype "passive"))
      (node (ref "U8") (pin "11") (pinfunction "OUT7_11") (pintype "output"))
    )
    (net (code "135") (name "/DAC_CSn") (class "Default")
      (node (ref "JP_DAC_4") (pin "2") (pinfunction "2_2") (pintype "passive"))
      (node (ref "U4") (pin "12") (pinfunction "~{CS}_12") (pintype "input"))
      (node (ref "U5") (pin "12") (pinfunction "~{CS}_12") (pintype "input"))
      (node (ref "U6") (pin "12") (pinfunction "~{CS}_12") (pintype "input"))
      (node (ref "U7") (pin "12") (pinfunction "~{CS}_12") (pintype "input"))
      (node (ref "U8") (pin "12") (pinfunction "~{CS}_12") (pintype "input"))
    )
    (net (code "136") (name "/DAC_SCK") (class "Default")
      (node (ref "JP_DAC_2") (pin "2") (pinfunction "2_2") (pintype "passive"))
      (node (ref "U4") (pin "13") (pinfunction "SCLK_13") (pintype "input"))
      (node (ref "U5") (pin "13") (pinfunction "SCLK_13") (pintype "input"))
      (node (ref "U6") (pin "13") (pinfunction "SCLK_13") (pintype "input"))
      (node (ref "U7") (pin "13") (pinfunction "SCLK_13") (pintype "input"))
      (node (ref "U8") (pin "13") (pinfunction "SCLK_13") (pintype "input"))
    )
    (net (code "137") (name "/DAC_SDI") (class "Default")
      (node (ref "JP_DAC_3") (pin "2") (pinfunction "2_2") (pintype "passive"))
      (node (ref "U4") (pin "14") (pinfunction "SDI_14") (pintype "input"))
    )
    (net (code "138") (name "/DAQ_AI0") (class "Default")
      (node (ref "HD0") (pin "38") (pinfunction "38_38") (pintype "passive"))
      (node (ref "JP6") (pin "2") (pinfunction "2_2") (pintype "passive"))
    )
    (net (code "139") (name "/DAQ_AI0B") (class "Default")
      (node (ref "B0") (pin "68") (pinfunction "68_68") (pintype "passive"))
      (node (ref "JP6") (pin "3") (pinfunction "3_3") (pintype "passive"))
      (node (ref "R66") (pin "1") (pinfunction "1_1") (pintype "passive"))
    )
    (net (code "140") (name "/DAQ_AI0bi") (class "Default")
      (node (ref "JP6") (pin "1") (pinfunction "1_1") (pintype "passive"))
      (node (ref "U10") (pin "3") (pinfunction "+IN_A_3") (pintype "tri_state"))
    )
    (net (code "141") (name "/DAQ_AI1") (class "Default")
      (node (ref "HD0") (pin "40") (pinfunction "40_40") (pintype "passive"))
      (node (ref "JP7") (pin "2") (pinfunction "2_2") (pintype "passive"))
    )
    (net (code "142") (name "/DAQ_AI1B") (class "Default")
      (node (ref "B0") (pin "33") (pinfunction "33_33") (pintype "passive"))
      (node (ref "JP7") (pin "3") (pinfunction "3_3") (pintype "passive"))
      (node (ref "R69") (pin "1") (pinfunction "1_1") (pintype "passive"))
    )
    (net (code "143") (name "/DAQ_AI1in") (class "Default")
      (node (ref "JP7") (pin "1") (pinfunction "1_1") (pintype "passive"))
      (node (ref "U10") (pin "5") (pinfunction "+IN_B_5") (pintype "tri_state"))
    )
    (net (code "144") (name "/DAQ_AI2") (class "Default")
      (node (ref "HD0") (pin "39") (pinfunction "39_39") (pintype "passive"))
      (node (ref "JP8") (pin "2") (pinfunction "2_2") (pintype "passive"))
    )
    (net (code "145") (name "/DAQ_AI2B") (class "Default")
      (node (ref "B0") (pin "65") (pinfunction "65_65") (pintype "passive"))
      (node (ref "JP8") (pin "3") (pinfunction "3_3") (pintype "passive"))
      (node (ref "R68") (pin "2") (pinfunction "2_2") (pintype "passive"))
    )
    (net (code "146") (name "/DAQ_AI2in") (class "Default")
      (node (ref "JP8") (pin "1") (pinfunction "1_1") (pintype "passive"))
      (node (ref "U10") (pin "10") (pinfunction "+IN_C_10") (pintype "tri_state"))
    )
    (net (code "147") (name "/DAQ_AI3") (class "Default")
      (node (ref "HD0") (pin "37") (pinfunction "37_37") (pintype "passive"))
      (node (ref "JP10") (pin "2") (pinfunction "2_2") (pintype "passive"))
    )
    (net (code "148") (name "/DAQ_AI3B") (class "Default")
      (node (ref "B0") (pin "30") (pinfunction "30_30") (pintype "passive"))
      (node (ref "JP10") (pin "3") (pinfunction "3_3") (pintype "passive"))
      (node (ref "R67") (pin "2") (pinfunction "2_2") (pintype "passive"))
    )
    (net (code "149") (name "/DAQ_AI3in") (class "Default")
      (node (ref "JP10") (pin "1") (pinfunction "1_1") (pintype "passive"))
      (node (ref "U10") (pin "12") (pinfunction "+IN_D_12") (pintype "tri_state"))
    )
    (net (code "150") (name "/DAQ_AI4") (class "Default")
      (node (ref "B0") (pin "28") (pinfunction "28_28") (pintype "passive"))
      (node (ref "HD0") (pin "33") (pinfunction "33_33") (pintype "passive"))
    )
    (net (code "151") (name "/DAQ_AI5") (class "Default")
      (node (ref "B0") (pin "60") (pinfunction "60_60") (pintype "passive"))
      (node (ref "HD0") (pin "34") (pinfunction "34_34") (pintype "passive"))
    )
    (net (code "152") (name "/DAQ_AI6") (class "Default")
      (node (ref "B0") (pin "25") (pinfunction "25_25") (pintype "passive"))
      (node (ref "HD0") (pin "31") (pinfunction "31_31") (pintype "passive"))
    )
    (net (code "153") (name "/DAQ_AI7") (class "Default")
      (node (ref "B0") (pin "57") (pinfunction "57_57") (pintype "passive"))
      (node (ref "HD0") (pin "32") (pinfunction "32_32") (pintype "passive"))
    )
    (net (code "154") (name "/DAQ_AI8") (class "Default")
      (node (ref "B0") (pin "34") (pinfunction "34_34") (pintype "passive"))
      (node (ref "HD3") (pin "40") (pinfunction "40_40") (pintype "passive"))
    )
    (net (code "155") (name "/DAQ_AI9") (class "Default")
      (node (ref "B0") (pin "66") (pinfunction "66_66") (pintype "passive"))
      (node (ref "HD3") (pin "39") (pinfunction "39_39") (pintype "passive"))
    )
    (net (code "156") (name "/DAQ_AI10") (class "Default")
      (node (ref "B0") (pin "31") (pinfunction "31_31") (pintype "passive"))
      (node (ref "HD3") (pin "38") (pinfunction "38_38") (pintype "passive"))
    )
    (net (code "157") (name "/DAQ_AI11") (class "Default")
      (node (ref "B0") (pin "63") (pinfunction "63_63") (pintype "passive"))
      (node (ref "HD3") (pin "37") (pinfunction "37_37") (pintype "passive"))
    )
    (net (code "158") (name "/DAQ_AI12") (class "Default")
      (node (ref "B0") (pin "61") (pinfunction "61_61") (pintype "passive"))
      (node (ref "HD3") (pin "36") (pinfunction "36_36") (pintype "passive"))
    )
    (net (code "159") (name "/DAQ_AI13") (class "Default")
      (node (ref "B0") (pin "26") (pinfunction "26_26") (pintype "passive"))
      (node (ref "HD3") (pin "35") (pinfunction "35_35") (pintype "passive"))
    )
    (net (code "160") (name "/DAQ_AI14") (class "Default")
      (node (ref "B0") (pin "58") (pinfunction "58_58") (pintype "passive"))
      (node (ref "HD3") (pin "34") (pinfunction "34_34") (pintype "passive"))
    )
    (net (code "161") (name "/DAQ_AI15") (class "Default")
      (node (ref "B0") (pin "23") (pinfunction "23_23") (pintype "passive"))
      (node (ref "HD3") (pin "33") (pinfunction "33_33") (pintype "passive"))
    )
    (net (code "162") (name "/DAQ_AIGND0") (class "Default")
      (node (ref "B0") (pin "24") (pinfunction "24_24") (pintype "passive"))
      (node (ref "B0") (pin "27") (pinfunction "27_27") (pintype "passive"))
      (node (ref "B0") (pin "29") (pinfunction "29_29") (pintype "passive"))
      (node (ref "B0") (pin "32") (pinfunction "32_32") (pintype "passive"))
      (node (ref "B0") (pin "56") (pinfunction "56_56") (pintype "passive"))
      (node (ref "B0") (pin "59") (pinfunction "59_59") (pintype "passive"))
      (node (ref "B0") (pin "64") (pinfunction "64_64") (pintype "passive"))
      (node (ref "B0") (pin "67") (pinfunction "67_67") (pintype "passive"))
      (node (ref "HD0") (pin "29") (pinfunction "29_29") (pintype "passive"))
      (node (ref "HD0") (pin "35") (pinfunction "35_35") (pintype "passive"))
      (node (ref "HD0") (pin "36") (pinfunction "36_36") (pintype "passive"))
      (node (ref "HD3") (pin "31") (pinfunction "31_31") (pintype "passive"))
      (node (ref "HD3") (pin "32") (pinfunction "32_32") (pintype "passive"))
      (node (ref "L4") (pin "2") (pinfunction "2_2") (pintype "passive"))
    )
    (net (code "163") (name "/DAQ_AISENSE0") (class "Default")
      (node (ref "B0") (pin "62") (pinfunction "62_62") (pintype "passive"))
      (node (ref "HD0") (pin "30") (pinfunction "30_30") (pintype "passive"))
    )
    (net (code "164") (name "/DAQ_AO0") (class "Default")
      (node (ref "B0") (pin "22") (pinfunction "22_22") (pintype "passive"))
      (node (ref "HD3") (pin "30") (pinfunction "30_30") (pintype "passive"))
    )
    (net (code "165") (name "/DAQ_AO1") (class "Default")
      (node (ref "B0") (pin "21") (pinfunction "21_21") (pintype "passive"))
      (node (ref "HD3") (pin "29") (pinfunction "29_29") (pintype "passive"))
    )
    (net (code "166") (name "/DAQ_AOGND0") (class "Default")
      (node (ref "B0") (pin "54") (pinfunction "54_54") (pintype "passive"))
      (node (ref "B0") (pin "55") (pinfunction "55_55") (pintype "passive"))
      (node (ref "HD3") (pin "28") (pinfunction "28_28") (pintype "passive"))
      (node (ref "L5") (pin "2") (pinfunction "2_2") (pintype "passive"))
    )
    (net (code "167") (name "/DAQ_DGND0") (class "Default")
      (node (ref "B0") (pin "15") (pinfunction "15_15") (pintype "passive"))
      (node (ref "HD3") (pin "25") (pinfunction "25_25") (pintype "passive"))
      (node (ref "HD3") (pin "26") (pinfunction "26_26") (pintype "passive"))
    )
    (net (code "168") (name "/DAQ_DIO0") (class "Default")
      (node (ref "B0") (pin "52") (pinfunction "52_52") (pintype "passive"))
      (node (ref "U11") (pin "21") (pinfunction "B1_21") (pintype "output"))
    )
    (net (code "169") (name "/DAQ_DIO0t") (class "Default")
      (node (ref "HD3") (pin "15") (pinfunction "15_15") (pintype "passive"))
      (node (ref "U11") (pin "3") (pinfunction "A1_3") (pintype "output"))
    )
    (net (code "170") (name "/DAQ_DIO1") (class "Default")
      (node (ref "B0") (pin "17") (pinfunction "17_17") (pintype "passive"))
      (node (ref "JP_DAC_3") (pin "1") (pinfunction "1_1") (pintype "passive"))
      (node (ref "U11") (pin "20") (pinfunction "B2_20") (pintype "output"))
    )
    (net (code "171") (name "/DAQ_DIO1t") (class "Default")
      (node (ref "HD3") (pin "13") (pinfunction "13_13") (pintype "passive"))
      (node (ref "U11") (pin "4") (pinfunction "A2_4") (pintype "output"))
    )
    (net (code "172") (name "/DAQ_DIO2") (class "Default")
      (node (ref "B0") (pin "49") (pinfunction "49_49") (pintype "passive"))
      (node (ref "JP_DAC_2") (pin "1") (pinfunction "1_1") (pintype "passive"))
      (node (ref "U11") (pin "19") (pinfunction "B3_19") (pintype "output"))
    )
    (net (code "173") (name "/DAQ_DIO2t") (class "Default")
      (node (ref "HD3") (pin "11") (pinfunction "11_11") (pintype "passive"))
      (node (ref "U11") (pin "5") (pinfunction "A3_5") (pintype "output"))
    )
    (net (code "174") (name "/DAQ_DIO3") (class "Default")
      (node (ref "B0") (pin "47") (pinfunction "47_47") (pintype "passive"))
      (node (ref "JP_DAC_4") (pin "1") (pinfunction "1_1") (pintype "passive"))
      (node (ref "U11") (pin "18") (pinfunction "B4_18") (pintype "output"))
    )
    (net (code "175") (name "/DAQ_DIO3t") (class "Default")
      (node (ref "HD3") (pin "9") (pinfunction "9_9") (pintype "passive"))
      (node (ref "U11") (pin "6") (pinfunction "A4_6") (pintype "output"))
    )
    (net (code "176") (name "/DAQ_DIO4") (class "Default")
      (node (ref "B0") (pin "19") (pinfunction "19_19") (pintype "passive"))
      (node (ref "U11") (pin "17") (pinfunction "B5_17") (pintype "output"))
    )
    (net (code "177") (name "/DAQ_DIO4t") (class "Default")
      (node (ref "HD3") (pin "7") (pinfunction "7_7") (pintype "passive"))
      (node (ref "U11") (pin "7") (pinfunction "A5_7") (pintype "output"))
    )
    (net (code "178") (name "/DAQ_DIO5") (class "Default")
      (node (ref "B0") (pin "51") (pinfunction "51_51") (pintype "passive"))
      (node (ref "U11") (pin "16") (pinfunction "B6_16") (pintype "output"))
    )
    (net (code "179") (name "/DAQ_DIO5t") (class "Default")
      (node (ref "HD3") (pin "5") (pinfunction "5_5") (pintype "passive"))
      (node (ref "U11") (pin "8") (pinfunction "A6_8") (pintype "output"))
    )
    (net (code "180") (name "/DAQ_DIO6") (class "Default")
      (node (ref "B0") (pin "16") (pinfunction "16_16") (pintype "passive"))
      (node (ref "U11") (pin "15") (pinfunction "B7_15") (pintype "output"))
    )
    (net (code "181") (name "/DAQ_DIO6t") (class "Default")
      (node (ref "HD3") (pin "3") (pinfunction "3_3") (pintype "passive"))
      (node (ref "U11") (pin "9") (pinfunction "A7_9") (pintype "output"))
    )
    (net (code "182") (name "/DAQ_DIO7") (class "Default")
      (node (ref "B0") (pin "48") (pinfunction "48_48") (pintype "passive"))
      (node (ref "U11") (pin "14") (pinfunction "B8_14") (pintype "output"))
    )
    (net (code "183") (name "/DAQ_DIO7t") (class "Default")
      (node (ref "HD3") (pin "1") (pinfunction "1_1") (pintype "passive"))
      (node (ref "U11") (pin "10") (pinfunction "A8_10") (pintype "output"))
    )
    (net (code "184") (name "/DAQ_DVDD5") (class "Default")
      (node (ref "B0") (pin "14") (pinfunction "14_14") (pintype "passive"))
      (node (ref "B0") (pin "8") (pinfunction "8_8") (pintype "passive"))
      (node (ref "C50") (pin "2") (pinfunction "2_2") (pintype "passive"))
      (node (ref "C51") (pin "2") (pinfunction "2_2") (pintype "passive"))
      (node (ref "HD3") (pin "27") (pinfunction "27_27") (pintype "passive"))
      (node (ref "JP4") (pin "1") (pinfunction "1_1") (pintype "passive"))
      (node (ref "JP_DVDD") (pin "1") (pinfunction "1_1") (pintype "passive"))
      (node (ref "U11") (pin "23") (pinfunction "VCCB_23") (pintype "power_in"))
      (node (ref "U11") (pin "24") (pinfunction "VCCB_24") (pintype "power_in"))
    )
    (net (code "185") (name "/DAQ_PFI0") (class "Default")
      (node (ref "B0") (pin "11") (pinfunction "11_11") (pintype "passive"))
      (node (ref "HD3") (pin "23") (pinfunction "23_23") (pintype "passive"))
    )
    (net (code "186") (name "/DAQ_PFI1") (class "Default")
      (node (ref "B0") (pin "10") (pinfunction "10_10") (pintype "passive"))
      (node (ref "HD3") (pin "21") (pinfunction "21_21") (pintype "passive"))
    )
    (net (code "187") (name "/DAQ_PFI2") (class "Default")
      (node (ref "B0") (pin "43") (pinfunction "43_43") (pintype "passive"))
      (node (ref "HD3") (pin "19") (pinfunction "19_19") (pintype "passive"))
    )
    (net (code "188") (name "/DAQ_PFI3") (class "Default")
      (node (ref "B0") (pin "42") (pinfunction "42_42") (pintype "passive"))
      (node (ref "HD3") (pin "17") (pinfunction "17_17") (pintype "passive"))
    )
    (net (code "189") (name "/DAQ_PFI4") (class "Default")
      (node (ref "B0") (pin "41") (pinfunction "41_41") (pintype "passive"))
      (node (ref "HD3") (pin "24") (pinfunction "24_24") (pintype "passive"))
    )
    (net (code "190") (name "/DAQ_PFI5") (class "Default")
      (node (ref "B0") (pin "6") (pinfunction "6_6") (pintype "passive"))
      (node (ref "HD3") (pin "22") (pinfunction "22_22") (pintype "passive"))
    )
    (net (code "191") (name "/DAQ_PFI6") (class "Default")
      (node (ref "B0") (pin "5") (pinfunction "5_5") (pintype "passive"))
      (node (ref "HD3") (pin "20") (pinfunction "20_20") (pintype "passive"))
    )
    (net (code "192") (name "/DAQ_PFI7") (class "Default")
      (node (ref "B0") (pin "38") (pinfunction "38_38") (pintype "passive"))
      (node (ref "HD3") (pin "18") (pinfunction "18_18") (pintype "passive"))
    )
    (net (code "193") (name "/DAQ_PFI8") (class "Default")
      (node (ref "B0") (pin "37") (pinfunction "37_37") (pintype "passive"))
      (node (ref "HD3") (pin "16") (pinfunction "16_16") (pintype "passive"))
    )
    (net (code "194") (name "/DAQ_PFI9") (class "Default")
      (node (ref "B0") (pin "3") (pinfunction "3_3") (pintype "passive"))
      (node (ref "HD3") (pin "14") (pinfunction "14_14") (pintype "passive"))
    )
    (net (code "195") (name "/DAQ_PFI10") (class "Default")
      (node (ref "B0") (pin "45") (pinfunction "45_45") (pintype "passive"))
      (node (ref "HD3") (pin "12") (pinfunction "12_12") (pintype "passive"))
    )
    (net (code "196") (name "/DAQ_PFI11") (class "Default")
      (node (ref "B0") (pin "46") (pinfunction "46_46") (pintype "passive"))
      (node (ref "HD3") (pin "10") (pinfunction "10_10") (pintype "passive"))
    )
    (net (code "197") (name "/DAQ_PFI12") (class "Default")
      (node (ref "B0") (pin "2") (pinfunction "2_2") (pintype "passive"))
      (node (ref "HD3") (pin "8") (pinfunction "8_8") (pintype "passive"))
    )
    (net (code "198") (name "/DAQ_PFI13") (class "Default")
      (node (ref "B0") (pin "40") (pinfunction "40_40") (pintype "passive"))
      (node (ref "HD3") (pin "6") (pinfunction "6_6") (pintype "passive"))
    )
    (net (code "199") (name "/DAQ_PFI14") (class "Default")
      (node (ref "B0") (pin "1") (pinfunction "1_1") (pintype "passive"))
      (node (ref "HD3") (pin "4") (pinfunction "4_4") (pintype "passive"))
    )
    (net (code "200") (name "/DAQ_PFI15") (class "Default")
      (node (ref "B0") (pin "39") (pinfunction "39_39") (pintype "passive"))
      (node (ref "HD3") (pin "2") (pinfunction "2_2") (pintype "passive"))
    )
    (net (code "201") (name "/DVDD1.8") (class "Default")
      (node (ref "HD0") (pin "2") (pinfunction "2_2") (pintype "passive"))
      (node (ref "JP5") (pin "2") (pinfunction "2_2") (pintype "passive"))
      (node (ref "JP_VLT") (pin "3") (pinfunction "3_3") (pintype "passive"))
      (node (ref "JP_VLT1") (pin "3") (pinfunction "3_3") (pintype "passive"))
      (node (ref "Q1") (pin "1") (pinfunction "G_1") (pintype "passive"))
      (node (ref "R10") (pin "2") (pinfunction "2_2") (pintype "passive"))
    )
    (net (code "202") (name "/MCU_ADC1") (class "Default")
      (node (ref "HD0") (pin "21") (pinfunction "21_21") (pintype "passive"))
      (node (ref "R92") (pin "1") (pinfunction "1_1") (pintype "passive"))
      (node (ref "U13") (pin "23") (pinfunction "PA1_23") (pintype "bidirectional"))
    )
    (net (code "203") (name "/MCU_ADC2") (class "Default")
      (node (ref "HD0") (pin "23") (pinfunction "23_23") (pintype "passive"))
      (node (ref "R93") (pin "1") (pinfunction "1_1") (pintype "passive"))
      (node (ref "U13") (pin "24") (pinfunction "PA2_24") (pintype "bidirectional"))
    )
    (net (code "204") (name "/MCU_ADC3") (class "Default")
      (node (ref "HD0") (pin "25") (pinfunction "25_25") (pintype "passive"))
      (node (ref "R94") (pin "1") (pinfunction "1_1") (pintype "passive"))
      (node (ref "U13") (pin "25") (pinfunction "PA3_25") (pintype "bidirectional"))
    )
    (net (code "205") (name "/MCU_ADC4") (class "Default")
      (node (ref "HD0") (pin "27") (pinfunction "27_27") (pintype "passive"))
      (node (ref "R95") (pin "1") (pinfunction "1_1") (pintype "passive"))
      (node (ref "U13") (pin "28") (pinfunction "PA4_28") (pintype "bidirectional"))
    )
    (net (code "206") (name "/MCU_DAC_CLRn") (class "Default")
      (node (ref "U13") (pin "47") (pinfunction "PB11_47") (pintype "bidirectional"))
    )
    (net (code "207") (name "/MCU_DAC_CSn") (class "Default")
      (node (ref "JP_DAC_4") (pin "3") (pinfunction "3_3") (pintype "passive"))
      (node (ref "U13") (pin "41") (pinfunction "PE11_41") (pintype "bidirectional"))
    )
    (net (code "208") (name "/MCU_DAC_SCK") (class "Default")
      (node (ref "JP_DAC_2") (pin "3") (pinfunction "3_3") (pintype "passive"))
      (node (ref "U13") (pin "42") (pinfunction "PE12_42") (pintype "bidirectional"))
    )
    (net (code "209") (name "/MCU_DAC_SDI") (class "Default")
      (node (ref "JP_DAC_3") (pin "3") (pinfunction "3_3") (pintype "passive"))
      (node (ref "U13") (pin "44") (pinfunction "PE14_44") (pintype "bidirectional"))
    )
    (net (code "210") (name "/MCU_DIO0") (class "Default")
      (node (ref "R70") (pin "1") (pinfunction "1_1") (pintype "passive"))
      (node (ref "U19") (pin "21") (pinfunction "B1_21") (pintype "output"))
    )
    (net (code "211") (name "/MCU_DIO0t") (class "Default")
      (node (ref "HD0") (pin "20") (pinfunction "20_20") (pintype "passive"))
      (node (ref "U19") (pin "3") (pinfunction "A1_3") (pintype "output"))
    )
    (net (code "212") (name "/MCU_DIO1") (class "Default")
      (node (ref "R71") (pin "1") (pinfunction "1_1") (pintype "passive"))
      (node (ref "U19") (pin "20") (pinfunction "B2_20") (pintype "output"))
    )
    (net (code "213") (name "/MCU_DIO1t") (class "Default")
      (node (ref "HD0") (pin "18") (pinfunction "18_18") (pintype "passive"))
      (node (ref "U19") (pin "4") (pinfunction "A2_4") (pintype "output"))
    )
    (net (code "214") (name "/MCU_DIO2") (class "Default")
      (node (ref "R72") (pin "1") (pinfunction "1_1") (pintype "passive"))
      (node (ref "U19") (pin "19") (pinfunction "B3_19") (pintype "output"))
    )
    (net (code "215") (name "/MCU_DIO2t") (class "Default")
      (node (ref "HD0") (pin "16") (pinfunction "16_16") (pintype "passive"))
      (node (ref "U19") (pin "5") (pinfunction "A3_5") (pintype "output"))
    )
    (net (code "216") (name "/MCU_DIO3") (class "Default")
      (node (ref "R73") (pin "1") (pinfunction "1_1") (pintype "passive"))
      (node (ref "U19") (pin "18") (pinfunction "B4_18") (pintype "output"))
    )
    (net (code "217") (name "/MCU_DIO3t") (class "Default")
      (node (ref "HD0") (pin "14") (pinfunction "14_14") (pintype "passive"))
      (node (ref "U19") (pin "6") (pinfunction "A4_6") (pintype "output"))
    )
    (net (code "218") (name "/MCU_DIO4") (class "Default")
      (node (ref "R74") (pin "1") (pinfunction "1_1") (pintype "passive"))
      (node (ref "U19") (pin "17") (pinfunction "B5_17") (pintype "output"))
    )
    (net (code "219") (name "/MCU_DIO4t") (class "Default")
      (node (ref "HD0") (pin "12") (pinfunction "12_12") (pintype "passive"))
      (node (ref "U19") (pin "7") (pinfunction "A5_7") (pintype "output"))
    )
    (net (code "220") (name "/MCU_DIO5") (class "Default")
      (node (ref "R75") (pin "1") (pinfunction "1_1") (pintype "passive"))
      (node (ref "U19") (pin "16") (pinfunction "B6_16") (pintype "output"))
    )
    (net (code "221") (name "/MCU_DIO5t") (class "Default")
      (node (ref "HD0") (pin "10") (pinfunction "10_10") (pintype "passive"))
      (node (ref "U19") (pin "8") (pinfunction "A6_8") (pintype "output"))
    )
    (net (code "222") (name "/MCU_DIO6") (class "Default")
      (node (ref "R76") (pin "1") (pinfunction "1_1") (pintype "passive"))
      (node (ref "U19") (pin "15") (pinfunction "B7_15") (pintype "output"))
    )
    (net (code "223") (name "/MCU_DIO6t") (class "Default")
      (node (ref "HD0") (pin "8") (pinfunction "8_8") (pintype "passive"))
      (node (ref "U19") (pin "9") (pinfunction "A7_9") (pintype "output"))
    )
    (net (code "224") (name "/MCU_DIO7") (class "Default")
      (node (ref "R77") (pin "1") (pinfunction "1_1") (pintype "passive"))
      (node (ref "U19") (pin "14") (pinfunction "B8_14") (pintype "output"))
    )
    (net (code "225") (name "/MCU_DIO7t") (class "Default")
      (node (ref "HD0") (pin "6") (pinfunction "6_6") (pintype "passive"))
      (node (ref "U19") (pin "10") (pinfunction "A8_10") (pintype "output"))
    )
    (net (code "226") (name "/MCU_DIO8") (class "Default")
      (node (ref "HD0") (pin "7") (pinfunction "7_7") (pintype "passive"))
      (node (ref "R78") (pin "1") (pinfunction "1_1") (pintype "passive"))
    )
    (net (code "227") (name "/MCU_DIO9") (class "Default")
      (node (ref "HD0") (pin "9") (pinfunction "9_9") (pintype "passive"))
      (node (ref "R79") (pin "1") (pinfunction "1_1") (pintype "passive"))
    )
    (net (code "228") (name "/MCU_DIO12{slash}PWM") (class "Default")
      (node (ref "HD0") (pin "11") (pinfunction "11_11") (pintype "passive"))
      (node (ref "R81") (pin "1") (pinfunction "1_1") (pintype "passive"))
    )
    (net (code "229") (name "/MCU_DIO13{slash}PWM") (class "Default")
      (node (ref "HD0") (pin "13") (pinfunction "13_13") (pintype "passive"))
      (node (ref "R82") (pin "1") (pinfunction "1_1") (pintype "passive"))
    )
    (net (code "230") (name "/MCU_DIO14{slash}PWM") (class "Default")
      (node (ref "HD0") (pin "15") (pinfunction "15_15") (pintype "passive"))
      (node (ref "R83") (pin "1") (pinfunction "1_1") (pintype "passive"))
    )
    (net (code "231") (name "/MCU_DIO15{slash}PWM") (class "Default")
      (node (ref "HD0") (pin "17") (pinfunction "17_17") (pintype "passive"))
      (node (ref "R84") (pin "1") (pinfunction "1_1") (pintype "passive"))
    )
    (net (code "232") (name "/NRST") (class "Default")
      (node (ref "C77") (pin "2") (pinfunction "2_2") (pintype "passive"))
      (node (ref "S1") (pin "1") (pinfunction "NO_1_1") (pintype "bidirectional"))
      (node (ref "SWD") (pin "5") (pinfunction "5_5") (pintype "passive"))
      (node (ref "U13") (pin "14") (pinfunction "NRST_14") (pintype "bidirectional"))
    )
    (net (code "233") (name "/OA1") (class "Default")
      (node (ref "C125") (pin "1") (pinfunction "1_1") (pintype "passive"))
      (node (ref "IC1") (pin "14") (pinfunction "14_14") (pintype "passive"))
      (node (ref "R88") (pin "1") (pinfunction "1_1") (pintype "passive"))
    )
    (net (code "234") (name "/OA2") (class "Default")
      (node (ref "C123") (pin "1") (pinfunction "1_1") (pintype "passive"))
      (node (ref "IC1") (pin "15") (pinfunction "15_15") (pintype "passive"))
      (node (ref "R86") (pin "1") (pinfunction "1_1") (pintype "passive"))
    )
    (net (code "235") (name "/OB1") (class "Default")
      (node (ref "C126") (pin "1") (pinfunction "1_1") (pintype "passive"))
      (node (ref "IC1") (pin "13") (pinfunction "13_13") (pintype "passive"))
      (node (ref "R89") (pin "1") (pinfunction "1_1") (pintype "passive"))
    )
    (net (code "236") (name "/OB2") (class "Default")
      (node (ref "C124") (pin "1") (pinfunction "1_1") (pintype "passive"))
      (node (ref "IC1") (pin "12") (pinfunction "12_12") (pintype "passive"))
      (node (ref "R87") (pin "1") (pinfunction "1_1") (pintype "passive"))
    )
    (net (code "237") (name "/OB3") (class "Default")
      (node (ref "C120") (pin "1") (pinfunction "1_1") (pintype "passive"))
      (node (ref "IC1") (pin "11") (pinfunction "11_11") (pintype "passive"))
      (node (ref "R85") (pin "1") (pinfunction "1_1") (pintype "passive"))
    )
    (net (code "238") (name "/OUTA") (class "Default")
      (node (ref "IC1") (pin "16") (pinfunction "16_16") (pintype "passive"))
      (node (ref "IC1") (pin "19") (pinfunction "19_19") (pintype "passive"))
      (node (ref "JP35") (pin "1") (pinfunction "1_1") (pintype "passive"))
    )
    (net (code "239") (name "/OUTB") (class "Default")
      (node (ref "IC1") (pin "10") (pinfunction "10_10") (pintype "passive"))
      (node (ref "IC1") (pin "7") (pinfunction "7_7") (pintype "passive"))
      (node (ref "JP37") (pin "1") (pinfunction "1_1") (pintype "passive"))
    )
    (net (code "240") (name "/PH0_OSC") (class "Default")
      (node (ref "C103") (pin "2") (pinfunction "2_2") (pintype "passive"))
      (node (ref "U13") (pin "12") (pinfunction "PH0-OSC_IN_12") (pintype "bidirectional"))
      (node (ref "Y1") (pin "1") (pinfunction "1_1") (pintype "passive"))
    )
    (net (code "241") (name "/PH1_OSC") (class "Default")
      (node (ref "C104") (pin "2") (pinfunction "2_2") (pintype "passive"))
      (node (ref "U13") (pin "13") (pinfunction "PH1-OSC_OUT_13") (pintype "bidirectional"))
      (node (ref "Y1") (pin "3") (pinfunction "2_3") (pintype "passive"))
    )
    (net (code "242") (name "/REF") (class "Default")
      (node (ref "C105") (pin "1") (pinfunction "1_1") (pintype "passive"))
      (node (ref "C106") (pin "1") (pinfunction "1_1") (pintype "passive"))
      (node (ref "C107") (pin "1") (pinfunction "1_1") (pintype "passive"))
      (node (ref "C108") (pin "1") (pinfunction "1_1") (pintype "passive"))
      (node (ref "C111") (pin "1") (pinfunction "1_1") (pintype "passive"))
      (node (ref "HD2") (pin "11") (pinfunction "11_11") (pintype "passive"))
      (node (ref "JP29") (pin "2") (pinfunction "2_2") (pintype "passive"))
      (node (ref "U4") (pin "1") (pinfunction "REF_1") (pintype "bidirectional"))
      (node (ref "U5") (pin "1") (pinfunction "REF_1") (pintype "bidirectional"))
      (node (ref "U6") (pin "1") (pinfunction "REF_1") (pintype "bidirectional"))
      (node (ref "U7") (pin "1") (pinfunction "REF_1") (pintype "bidirectional"))
      (node (ref "U8") (pin "1") (pinfunction "REF_1") (pintype "bidirectional"))
    )
    (net (code "243") (name "/REGREF") (class "Default")
      (node (ref "C112") (pin "2") (pinfunction "2_2") (pintype "passive"))
      (node (ref "C113") (pin "2") (pinfunction "2_2") (pintype "passive"))
      (node (ref "C127") (pin "1") (pinfunction "1_1") (pintype "passive"))
      (node (ref "C128") (pin "2") (pinfunction "2_2") (pintype "passive"))
      (node (ref "IC1") (pin "17") (pinfunction "17_17") (pintype "passive"))
      (node (ref "IC1") (pin "9") (pinfunction "9_9") (pintype "passive"))
      (node (ref "JP29") (pin "1") (pinfunction "1_1") (pintype "passive"))
      (node (ref "JP34") (pin "1") (pinfunction "1_1") (pintype "passive"))
      (node (ref "JP36") (pin "1") (pinfunction "1_1") (pintype "passive"))
      (node (ref "U18") (pin "6") (pinfunction "VOUT_6") (pintype "power_in"))
    )
    (net (code "244") (name "/SDO1") (class "Default")
      (node (ref "R90") (pin "1") (pinfunction "1_1") (pintype "passive"))
      (node (ref "U5") (pin "14") (pinfunction "SDI_14") (pintype "input"))
    )
    (net (code "245") (name "/SDO2") (class "Default")
      (node (ref "R91") (pin "1") (pinfunction "1_1") (pintype "passive"))
      (node (ref "U6") (pin "14") (pinfunction "SDI_14") (pintype "input"))
    )
    (net (code "246") (name "/SDO3") (class "Default")
      (node (ref "R96") (pin "1") (pinfunction "1_1") (pintype "passive"))
      (node (ref "U7") (pin "14") (pinfunction "SDI_14") (pintype "input"))
    )
    (net (code "247") (name "/SDO4") (class "Default")
      (node (ref "R99") (pin "1") (pinfunction "1_1") (pintype "passive"))
      (node (ref "U8") (pin "14") (pinfunction "SDI_14") (pintype "input"))
    )
    (net (code "248") (name "/SDO5") (class "Default")
      (node (ref "U8") (pin "15") (pinfunction "SDO/~{ALARM}_15") (pintype "output"))
    )
    (net (code "249") (name "/SELA0") (class "Default")
      (node (ref "IC1") (pin "2") (pinfunction "2_2") (pintype "passive"))
      (node (ref "U13") (pin "39") (pinfunction "PE9_39") (pintype "bidirectional"))
    )
    (net (code "250") (name "/SELA1") (class "Default")
      (node (ref "IC1") (pin "1") (pinfunction "1_1") (pintype "passive"))
      (node (ref "U13") (pin "40") (pinfunction "PE10_40") (pintype "bidirectional"))
    )
    (net (code "251") (name "/SELB0") (class "Default")
      (node (ref "IC1") (pin "4") (pinfunction "4_4") (pintype "passive"))
      (node (ref "U13") (pin "38") (pinfunction "PE8_38") (pintype "bidirectional"))
    )
    (net (code "252") (name "/SELB1") (class "Default")
      (node (ref "IC1") (pin "5") (pinfunction "5_5") (pintype "passive"))
      (node (ref "U13") (pin "37") (pinfunction "PE7_37") (pintype "bidirectional"))
    )
    (net (code "253") (name "/SPI2_MISO") (class "Default")
      (node (ref "JP30") (pin "1") (pinfunction "1_1") (pintype "passive"))
      (node (ref "R27") (pin "1") (pinfunction "1_1") (pintype "passive"))
      (node (ref "U13") (pin "53") (pinfunction "PB14_53") (pintype "bidirectional"))
      (node (ref "U14") (pin "21") (pinfunction "DOUT_21") (pintype "output"))
    )
    (net (code "254") (name "/SPI2_MOSI") (class "Default")
      (node (ref "U13") (pin "54") (pinfunction "PB15_54") (pintype "bidirectional"))
      (node (ref "U14") (pin "20") (pinfunction "DIN_20") (pintype "input"))
      (node (ref "U15") (pin "20") (pinfunction "DIN_20") (pintype "input"))
    )
    (net (code "255") (name "/SPI2_NSS") (class "Default")
      (node (ref "U13") (pin "51") (pinfunction "PB12_51") (pintype "bidirectional"))
    )
    (net (code "256") (name "/SPI2_SCK") (class "Default")
      (node (ref "U13") (pin "52") (pinfunction "PB13_52") (pintype "bidirectional"))
      (node (ref "U14") (pin "22") (pinfunction "SCLK_22") (pintype "bidirectional"))
      (node (ref "U15") (pin "22") (pinfunction "SCLK_22") (pintype "bidirectional"))
    )
    (net (code "257") (name "/SWCLK") (class "Default")
      (node (ref "SWD") (pin "3") (pinfunction "3_3") (pintype "passive"))
      (node (ref "U13") (pin "76") (pinfunction "PA14_76") (pintype "bidirectional"))
    )
    (net (code "258") (name "/SWDIO") (class "Default")
      (node (ref "SWD") (pin "2") (pinfunction "2_2") (pintype "passive"))
      (node (ref "U13") (pin "72") (pinfunction "PA13_72") (pintype "bidirectional"))
    )
    (net (code "259") (name "/SWO") (class "Default")
      (node (ref "SWD") (pin "4") (pinfunction "4_4") (pintype "passive"))
      (node (ref "U13") (pin "89") (pinfunction "PB3_89") (pintype "bidirectional"))
    )
    (net (code "260") (name "/USB_5V") (class "Default")
      (node (ref "C129") (pin "2") (pinfunction "2_2") (pintype "passive"))
      (node (ref "CR1") (pin "5") (pinfunction "5_5") (pintype "passive"))
      (node (ref "HD0") (pin "1") (pinfunction "1_1") (pintype "passive"))
      (node (ref "J1") (pin "A4_B9") (pinfunction "VBUS_A4_B9") (pintype "power_in"))
      (node (ref "J1") (pin "B4_A9") (pinfunction "VBUS_B4_A9") (pintype "power_in"))
      (node (ref "LED5") (pin "2") (pinfunction "2_2") (pintype "passive"))
    )
    (net (code "261") (name "/USB_DM_CONN") (class "Default")
      (node (ref "CR1") (pin "6") (pinfunction "6_6") (pintype "passive"))
      (node (ref "J1") (pin "A7") (pinfunction "D-_A_A7") (pintype "bidirectional"))
      (node (ref "J1") (pin "B7") (pinfunction "D-_B_B7") (pintype "bidirectional"))
    )
    (net (code "262") (name "/USB_DM_MCU") (class "Default")
      (node (ref "R97") (pin "1") (pinfunction "1_1") (pintype "passive"))
      (node (ref "U13") (pin "70") (pinfunction "PA11_70") (pintype "bidirectional"))
    )
    (net (code "263") (name "/USB_DP_CONN") (class "Default")
      (node (ref "CR1") (pin "4") (pinfunction "4_4") (pintype "passive"))
      (node (ref "J1") (pin "A6") (pinfunction "D+_A_A6") (pintype "bidirectional"))
      (node (ref "J1") (pin "B6") (pinfunction "D+_B_B6") (pintype "bidirectional"))
    )
    (net (code "264") (name "/USB_DP_MCU") (class "Default")
      (node (ref "R98") (pin "1") (pinfunction "1_1") (pintype "passive"))
      (node (ref "U13") (pin "71") (pinfunction "PA12_71") (pintype "bidirectional"))
    )
    (net (code "265") (name "/VU") (class "Default")
      (node (ref "C1") (pin "1") (pinfunction "1_1") (pintype "passive"))
      (node (ref "C4") (pin "1") (pinfunction "1_1") (pintype "passive"))
      (node (ref "JP0") (pin "2") (pinfunction "2_2") (pintype "passive"))
      (node (ref "U1") (pin "3") (pinfunction "IN_3") (pintype "power_in"))
      (node (ref "U2") (pin "3") (pinfunction "IN_3") (pintype "power_in"))
    )
    (net (code "266") (name "AGND") (class "Default")
      (node (ref "B0") (pin "12") (pinfunction "12_12") (pintype "passive"))
      (node (ref "B0") (pin "13") (pinfunction "13_13") (pintype "passive"))
      (node (ref "B0") (pin "18") (pinfunction "18_18") (pintype "passive"))
      (node (ref "B0") (pin "35") (pinfunction "35_35") (pintype "passive"))
      (node (ref "B0") (pin "36") (pinfunction "36_36") (pintype "passive"))
      (node (ref "B0") (pin "4") (pinfunction "4_4") (pintype "passive"))
      (node (ref "B0") (pin "44") (pinfunction "44_44") (pintype "passive"))
      (node (ref "B0") (pin "50") (pinfunction "50_50") (pintype "passive"))
      (node (ref "B0") (pin "53") (pinfunction "53_53") (pintype "passive"))
      (node (ref "B0") (pin "7") (pinfunction "7_7") (pintype "passive"))
      (node (ref "B0") (pin "9") (pinfunction "9_9") (pintype "passive"))
      (node (ref "C0") (pin "2") (pinfunction "2_2") (pintype "passive"))
      (node (ref "C1") (pin "2") (pinfunction "2_2") (pintype "passive"))
      (node (ref "C10") (pin "1") (pinfunction "1_1") (pintype "passive"))
      (node (ref "C100") (pin "1") (pinfunction "1_1") (pintype "passive"))
      (node (ref "C101") (pin "1") (pinfunction "1_1") (pintype "passive"))
      (node (ref "C102") (pin "1") (pinfunction "1_1") (pintype "passive"))
      (node (ref "C103") (pin "1") (pinfunction "1_1") (pintype "passive"))
      (node (ref "C104") (pin "1") (pinfunction "1_1") (pintype "passive"))
      (node (ref "C105") (pin "2") (pinfunction "2_2") (pintype "passive"))
      (node (ref "C106") (pin "2") (pinfunction "2_2") (pintype "passive"))
      (node (ref "C107") (pin "2") (pinfunction "2_2") (pintype "passive"))
      (node (ref "C108") (pin "2") (pinfunction "2_2") (pintype "passive"))
      (node (ref "C109") (pin "1") (pinfunction "1_1") (pintype "passive"))
      (node (ref "C11") (pin "2") (pinfunction "2_2") (pintype "passive"))
      (node (ref "C110") (pin "1") (pinfunction "1_1") (pintype "passive"))
      (node (ref "C111") (pin "2") (pinfunction "2_2") (pintype "passive"))
      (node (ref "C112") (pin "1") (pinfunction "1_1") (pintype "passive"))
      (node (ref "C113") (pin "1") (pinfunction "1_1") (pintype "passive"))
      (node (ref "C114") (pin "2") (pinfunction "2_2") (pintype "passive"))
      (node (ref "C115") (pin "2") (pinfunction "2_2") (pintype "passive"))
      (node (ref "C116") (pin "2") (pinfunction "2_2") (pintype "passive"))
      (node (ref "C117") (pin "1") (pinfunction "1_1") (pintype "passive"))
      (node (ref "C118") (pin "1") (pinfunction "1_1") (pintype "passive"))
      (node (ref "C119") (pin "1") (pinfunction "1_1") (pintype "passive"))
      (node (ref "C12") (pin "2") (pinfunction "2_2") (pintype "passive"))
      (node (ref "C121") (pin "2") (pinfunction "2_2") (pintype "passive"))
      (node (ref "C122") (pin "2") (pinfunction "2_2") (pintype "passive"))
      (node (ref "C127") (pin "2") (pinfunction "2_2") (pintype "passive"))
      (node (ref "C128") (pin "1") (pinfunction "1_1") (pintype "passive"))
      (node (ref "C129") (pin "1") (pinfunction "1_1") (pintype "passive"))
      (node (ref "C13") (pin "2") (pinfunction "2_2") (pintype "passive"))
      (node (ref "C14") (pin "2") (pinfunction "2_2") (pintype "passive"))
      (node (ref "C15") (pin "1") (pinfunction "1_1") (pintype "passive"))
      (node (ref "C16") (pin "1") (pinfunction "1_1") (pintype "passive"))
      (node (ref "C17") (pin "2") (pinfunction "2_2") (pintype "passive"))
      (node (ref "C18") (pin "2") (pinfunction "2_2") (pintype "passive"))
      (node (ref "C19") (pin "2") (pinfunction "2_2") (pintype "passive"))
      (node (ref "C2") (pin "2") (pinfunction "2_2") (pintype "passive"))
      (node (ref "C20") (pin "1") (pinfunction "1_1") (pintype "passive"))
      (node (ref "C21") (pin "1") (pinfunction "1_1") (pintype "passive"))
      (node (ref "C22") (pin "2") (pinfunction "2_2") (pintype "passive"))
      (node (ref "C23") (pin "2") (pinfunction "2_2") (pintype "passive"))
      (node (ref "C24") (pin "1") (pinfunction "1_1") (pintype "passive"))
      (node (ref "C25") (pin "1") (pinfunction "1_1") (pintype "passive"))
      (node (ref "C26") (pin "2") (pinfunction "2_2") (pintype "passive"))
      (node (ref "C27") (pin "2") (pinfunction "2_2") (pintype "passive"))
      (node (ref "C28") (pin "1") (pinfunction "1_1") (pintype "passive"))
      (node (ref "C29") (pin "1") (pinfunction "1_1") (pintype "passive"))
      (node (ref "C3") (pin "2") (pinfunction "2_2") (pintype "passive"))
      (node (ref "C30") (pin "2") (pinfunction "2_2") (pintype "passive"))
      (node (ref "C31") (pin "2") (pinfunction "2_2") (pintype "passive"))
      (node (ref "C32") (pin "1") (pinfunction "1_1") (pintype "passive"))
      (node (ref "C33") (pin "1") (pinfunction "1_1") (pintype "passive"))
      (node (ref "C34") (pin "2") (pinfunction "2_2") (pintype "passive"))
      (node (ref "C35") (pin "2") (pinfunction "2_2") (pintype "passive"))
      (node (ref "C36") (pin "1") (pinfunction "1_1") (pintype "passive"))
      (node (ref "C37") (pin "1") (pinfunction "1_1") (pintype "passive"))
      (node (ref "C38") (pin "2") (pinfunction "2_2") (pintype "passive"))
      (node (ref "C39") (pin "2") (pinfunction "2_2") (pintype "passive"))
      (node (ref "C4") (pin "2") (pinfunction "2_2") (pintype "passive"))
      (node (ref "C40") (pin "1") (pinfunction "1_1") (pintype "passive"))
      (node (ref "C41") (pin "1") (pinfunction "1_1") (pintype "passive"))
      (node (ref "C42") (pin "1") (pinfunction "1_1") (pintype "passive"))
      (node (ref "C43") (pin "1") (pinfunction "1_1") (pintype "passive"))
      (node (ref "C44") (pin "2") (pinfunction "2_2") (pintype "passive"))
      (node (ref "C45") (pin "2") (pinfunction "2_2") (pintype "passive"))
      (node (ref "C46") (pin "1") (pinfunction "1_1") (pintype "passive"))
      (node (ref "C47") (pin "1") (pinfunction "1_1") (pintype "passive"))
      (node (ref "C48") (pin "2") (pinfunction "2_2") (pintype "passive"))
      (node (ref "C49") (pin "2") (pinfunction "2_2") (pintype "passive"))
      (node (ref "C5") (pin "2") (pinfunction "2_2") (pintype "passive"))
      (node (ref "C50") (pin "1") (pinfunction "1_1") (pintype "passive"))
      (node (ref "C51") (pin "1") (pinfunction "1_1") (pintype "passive"))
      (node (ref "C52") (pin "1") (pinfunction "1_1") (pintype "passive"))
      (node (ref "C53") (pin "1") (pinfunction "1_1") (pintype "passive"))
      (node (ref "C54") (pin "1") (pinfunction "1_1") (pintype "passive"))
      (node (ref "C55") (pin "2") (pinfunction "2_2") (pintype "passive"))
      (node (ref "C56") (pin "2") (pinfunction "2_2") (pintype "passive"))
      (node (ref "C57") (pin "2") (pinfunction "2_2") (pintype "passive"))
      (node (ref "C6") (pin "2") (pinfunction "2_2") (pintype "passive"))
      (node (ref "C60") (pin "2") (pinfunction "2_2") (pintype "passive"))
      (node (ref "C61") (pin "1") (pinfunction "1_1") (pintype "passive"))
      (node (ref "C62") (pin "1") (pinfunction "1_1") (pintype "passive"))
      (node (ref "C63") (pin "1") (pinfunction "1_1") (pintype "passive"))
      (node (ref "C64") (pin "1") (pinfunction "1_1") (pintype "passive"))
      (node (ref "C65") (pin "1") (pinfunction "1_1") (pintype "passive"))
      (node (ref "C66") (pin "1") (pinfunction "1_1") (pintype "passive"))
      (node (ref "C67") (pin "1") (pinfunction "1_1") (pintype "passive"))
      (node (ref "C68") (pin "1") (pinfunction "1_1") (pintype "passive"))
      (node (ref "C69") (pin "1") (pinfunction "1_1") (pintype "passive"))
      (node (ref "C7") (pin "2") (pinfunction "2_2") (pintype "passive"))
      (node (ref "C70") (pin "1") (pinfunction "1_1") (pintype "passive"))
      (node (ref "C71") (pin "1") (pinfunction "1_1") (pintype "passive"))
      (node (ref "C72") (pin "1") (pinfunction "1_1") (pintype "passive"))
      (node (ref "C75") (pin "2") (pinfunction "2_2") (pintype "passive"))
      (node (ref "C76") (pin "2") (pinfunction "2_2") (pintype "passive"))
      (node (ref "C77") (pin "1") (pinfunction "1_1") (pintype "passive"))
      (node (ref "C78") (pin "2") (pinfunction "2_2") (pintype "passive"))
      (node (ref "C79") (pin "2") (pinfunction "2_2") (pintype "passive"))
      (node (ref "C8") (pin "2") (pinfunction "2_2") (pintype "passive"))
      (node (ref "C81") (pin "1") (pinfunction "1_1") (pintype "passive"))
      (node (ref "C82") (pin "1") (pinfunction "1_1") (pintype "passive"))
      (node (ref "C83") (pin "1") (pinfunction "1_1") (pintype "passive"))
      (node (ref "C84") (pin "1") (pinfunction "1_1") (pintype "passive"))
      (node (ref "C85") (pin "1") (pinfunction "1_1") (pintype "passive"))
      (node (ref "C86") (pin "1") (pinfunction "1_1") (pintype "passive"))
      (node (ref "C87") (pin "1") (pinfunction "1_1") (pintype "passive"))
      (node (ref "C88") (pin "1") (pinfunction "1_1") (pintype "passive"))
      (node (ref "C9") (pin "2") (pinfunction "2_2") (pintype "passive"))
      (node (ref "C92") (pin "2") (pinfunction "2_2") (pintype "passive"))
      (node (ref "C93") (pin "1") (pinfunction "1_1") (pintype "passive"))
      (node (ref "C94") (pin "2") (pinfunction "2_2") (pintype "passive"))
      (node (ref "C95") (pin "2") (pinfunction "2_2") (pintype "passive"))
      (node (ref "C96") (pin "1") (pinfunction "1_1") (pintype "passive"))
      (node (ref "C97") (pin "1") (pinfunction "1_1") (pintype "passive"))
      (node (ref "C98") (pin "1") (pinfunction "1_1") (pintype "passive"))
      (node (ref "C99") (pin "1") (pinfunction "1_1") (pintype "passive"))
      (node (ref "CR1") (pin "2") (pinfunction "2_2") (pintype "passive"))
      (node (ref "HD0") (pin "24") (pinfunction "24_24") (pintype "passive"))
      (node (ref "HD0") (pin "26") (pinfunction "26_26") (pintype "passive"))
      (node (ref "HD0") (pin "28") (pinfunction "28_28") (pintype "passive"))
      (node (ref "HD0") (pin "5") (pinfunction "5_5") (pintype "passive"))
      (node (ref "HD1") (pin "23") (pinfunction "23_23") (pintype "passive"))
      (node (ref "HD1") (pin "24") (pinfunction "24_24") (pintype "passive"))
      (node (ref "HD1") (pin "5") (pinfunction "5_5") (pintype "passive"))
      (node (ref "HD1") (pin "6") (pinfunction "6_6") (pintype "passive"))
      (node (ref "HD2") (pin "14") (pinfunction "14_14") (pintype "passive"))
      (node (ref "HD2") (pin "16") (pinfunction "16_16") (pintype "passive"))
      (node (ref "HD2") (pin "29") (pinfunction "29_29") (pintype "passive"))
      (node (ref "HD2") (pin "31") (pinfunction "31_31") (pintype "passive"))
      (node (ref "HD2") (pin "4") (pinfunction "4_4") (pintype "passive"))
      (node (ref "IC1") (pin "21") (pinfunction "21_21") (pintype "passive"))
      (node (ref "IC1") (pin "3") (pinfunction "3_3") (pintype "passive"))
      (node (ref "IC1") (pin "6") (pinfunction "6_6") (pintype "passive"))
      (node (ref "J1") (pin "A1_B12") (pinfunction "GND_A1_B12") (pintype "power_in"))
      (node (ref "J1") (pin "B1_A12") (pinfunction "GND_B1_A12") (pintype "power_in"))
      (node (ref "JGND") (pin "1") (pinfunction "1_1") (pintype "passive"))
      (node (ref "JGND") (pin "2") (pinfunction "2_2") (pintype "passive"))
      (node (ref "JGND") (pin "3") (pinfunction "3_3") (pintype "passive"))
      (node (ref "JGND") (pin "4") (pinfunction "4_4") (pintype "passive"))
      (node (ref "JGND") (pin "5") (pinfunction "5_5") (pintype "passive"))
      (node (ref "JGND") (pin "6") (pinfunction "6_6") (pintype "passive"))
      (node (ref "JGND2") (pin "1") (pinfunction "1_1") (pintype "passive"))
      (node (ref "JGND2") (pin "2") (pinfunction "2_2") (pintype "passive"))
      (node (ref "JGND2") (pin "3") (pinfunction "3_3") (pintype "passive"))
      (node (ref "L4") (pin "1") (pinfunction "1_1") (pintype "passive"))
      (node (ref "L5") (pin "1") (pinfunction "1_1") (pintype "passive"))
      (node (ref "L6") (pin "2") (pinfunction "2_2") (pintype "passive"))
      (node (ref "Q1") (pin "2") (pinfunction "S_2") (pintype "passive"))
      (node (ref "R10") (pin "1") (pinfunction "1_1") (pintype "passive"))
      (node (ref "R100") (pin "2") (pinfunction "2_2") (pintype "passive"))
      (node (ref "R101") (pin "2") (pinfunction "2_2") (pintype "passive"))
      (node (ref "R102") (pin "1") (pinfunction "1_1") (pintype "passive"))
      (node (ref "R103") (pin "1") (pinfunction "1_1") (pintype "passive"))
      (node (ref "R104") (pin "1") (pinfunction "1_1") (pintype "passive"))
      (node (ref "R2") (pin "3") (pinfunction "BOT_3") (pintype "passive"))
      (node (ref "R4") (pin "3") (pinfunction "BOT_3") (pintype "passive"))
      (node (ref "R45") (pin "2") (pinfunction "2_2") (pintype "passive"))
      (node (ref "R5") (pin "1") (pinfunction "1_1") (pintype "passive"))
      (node (ref "R6") (pin "1") (pinfunction "1_1") (pintype "passive"))
      (node (ref "R62") (pin "1") (pinfunction "1_1") (pintype "passive"))
      (node (ref "R63") (pin "1") (pinfunction "1_1") (pintype "passive"))
      (node (ref "R64") (pin "2") (pinfunction "2_2") (pintype "passive"))
      (node (ref "R65") (pin "1") (pinfunction "1_1") (pintype "passive"))
      (node (ref "R7") (pin "2") (pinfunction "2_2") (pintype "passive"))
      (node (ref "R8") (pin "1") (pinfunction "1_1") (pintype "passive"))
      (node (ref "R80") (pin "2") (pinfunction "2_2") (pintype "passive"))
      (node (ref "R92") (pin "2") (pinfunction "2_2") (pintype "passive"))
      (node (ref "R93") (pin "2") (pinfunction "2_2") (pintype "passive"))
      (node (ref "R94") (pin "2") (pinfunction "2_2") (pintype "passive"))
      (node (ref "R95") (pin "2") (pinfunction "2_2") (pintype "passive"))
      (node (ref "S1") (pin "4") (pinfunction "COM_2_4") (pintype "bidirectional"))
      (node (ref "SWD") (pin "6") (pinfunction "6_6") (pintype "passive"))
      (node (ref "U10") (pin "11") (pinfunction "V-_11") (pintype "power_in"))
      (node (ref "U11") (pin "11") (pinfunction "GND_11") (pintype "power_in"))
      (node (ref "U11") (pin "12") (pinfunction "GND_12") (pintype "power_in"))
      (node (ref "U11") (pin "13") (pinfunction "GND_13") (pintype "power_in"))
      (node (ref "U12") (pin "2") (pinfunction "GND_2") (pintype "power_in"))
      (node (ref "U13") (pin "10") (pinfunction "VSS_10") (pintype "power_in"))
      (node (ref "U13") (pin "19") (pinfunction "VSSA_19") (pintype "power_in"))
      (node (ref "U13") (pin "26") (pinfunction "VSS_26") (pintype "power_in"))
      (node (ref "U13") (pin "49") (pinfunction "VSS_49") (pintype "power_in"))
      (node (ref "U13") (pin "74") (pinfunction "VSS_74") (pintype "power_in"))
      (node (ref "U13") (pin "99") (pinfunction "VSS_99") (pintype "power_in"))
      (node (ref "U14") (pin "10") (pinfunction "AVSS_10") (pintype "power_in"))
      (node (ref "U14") (pin "11") (pinfunction "VNCP_11") (pintype "power_in"))
      (node (ref "U14") (pin "13") (pinfunction "VREFN_13") (pintype "input"))
      (node (ref "U14") (pin "27") (pinfunction "GND_27") (pintype "power_in"))
      (node (ref "U14") (pin "31") (pinfunction "M1_31") (pintype "passive"))
      (node (ref "U14") (pin "32") (pinfunction "M2_32") (pintype "passive"))
      (node (ref "U15") (pin "10") (pinfunction "AVSS_10") (pintype "power_in"))
      (node (ref "U15") (pin "11") (pinfunction "VNCP_11") (pintype "power_in"))
      (node (ref "U15") (pin "13") (pinfunction "VREFN_13") (pintype "input"))
      (node (ref "U15") (pin "27") (pinfunction "GND_27") (pintype "power_in"))
      (node (ref "U15") (pin "31") (pinfunction "M1_31") (pintype "passive"))
      (node (ref "U15") (pin "32") (pinfunction "M2_32") (pintype "passive"))
      (node (ref "U16") (pin "11") (pinfunction "V-_11") (pintype "power_in"))
      (node (ref "U17") (pin "11") (pinfunction "V-_11") (pintype "power_in"))
      (node (ref "U18") (pin "4") (pinfunction "GND_4") (pintype "power_in"))
      (node (ref "U19") (pin "11") (pinfunction "GND_11") (pintype "power_in"))
      (node (ref "U19") (pin "12") (pinfunction "GND_12") (pintype "power_in"))
      (node (ref "U19") (pin "13") (pinfunction "GND_13") (pintype "power_in"))
      (node (ref "U3") (pin "11") (pinfunction "V-_11") (pintype "power_in"))
      (node (ref "U4") (pin "17") (pinfunction "EXP_17") (pintype "power_in"))
      (node (ref "U4") (pin "6") (pinfunction "GND_6") (pintype "power_in"))
      (node (ref "U5") (pin "17") (pinfunction "EXP_17") (pintype "power_in"))
      (node (ref "U5") (pin "6") (pinfunction "GND_6") (pintype "power_in"))
      (node (ref "U6") (pin "17") (pinfunction "EXP_17") (pintype "power_in"))
      (node (ref "U6") (pin "6") (pinfunction "GND_6") (pintype "power_in"))
      (node (ref "U7") (pin "17") (pinfunction "EXP_17") (pintype "power_in"))
      (node (ref "U7") (pin "6") (pinfunction "GND_6") (pintype "power_in"))
      (node (ref "U8") (pin "17") (pinfunction "EXP_17") (pintype "power_in"))
      (node (ref "U8") (pin "6") (pinfunction "GND_6") (pintype "power_in"))
      (node (ref "U9") (pin "11") (pinfunction "V-_11") (pintype "power_in"))
      (node (ref "Y1") (pin "2") (pinfunction "GND_2") (pintype "power_in"))
      (node (ref "Y1") (pin "4") (pinfunction "GND_4") (pintype "power_in"))
    )
    (net (code "267") (name "AVDD") (class "Default")
      (node (ref "C114") (pin "1") (pinfunction "1_1") (pintype "passive"))
      (node (ref "C115") (pin "1") (pinfunction "1_1") (pintype "passive"))
      (node (ref "C116") (pin "1") (pinfunction "1_1") (pintype "passive"))
      (node (ref "C121") (pin "1") (pinfunction "1_1") (pintype "passive"))
      (node (ref "C122") (pin "1") (pinfunction "1_1") (pintype "passive"))
      (node (ref "C15") (pin "2") (pinfunction "2_2") (pintype "passive"))
      (node (ref "C16") (pin "2") (pinfunction "2_2") (pintype "passive"))
      (node (ref "C17") (pin "1") (pinfunction "1_1") (pintype "passive"))
      (node (ref "C18") (pin "1") (pinfunction "1_1") (pintype "passive"))
      (node (ref "C20") (pin "2") (pinfunction "2_2") (pintype "passive"))
      (node (ref "C21") (pin "2") (pinfunction "2_2") (pintype "passive"))
      (node (ref "C26") (pin "1") (pinfunction "1_1") (pintype "passive"))
      (node (ref "C27") (pin "1") (pinfunction "1_1") (pintype "passive"))
      (node (ref "C30") (pin "1") (pinfunction "1_1") (pintype "passive"))
      (node (ref "C31") (pin "1") (pinfunction "1_1") (pintype "passive"))
      (node (ref "C34") (pin "1") (pinfunction "1_1") (pintype "passive"))
      (node (ref "C35") (pin "1") (pinfunction "1_1") (pintype "passive"))
      (node (ref "C38") (pin "1") (pinfunction "1_1") (pintype "passive"))
      (node (ref "C39") (pin "1") (pinfunction "1_1") (pintype "passive"))
      (node (ref "C44") (pin "1") (pinfunction "1_1") (pintype "passive"))
      (node (ref "C45") (pin "1") (pinfunction "1_1") (pintype "passive"))
      (node (ref "C48") (pin "1") (pinfunction "1_1") (pintype "passive"))
      (node (ref "C49") (pin "1") (pinfunction "1_1") (pintype "passive"))
      (node (ref "C55") (pin "1") (pinfunction "1_1") (pintype "passive"))
      (node (ref "C56") (pin "1") (pinfunction "1_1") (pintype "passive"))
      (node (ref "C75") (pin "1") (pinfunction "1_1") (pintype "passive"))
      (node (ref "C76") (pin "1") (pinfunction "1_1") (pintype "passive"))
      (node (ref "C78") (pin "1") (pinfunction "1_1") (pintype "passive"))
      (node (ref "C79") (pin "1") (pinfunction "1_1") (pintype "passive"))
      (node (ref "HD2") (pin "7") (pinfunction "7_7") (pintype "passive"))
      (node (ref "IC1") (pin "20") (pinfunction "20_20") (pintype "passive"))
      (node (ref "L3") (pin "1") (pinfunction "1_1") (pintype "passive"))
      (node (ref "U10") (pin "4") (pinfunction "V+_4") (pintype "power_in"))
      (node (ref "U14") (pin "9") (pinfunction "AVDD_9") (pintype "power_in"))
      (node (ref "U15") (pin "9") (pinfunction "AVDD_9") (pintype "power_in"))
      (node (ref "U16") (pin "4") (pinfunction "V+_4") (pintype "power_in"))
      (node (ref "U17") (pin "4") (pinfunction "V+_4") (pintype "power_in"))
      (node (ref "U3") (pin "4") (pinfunction "V+_4") (pintype "power_in"))
      (node (ref "U4") (pin "7") (pinfunction "VDD_7") (pintype "power_in"))
      (node (ref "U5") (pin "7") (pinfunction "VDD_7") (pintype "power_in"))
      (node (ref "U6") (pin "7") (pinfunction "VDD_7") (pintype "power_in"))
      (node (ref "U7") (pin "7") (pinfunction "VDD_7") (pintype "power_in"))
      (node (ref "U8") (pin "7") (pinfunction "VDD_7") (pintype "power_in"))
      (node (ref "U9") (pin "4") (pinfunction "V+_4") (pintype "power_in"))
    )
    (net (code "268") (name "AVDD3") (class "Default")
      (node (ref "C101") (pin "2") (pinfunction "2_2") (pintype "passive"))
      (node (ref "C102") (pin "2") (pinfunction "2_2") (pintype "passive"))
      (node (ref "C109") (pin "2") (pinfunction "2_2") (pintype "passive"))
      (node (ref "C110") (pin "2") (pinfunction "2_2") (pintype "passive"))
      (node (ref "C19") (pin "1") (pinfunction "1_1") (pintype "passive"))
      (node (ref "C57") (pin "1") (pinfunction "1_1") (pintype "passive"))
      (node (ref "C60") (pin "1") (pinfunction "1_1") (pintype "passive"))
      (node (ref "C92") (pin "1") (pinfunction "1_1") (pintype "passive"))
      (node (ref "HD2") (pin "9") (pinfunction "9_9") (pintype "passive"))
      (node (ref "L2") (pin "1") (pinfunction "1_1") (pintype "passive"))
      (node (ref "U13") (pin "20") (pinfunction "VREF+_20") (pintype "power_in"))
      (node (ref "U13") (pin "21") (pinfunction "VDDA_21") (pintype "power_in"))
      (node (ref "U13") (pin "6") (pinfunction "VBAT_6") (pintype "power_in"))
      (node (ref "U18") (pin "2") (pinfunction "VIN_2") (pintype "power_in"))
    )
    (net (code "269") (name "DVDD") (class "Default")
      (node (ref "C11") (pin "1") (pinfunction "1_1") (pintype "passive"))
      (node (ref "C12") (pin "1") (pinfunction "1_1") (pintype "passive"))
      (node (ref "C13") (pin "1") (pinfunction "1_1") (pintype "passive"))
      (node (ref "C14") (pin "1") (pinfunction "1_1") (pintype "passive"))
      (node (ref "C24") (pin "2") (pinfunction "2_2") (pintype "passive"))
      (node (ref "C25") (pin "2") (pinfunction "2_2") (pintype "passive"))
      (node (ref "C28") (pin "2") (pinfunction "2_2") (pintype "passive"))
      (node (ref "C29") (pin "2") (pinfunction "2_2") (pintype "passive"))
      (node (ref "C36") (pin "2") (pinfunction "2_2") (pintype "passive"))
      (node (ref "C37") (pin "2") (pinfunction "2_2") (pintype "passive"))
      (node (ref "C40") (pin "2") (pinfunction "2_2") (pintype "passive"))
      (node (ref "C41") (pin "2") (pinfunction "2_2") (pintype "passive"))
      (node (ref "C46") (pin "2") (pinfunction "2_2") (pintype "passive"))
      (node (ref "C47") (pin "2") (pinfunction "2_2") (pintype "passive"))
      (node (ref "HD0") (pin "3") (pinfunction "3_3") (pintype "passive"))
      (node (ref "JP_DVDD") (pin "2") (pinfunction "2_2") (pintype "passive"))
      (node (ref "U4") (pin "16") (pinfunction "VIO_16") (pintype "power_in"))
      (node (ref "U5") (pin "16") (pinfunction "VIO_16") (pintype "power_in"))
      (node (ref "U6") (pin "16") (pinfunction "VIO_16") (pintype "power_in"))
      (node (ref "U7") (pin "16") (pinfunction "VIO_16") (pintype "power_in"))
      (node (ref "U8") (pin "16") (pinfunction "VIO_16") (pintype "power_in"))
    )
    (net (code "270") (name "DVDD_3V") (class "Default")
      (node (ref "C10") (pin "2") (pinfunction "2_2") (pintype "passive"))
      (node (ref "C100") (pin "2") (pinfunction "2_2") (pintype "passive"))
      (node (ref "C117") (pin "2") (pinfunction "2_2") (pintype "passive"))
      (node (ref "C118") (pin "2") (pinfunction "2_2") (pintype "passive"))
      (node (ref "C32") (pin "2") (pinfunction "2_2") (pintype "passive"))
      (node (ref "C33") (pin "2") (pinfunction "2_2") (pintype "passive"))
      (node (ref "C42") (pin "2") (pinfunction "2_2") (pintype "passive"))
      (node (ref "C43") (pin "2") (pinfunction "2_2") (pintype "passive"))
      (node (ref "C53") (pin "2") (pinfunction "2_2") (pintype "passive"))
      (node (ref "C9") (pin "1") (pinfunction "1_1") (pintype "passive"))
      (node (ref "C93") (pin "2") (pinfunction "2_2") (pintype "passive"))
      (node (ref "C96") (pin "2") (pinfunction "2_2") (pintype "passive"))
      (node (ref "C97") (pin "2") (pinfunction "2_2") (pintype "passive"))
      (node (ref "C98") (pin "2") (pinfunction "2_2") (pintype "passive"))
      (node (ref "C99") (pin "2") (pinfunction "2_2") (pintype "passive"))
      (node (ref "HD0") (pin "4") (pinfunction "4_4") (pintype "passive"))
      (node (ref "JP19") (pin "1") (pinfunction "1_1") (pintype "passive"))
      (node (ref "JP2") (pin "2") (pinfunction "2_2") (pintype "passive"))
      (node (ref "JP28") (pin "2") (pinfunction "2_2") (pintype "passive"))
      (node (ref "JP32") (pin "1") (pinfunction "1_1") (pintype "passive"))
      (node (ref "JP_DVDD") (pin "3") (pinfunction "3_3") (pintype "passive"))
      (node (ref "JP_VLT") (pin "1") (pinfunction "1_1") (pintype "passive"))
      (node (ref "LED3") (pin "2") (pinfunction "2_2") (pintype "passive"))
      (node (ref "LED4") (pin "2") (pinfunction "2_2") (pintype "passive"))
      (node (ref "LED8") (pin "2") (pinfunction "2_2") (pintype "passive"))
      (node (ref "LED9") (pin "2") (pinfunction "2_2") (pintype "passive"))
      (node (ref "R27") (pin "2") (pinfunction "2_2") (pintype "passive"))
      (node (ref "R28") (pin "2") (pinfunction "2_2") (pintype "passive"))
      (node (ref "SWD") (pin "1") (pinfunction "1_1") (pintype "passive"))
      (node (ref "U12") (pin "1") (pinfunction "IN_1") (pintype "input"))
      (node (ref "U12") (pin "3") (pinfunction "EN_3") (pintype "input"))
      (node (ref "U13") (pin "100") (pinfunction "VDD_100") (pintype "power_in"))
      (node (ref "U13") (pin "11") (pinfunction "VDD_11") (pintype "power_in"))
      (node (ref "U13") (pin "27") (pinfunction "VDD_27") (pintype "power_in"))
      (node (ref "U13") (pin "50") (pinfunction "VDD_50") (pintype "power_in"))
      (node (ref "U13") (pin "75") (pinfunction "VDD_75") (pintype "power_in"))
      (node (ref "U14") (pin "15") (pinfunction "IOVDD_15") (pintype "power_in"))
      (node (ref "U14") (pin "16") (pinfunction "RESV_16") (pintype "passive"))
      (node (ref "U14") (pin "29") (pinfunction "IOVDD_29") (pintype "power_in"))
      (node (ref "U14") (pin "30") (pinfunction "M0_30") (pintype "passive"))
      (node (ref "U15") (pin "15") (pinfunction "IOVDD_15") (pintype "power_in"))
      (node (ref "U15") (pin "16") (pinfunction "RESV_16") (pintype "passive"))
      (node (ref "U15") (pin "29") (pinfunction "IOVDD_29") (pintype "power_in"))
      (node (ref "U15") (pin "30") (pinfunction "M0_30") (pintype "passive"))
      (node (ref "U19") (pin "23") (pinfunction "VCCB_23") (pintype "power_in"))
      (node (ref "U19") (pin "24") (pinfunction "VCCB_24") (pintype "power_in"))
    )
    (net (code "271") (name "DVDD_5V") (class "Default")
      (node (ref "C7") (pin "1") (pinfunction "1_1") (pintype "passive"))
      (node (ref "C8") (pin "1") (pinfunction "1_1") (pintype "passive"))
      (node (ref "JP1") (pin "2") (pinfunction "2_2") (pintype "passive"))
      (node (ref "JP31") (pin "1") (pinfunction "1_1") (pintype "passive"))
      (node (ref "JP_VLT1") (pin "1") (pinfunction "1_1") (pintype "passive"))
      (node (ref "LED2") (pin "2") (pinfunction "2_2") (pintype "passive"))
      (node (ref "LED7") (pin "2") (pinfunction "2_2") (pintype "passive"))
    )
    (net (code "272") (name "Net-(C0-Pad1)") (class "Default")
      (node (ref "C0") (pin "1") (pinfunction "1_1") (pintype "passive"))
      (node (ref "JP0") (pin "1") (pinfunction "1_1") (pintype "passive"))
      (node (ref "JPW0") (pin "1") (pintype "power_in"))
      (node (ref "LED1") (pin "2") (pinfunction "2_2") (pintype "passive"))
      (node (ref "LED6") (pin "2") (pinfunction "2_2") (pintype "passive"))
    )
    (net (code "273") (name "Net-(CR1-Pad1)") (class "Default")
      (node (ref "CR1") (pin "1") (pinfunction "1_1") (pintype "passive"))
      (node (ref "R97") (pin "2") (pinfunction "2_2") (pintype "passive"))
    )
    (net (code "274") (name "Net-(CR1-Pad3)") (class "Default")
      (node (ref "CR1") (pin "3") (pinfunction "3_3") (pintype "passive"))
      (node (ref "R98") (pin "2") (pinfunction "2_2") (pintype "passive"))
    )
    (net (code "275") (name "Net-(J1-CC1_A)") (class "Default")
      (node (ref "J1") (pin "A5") (pinfunction "CC1_A_A5") (pintype "bidirectional"))
      (node (ref "R62") (pin "2") (pinfunction "2_2") (pintype "passive"))
    )
    (net (code "276") (name "Net-(J1-CC1_B)") (class "Default")
      (node (ref "J1") (pin "B5") (pinfunction "CC1_B_B5") (pintype "bidirectional"))
      (node (ref "R64") (pin "1") (pinfunction "1_1") (pintype "passive"))
    )
    (net (code "277") (name "Net-(J1-SHIELD-PadSH1)") (class "Default")
      (node (ref "J1") (pin "SH1") (pinfunction "SHIELD_SH1") (pintype "passive"))
      (node (ref "J1") (pin "SH2") (pinfunction "SHIELD_SH2") (pintype "passive"))
      (node (ref "J1") (pin "SH3") (pinfunction "SHIELD_SH3") (pintype "passive"))
      (node (ref "J1") (pin "SH4") (pinfunction "SHIELD_SH4") (pintype "passive"))
      (node (ref "R65") (pin "2") (pinfunction "2_2") (pintype "passive"))
    )
    (net (code "278") (name "Net-(JP19-Pad2)") (class "Default")
      (node (ref "JP19") (pin "2") (pinfunction "2_2") (pintype "passive"))
      (node (ref "L2") (pin "2") (pinfunction "2_2") (pintype "passive"))
    )
    (net (code "279") (name "Net-(JP31-Pad2)") (class "Default")
      (node (ref "JP31") (pin "2") (pinfunction "2_2") (pintype "passive"))
      (node (ref "L3") (pin "2") (pinfunction "2_2") (pintype "passive"))
    )
    (net (code "280") (name "Net-(JPW0-Pad2)") (class "Default")
      (node (ref "JPW0") (pin "2") (pintype "power_in"))
      (node (ref "JPW0") (pin "3") (pintype "power_in"))
      (node (ref "L6") (pin "1") (pinfunction "1_1") (pintype "passive"))
    )
    (net (code "281") (name "Net-(LED1-Pad1)") (class "Default")
      (node (ref "LED1") (pin "1") (pinfunction "1_1") (pintype "passive"))
      (node (ref "R5") (pin "2") (pinfunction "2_2") (pintype "passive"))
    )
    (net (code "282") (name "Net-(LED2-Pad1)") (class "Default")
      (node (ref "LED2") (pin "1") (pinfunction "1_1") (pintype "passive"))
      (node (ref "R6") (pin "2") (pinfunction "2_2") (pintype "passive"))
    )
    (net (code "283") (name "Net-(LED3-Pad1)") (class "Default")
      (node (ref "LED3") (pin "1") (pinfunction "1_1") (pintype "passive"))
      (node (ref "R8") (pin "2") (pinfunction "2_2") (pintype "passive"))
    )
    (net (code "284") (name "Net-(LED4-Pad1)") (class "Default")
      (node (ref "LED4") (pin "1") (pinfunction "1_1") (pintype "passive"))
      (node (ref "R9") (pin "2") (pinfunction "2_2") (pintype "passive"))
    )
    (net (code "285") (name "Net-(LED5-Pad1)") (class "Default")
      (node (ref "LED5") (pin "1") (pinfunction "1_1") (pintype "passive"))
      (node (ref "R63") (pin "2") (pinfunction "2_2") (pintype "passive"))
    )
    (net (code "286") (name "Net-(LED6-Pad1)") (class "Default")
      (node (ref "LED6") (pin "1") (pinfunction "1_1") (pintype "passive"))
      (node (ref "R102") (pin "2") (pinfunction "2_2") (pintype "passive"))
    )
    (net (code "287") (name "Net-(LED7-Pad1)") (class "Default")
      (node (ref "LED7") (pin "1") (pinfunction "1_1") (pintype "passive"))
      (node (ref "R103") (pin "2") (pinfunction "2_2") (pintype "passive"))
    )
    (net (code "288") (name "Net-(LED8-Pad1)") (class "Default")
      (node (ref "LED8") (pin "1") (pinfunction "1_1") (pintype "passive"))
      (node (ref "R104") (pin "2") (pinfunction "2_2") (pintype "passive"))
    )
    (net (code "289") (name "Net-(LED9-Pad1)") (class "Default")
      (node (ref "LED9") (pin "1") (pinfunction "1_1") (pintype "passive"))
      (node (ref "R105") (pin "2") (pinfunction "2_2") (pintype "passive"))
    )
    (net (code "290") (name "Net-(Q1-D)") (class "Default")
      (node (ref "Q1") (pin "3") (pinfunction "D_3") (pintype "passive"))
      (node (ref "R105") (pin "1") (pinfunction "1_1") (pintype "passive"))
      (node (ref "R9") (pin "1") (pinfunction "1_1") (pintype "passive"))
    )
    (net (code "291") (name "Net-(R2-TAP)") (class "Default")
      (node (ref "C2") (pin "1") (pinfunction "1_1") (pintype "passive"))
      (node (ref "R1") (pin "1") (pinfunction "1_1") (pintype "passive"))
      (node (ref "R2") (pin "2") (pinfunction "TAP_2") (pintype "passive"))
      (node (ref "U1") (pin "1") (pinfunction "ADJ_1") (pintype "input"))
    )
    (net (code "292") (name "Net-(R4-TAP)") (class "Default")
      (node (ref "C5") (pin "1") (pinfunction "1_1") (pintype "passive"))
      (node (ref "R3") (pin "1") (pinfunction "1_1") (pintype "passive"))
      (node (ref "R4") (pin "2") (pinfunction "TAP_2") (pintype "passive"))
      (node (ref "U2") (pin "1") (pinfunction "ADJ_1") (pintype "input"))
    )
    (net (code "293") (name "Net-(U1-OUT)") (class "Default")
      (node (ref "C3") (pin "1") (pinfunction "1_1") (pintype "passive"))
      (node (ref "JP1") (pin "1") (pinfunction "1_1") (pintype "passive"))
      (node (ref "R1") (pin "2") (pinfunction "2_2") (pintype "passive"))
      (node (ref "U1") (pin "2") (pinfunction "OUT_2") (pintype "power_in"))
      (node (ref "U1") (pin "4") (pinfunction "TAB_4") (pintype "power_in"))
    )
    (net (code "294") (name "Net-(U2-OUT)") (class "Default")
      (node (ref "C6") (pin "1") (pinfunction "1_1") (pintype "passive"))
      (node (ref "JP2") (pin "1") (pinfunction "1_1") (pintype "passive"))
      (node (ref "R3") (pin "2") (pinfunction "2_2") (pintype "passive"))
      (node (ref "U2") (pin "2") (pinfunction "OUT_2") (pintype "power_in"))
      (node (ref "U2") (pin "4") (pinfunction "TAB_4") (pintype "power_in"))
    )
    (net (code "295") (name "Net-(U3A--IN_A)") (class "Default")
      (node (ref "R30") (pin "2") (pinfunction "2_2") (pintype "passive"))
      (node (ref "U3") (pin "1") (pinfunction "OUT_A_1") (pintype "passive"))
      (node (ref "U3") (pin "2") (pinfunction "-IN_A_2") (pintype "tri_state"))
    )
    (net (code "296") (name "Net-(U3B--IN_B)") (class "Default")
      (node (ref "R31") (pin "2") (pinfunction "2_2") (pintype "passive"))
      (node (ref "U3") (pin "6") (pinfunction "-IN_B_6") (pintype "tri_state"))
      (node (ref "U3") (pin "7") (pinfunction "OUT_B_7") (pintype "passive"))
    )
    (net (code "297") (name "Net-(U3C--IN_C)") (class "Default")
      (node (ref "R32") (pin "1") (pinfunction "1_1") (pintype "passive"))
      (node (ref "U3") (pin "8") (pinfunction "OUT_C_8") (pintype "passive"))
      (node (ref "U3") (pin "9") (pinfunction "-IN_C_9") (pintype "tri_state"))
    )
    (net (code "298") (name "Net-(U3D--IN_D)") (class "Default")
      (node (ref "R29") (pin "1") (pinfunction "1_1") (pintype "passive"))
      (node (ref "U3") (pin "13") (pinfunction "-IN_D_13") (pintype "tri_state"))
      (node (ref "U3") (pin "14") (pinfunction "OUT_D_14") (pintype "passive"))
    )
    (net (code "299") (name "Net-(U4-SDO{slash}~{ALARM})") (class "Default")
      (node (ref "R90") (pin "2") (pinfunction "2_2") (pintype "passive"))
      (node (ref "U4") (pin "15") (pinfunction "SDO/~{ALARM}_15") (pintype "output"))
    )
    (net (code "300") (name "Net-(U5-SDO{slash}~{ALARM})") (class "Default")
      (node (ref "R91") (pin "2") (pinfunction "2_2") (pintype "passive"))
      (node (ref "U5") (pin "15") (pinfunction "SDO/~{ALARM}_15") (pintype "output"))
    )
    (net (code "301") (name "Net-(U6-SDO{slash}~{ALARM})") (class "Default")
      (node (ref "R96") (pin "2") (pinfunction "2_2") (pintype "passive"))
      (node (ref "U6") (pin "15") (pinfunction "SDO/~{ALARM}_15") (pintype "output"))
    )
    (net (code "302") (name "Net-(U7-SDO{slash}~{ALARM})") (class "Default")
      (node (ref "R99") (pin "2") (pinfunction "2_2") (pintype "passive"))
      (node (ref "U7") (pin "15") (pinfunction "SDO/~{ALARM}_15") (pintype "output"))
    )
    (net (code "303") (name "Net-(U9A--IN_A)") (class "Default")
      (node (ref "R34") (pin "2") (pinfunction "2_2") (pintype "passive"))
      (node (ref "U9") (pin "1") (pinfunction "OUT_A_1") (pintype "passive"))
      (node (ref "U9") (pin "2") (pinfunction "-IN_A_2") (pintype "tri_state"))
    )
    (net (code "304") (name "Net-(U9B--IN_B)") (class "Default")
      (node (ref "R35") (pin "2") (pinfunction "2_2") (pintype "passive"))
      (node (ref "U9") (pin "6") (pinfunction "-IN_B_6") (pintype "tri_state"))
      (node (ref "U9") (pin "7") (pinfunction "OUT_B_7") (pintype "passive"))
    )
    (net (code "305") (name "Net-(U9C--IN_C)") (class "Default")
      (node (ref "R36") (pin "1") (pinfunction "1_1") (pintype "passive"))
      (node (ref "U9") (pin "8") (pinfunction "OUT_C_8") (pintype "passive"))
      (node (ref "U9") (pin "9") (pinfunction "-IN_C_9") (pintype "tri_state"))
    )
    (net (code "306") (name "Net-(U9D--IN_D)") (class "Default")
      (node (ref "R33") (pin "1") (pinfunction "1_1") (pintype "passive"))
      (node (ref "U9") (pin "13") (pinfunction "-IN_D_13") (pintype "tri_state"))
      (node (ref "U9") (pin "14") (pinfunction "OUT_D_14") (pintype "passive"))
    )
    (net (code "307") (name "Net-(U10A--IN_A)") (class "Default")
      (node (ref "R66") (pin "2") (pinfunction "2_2") (pintype "passive"))
      (node (ref "U10") (pin "1") (pinfunction "OUT_A_1") (pintype "passive"))
      (node (ref "U10") (pin "2") (pinfunction "-IN_A_2") (pintype "tri_state"))
    )
    (net (code "308") (name "Net-(U10B--IN_B)") (class "Default")
      (node (ref "R69") (pin "2") (pinfunction "2_2") (pintype "passive"))
      (node (ref "U10") (pin "6") (pinfunction "-IN_B_6") (pintype "tri_state"))
      (node (ref "U10") (pin "7") (pinfunction "OUT_B_7") (pintype "passive"))
    )
    (net (code "309") (name "Net-(U10C--IN_C)") (class "Default")
      (node (ref "R68") (pin "1") (pinfunction "1_1") (pintype "passive"))
      (node (ref "U10") (pin "8") (pinfunction "OUT_C_8") (pintype "passive"))
      (node (ref "U10") (pin "9") (pinfunction "-IN_C_9") (pintype "tri_state"))
    )
    (net (code "310") (name "Net-(U10D--IN_D)") (class "Default")
      (node (ref "R67") (pin "1") (pinfunction "1_1") (pintype "passive"))
      (node (ref "U10") (pin "13") (pinfunction "-IN_D_13") (pintype "tri_state"))
      (node (ref "U10") (pin "14") (pinfunction "OUT_D_14") (pintype "passive"))
    )
    (net (code "311") (name "Net-(U11-DIR)") (class "Default")
      (node (ref "JP9") (pin "1") (pinfunction "1_1") (pintype "passive"))
      (node (ref "R7") (pin "1") (pinfunction "1_1") (pintype "passive"))
      (node (ref "U11") (pin "2") (pinfunction "DIR_2") (pintype "input"))
    )
    (net (code "312") (name "Net-(U11-VCCA)") (class "Default")
      (node (ref "C52") (pin "2") (pinfunction "2_2") (pintype "passive"))
      (node (ref "JP4") (pin "2") (pinfunction "2_2") (pintype "passive"))
      (node (ref "JP9") (pin "2") (pinfunction "2_2") (pintype "passive"))
      (node (ref "JP_VLT") (pin "2") (pinfunction "2_2") (pintype "passive"))
      (node (ref "U11") (pin "1") (pinfunction "VCCA_1") (pintype "power_in"))
    )
    (net (code "313") (name "Net-(U11-~{OE})") (class "Default")
      (node (ref "R101") (pin "1") (pinfunction "1_1") (pintype "passive"))
      (node (ref "U11") (pin "22") (pinfunction "~{OE}_22") (pintype "input"))
    )
    (net (code "314") (name "Net-(U12-OUT)") (class "Default")
      (node (ref "C54") (pin "2") (pinfunction "2_2") (pintype "passive"))
      (node (ref "JP5") (pin "1") (pinfunction "1_1") (pintype "passive"))
      (node (ref "U12") (pin "5") (pinfunction "OUT_5") (pintype "output"))
    )
    (net (code "315") (name "Net-(U13A-BOOT0)") (class "Default")
      (node (ref "JP28") (pin "1") (pinfunction "1_1") (pintype "passive"))
      (node (ref "R45") (pin "1") (pinfunction "1_1") (pintype "passive"))
      (node (ref "U13") (pin "94") (pinfunction "BOOT0_94") (pintype "input"))
    )
    (net (code "316") (name "Net-(U13A-PD0)") (class "Default")
      (node (ref "R70") (pin "2") (pinfunction "2_2") (pintype "passive"))
      (node (ref "U13") (pin "81") (pinfunction "PD0_81") (pintype "bidirectional"))
    )
    (net (code "317") (name "Net-(U13A-PD1)") (class "Default")
      (node (ref "R71") (pin "2") (pinfunction "2_2") (pintype "passive"))
      (node (ref "U13") (pin "82") (pinfunction "PD1_82") (pintype "bidirectional"))
    )
    (net (code "318") (name "Net-(U13A-PD2)") (class "Default")
      (node (ref "R72") (pin "2") (pinfunction "2_2") (pintype "passive"))
      (node (ref "U13") (pin "83") (pinfunction "PD2_83") (pintype "bidirectional"))
    )
    (net (code "319") (name "Net-(U13A-PD3)") (class "Default")
      (node (ref "R73") (pin "2") (pinfunction "2_2") (pintype "passive"))
      (node (ref "U13") (pin "84") (pinfunction "PD3_84") (pintype "bidirectional"))
    )
    (net (code "320") (name "Net-(U13A-PD4)") (class "Default")
      (node (ref "R74") (pin "2") (pinfunction "2_2") (pintype "passive"))
      (node (ref "U13") (pin "85") (pinfunction "PD4_85") (pintype "bidirectional"))
    )
    (net (code "321") (name "Net-(U13A-PD5)") (class "Default")
      (node (ref "R75") (pin "2") (pinfunction "2_2") (pintype "passive"))
      (node (ref "U13") (pin "86") (pinfunction "PD5_86") (pintype "bidirectional"))
    )
    (net (code "322") (name "Net-(U13A-PD6)") (class "Default")
      (node (ref "R76") (pin "2") (pinfunction "2_2") (pintype "passive"))
      (node (ref "U13") (pin "87") (pinfunction "PD6_87") (pintype "bidirectional"))
    )
    (net (code "323") (name "Net-(U13A-PD7)") (class "Default")
      (node (ref "R77") (pin "2") (pinfunction "2_2") (pintype "passive"))
      (node (ref "U13") (pin "88") (pinfunction "PD7_88") (pintype "bidirectional"))
    )
    (net (code "324") (name "Net-(U13A-PD8)") (class "Default")
      (node (ref "R78") (pin "2") (pinfunction "2_2") (pintype "passive"))
      (node (ref "U13") (pin "55") (pinfunction "PD8_55") (pintype "bidirectional"))
    )
    (net (code "325") (name "Net-(U13A-PD9)") (class "Default")
      (node (ref "R79") (pin "2") (pinfunction "2_2") (pintype "passive"))
      (node (ref "U13") (pin "56") (pinfunction "PD9_56") (pintype "bidirectional"))
    )
    (net (code "326") (name "Net-(U13A-PD12)") (class "Default")
      (node (ref "R81") (pin "2") (pinfunction "2_2") (pintype "passive"))
      (node (ref "U13") (pin "59") (pinfunction "PD12_59") (pintype "bidirectional"))
    )
    (net (code "327") (name "Net-(U13A-PD13)") (class "Default")
      (node (ref "R82") (pin "2") (pinfunction "2_2") (pintype "passive"))
      (node (ref "U13") (pin "60") (pinfunction "PD13_60") (pintype "bidirectional"))
    )
    (net (code "328") (name "Net-(U13A-PD14)") (class "Default")
      (node (ref "R83") (pin "2") (pinfunction "2_2") (pintype "passive"))
      (node (ref "U13") (pin "61") (pinfunction "PD14_61") (pintype "bidirectional"))
    )
    (net (code "329") (name "Net-(U13A-PD15)") (class "Default")
      (node (ref "R84") (pin "2") (pinfunction "2_2") (pintype "passive"))
      (node (ref "U13") (pin "62") (pinfunction "PD15_62") (pintype "bidirectional"))
    )
    (net (code "330") (name "Net-(U13C-VCAP1)") (class "Default")
      (node (ref "C94") (pin "1") (pinfunction "1_1") (pintype "passive"))
      (node (ref "U13") (pin "48") (pinfunction "VCAP1_48") (pintype "power_in"))
    )
    (net (code "331") (name "Net-(U13C-VCAP2)") (class "Default")
      (node (ref "C95") (pin "1") (pinfunction "1_1") (pintype "passive"))
      (node (ref "U13") (pin "73") (pinfunction "VCAP2_73") (pintype "power_in"))
    )
    (net (code "332") (name "Net-(U14-CAP)") (class "Default")
      (node (ref "C63") (pin "2") (pinfunction "2_2") (pintype "passive"))
      (node (ref "U14") (pin "28") (pinfunction "CAP_28") (pintype "passive"))
    )
    (net (code "333") (name "Net-(U14-REFEXT)") (class "Default")
      (node (ref "C61") (pin "2") (pinfunction "2_2") (pintype "passive"))
      (node (ref "U14") (pin "14") (pinfunction "REFEXT_14") (pintype "passive"))
    )
    (net (code "334") (name "Net-(U14-VREFP)") (class "Default")
      (node (ref "C22") (pin "1") (pinfunction "1_1") (pintype "passive"))
      (node (ref "U14") (pin "12") (pinfunction "VREFP_12") (pintype "input"))
    )
    (net (code "335") (name "Net-(U15-CAP)") (class "Default")
      (node (ref "C64") (pin "2") (pinfunction "2_2") (pintype "passive"))
      (node (ref "U15") (pin "28") (pinfunction "CAP_28") (pintype "passive"))
    )
    (net (code "336") (name "Net-(U15-REFEXT)") (class "Default")
      (node (ref "C62") (pin "2") (pinfunction "2_2") (pintype "passive"))
      (node (ref "U15") (pin "14") (pinfunction "REFEXT_14") (pintype "passive"))
    )
    (net (code "337") (name "Net-(U15-VREFP)") (class "Default")
      (node (ref "C23") (pin "1") (pinfunction "1_1") (pintype "passive"))
      (node (ref "U15") (pin "12") (pinfunction "VREFP_12") (pintype "input"))
    )
    (net (code "338") (name "Net-(U16A--IN_A)") (class "Default")
      (node (ref "R47") (pin "2") (pinfunction "2_2") (pintype "passive"))
      (node (ref "U16") (pin "1") (pinfunction "OUT_A_1") (pintype "passive"))
      (node (ref "U16") (pin "2") (pinfunction "-IN_A_2") (pintype "tri_state"))
    )
    (net (code "339") (name "Net-(U16B--IN_B)") (class "Default")
      (node (ref "R48") (pin "2") (pinfunction "2_2") (pintype "passive"))
      (node (ref "U16") (pin "6") (pinfunction "-IN_B_6") (pintype "tri_state"))
      (node (ref "U16") (pin "7") (pinfunction "OUT_B_7") (pintype "passive"))
    )
    (net (code "340") (name "Net-(U16C--IN_C)") (class "Default")
      (node (ref "R49") (pin "1") (pinfunction "1_1") (pintype "passive"))
      (node (ref "U16") (pin "8") (pinfunction "OUT_C_8") (pintype "passive"))
      (node (ref "U16") (pin "9") (pinfunction "-IN_C_9") (pintype "tri_state"))
    )
    (net (code "341") (name "Net-(U16D--IN_D)") (class "Default")
      (node (ref "R46") (pin "1") (pinfunction "1_1") (pintype "passive"))
      (node (ref "U16") (pin "13") (pinfunction "-IN_D_13") (pintype "tri_state"))
      (node (ref "U16") (pin "14") (pinfunction "OUT_D_14") (pintype "passive"))
    )
    (net (code "342") (name "Net-(U17A--IN_A)") (class "Default")
      (node (ref "R51") (pin "2") (pinfunction "2_2") (pintype "passive"))
      (node (ref "U17") (pin "1") (pinfunction "OUT_A_1") (pintype "passive"))
      (node (ref "U17") (pin "2") (pinfunction "-IN_A_2") (pintype "tri_state"))
    )
    (net (code "343") (name "Net-(U17B--IN_B)") (class "Default")
      (node (ref "R52") (pin "2") (pinfunction "2_2") (pintype "passive"))
      (node (ref "U17") (pin "6") (pinfunction "-IN_B_6") (pintype "tri_state"))
      (node (ref "U17") (pin "7") (pinfunction "OUT_B_7") (pintype "passive"))
    )
    (net (code "344") (name "Net-(U17C--IN_C)") (class "Default")
      (node (ref "R53") (pin "1") (pinfunction "1_1") (pintype "passive"))
      (node (ref "U17") (pin "8") (pinfunction "OUT_C_8") (pintype "passive"))
      (node (ref "U17") (pin "9") (pinfunction "-IN_C_9") (pintype "tri_state"))
    )
    (net (code "345") (name "Net-(U17D--IN_D)") (class "Default")
      (node (ref "R50") (pin "1") (pinfunction "1_1") (pintype "passive"))
      (node (ref "U17") (pin "13") (pinfunction "-IN_D_13") (pintype "tri_state"))
      (node (ref "U17") (pin "14") (pinfunction "OUT_D_14") (pintype "passive"))
    )
    (net (code "346") (name "Net-(U19-DIR)") (class "Default")
      (node (ref "JP33") (pin "1") (pinfunction "1_1") (pintype "passive"))
      (node (ref "R80") (pin "1") (pinfunction "1_1") (pintype "passive"))
      (node (ref "U19") (pin "2") (pinfunction "DIR_2") (pintype "input"))
    )
    (net (code "347") (name "Net-(U19-VCCA)") (class "Default")
      (node (ref "C119") (pin "2") (pinfunction "2_2") (pintype "passive"))
      (node (ref "JP32") (pin "2") (pinfunction "2_2") (pintype "passive"))
      (node (ref "JP33") (pin "2") (pinfunction "2_2") (pintype "passive"))
      (node (ref "JP_VLT1") (pin "2") (pinfunction "2_2") (pintype "passive"))
      (node (ref "U19") (pin "1") (pinfunction "VCCA_1") (pintype "power_in"))
    )
    (net (code "348") (name "Net-(U19-~{OE})") (class "Default")
      (node (ref "R100") (pin "1") (pinfunction "1_1") (pintype "passive"))
      (node (ref "U19") (pin "22") (pinfunction "~{OE}_22") (pintype "input"))
    )
    (net (code "349") (name "unconnected-(B0-MH1-Pad69)") (class "Default")
      (node (ref "B0") (pin "69") (pinfunction "MH1_69") (pintype "passive"))
    )
    (net (code "350") (name "unconnected-(B0-MH2-Pad70)") (class "Default")
      (node (ref "B0") (pin "70") (pinfunction "MH2_70") (pintype "passive"))
    )
    (net (code "351") (name "unconnected-(B0-Pad20)") (class "Default")
      (node (ref "B0") (pin "20") (pinfunction "20_20") (pintype "passive"))
    )
    (net (code "352") (name "unconnected-(HD0-Pad19)") (class "Default")
      (node (ref "HD0") (pin "19") (pinfunction "19_19") (pintype "passive"))
    )
    (net (code "353") (name "unconnected-(HD0-Pad22)") (class "Default")
      (node (ref "HD0") (pin "22") (pinfunction "22_22") (pintype "passive"))
    )
    (net (code "354") (name "unconnected-(HD1-Pad1)") (class "Default")
      (node (ref "HD1") (pin "1") (pinfunction "1_1") (pintype "passive"))
    )
    (net (code "355") (name "unconnected-(HD1-Pad2)") (class "Default")
      (node (ref "HD1") (pin "2") (pinfunction "2_2") (pintype "passive"))
    )
    (net (code "356") (name "unconnected-(HD1-Pad3)") (class "Default")
      (node (ref "HD1") (pin "3") (pinfunction "3_3") (pintype "passive"))
    )
    (net (code "357") (name "unconnected-(HD1-Pad4)") (class "Default")
      (node (ref "HD1") (pin "4") (pinfunction "4_4") (pintype "passive"))
    )
    (net (code "358") (name "unconnected-(HD2-Pad1)") (class "Default")
      (node (ref "HD2") (pin "1") (pinfunction "1_1") (pintype "passive"))
    )
    (net (code "359") (name "unconnected-(HD2-Pad2)") (class "Default")
      (node (ref "HD2") (pin "2") (pinfunction "2_2") (pintype "passive"))
    )
    (net (code "360") (name "unconnected-(HD2-Pad3)") (class "Default")
      (node (ref "HD2") (pin "3") (pinfunction "3_3") (pintype "passive"))
    )
    (net (code "361") (name "unconnected-(HD2-Pad5)") (class "Default")
      (node (ref "HD2") (pin "5") (pinfunction "5_5") (pintype "passive"))
    )
    (net (code "362") (name "unconnected-(HD2-Pad6)") (class "Default")
      (node (ref "HD2") (pin "6") (pinfunction "6_6") (pintype "passive"))
    )
    (net (code "363") (name "unconnected-(HD2-Pad8)") (class "Default")
      (node (ref "HD2") (pin "8") (pinfunction "8_8") (pintype "passive"))
    )
    (net (code "364") (name "unconnected-(J1-SBU1-PadA8)") (class "Default")
      (node (ref "J1") (pin "A8") (pinfunction "SBU1_A8") (pintype "bidirectional"))
    )
    (net (code "365") (name "unconnected-(J1-SBU2-PadB8)") (class "Default")
      (node (ref "J1") (pin "B8") (pinfunction "SBU2_B8") (pintype "bidirectional"))
    )
    (net (code "366") (name "unconnected-(R2-TOP-Pad1)") (class "Default")
      (node (ref "R2") (pin "1") (pinfunction "TOP_1") (pintype "passive"))
    )
    (net (code "367") (name "unconnected-(R4-TOP-Pad1)") (class "Default")
      (node (ref "R4") (pin "1") (pinfunction "TOP_1") (pintype "passive"))
    )
    (net (code "368") (name "unconnected-(S1-COM_1-Pad3)") (class "Default")
      (node (ref "S1") (pin "3") (pinfunction "COM_1_3") (pintype "bidirectional"))
    )
    (net (code "369") (name "unconnected-(S1-NO_2-Pad2)") (class "Default")
      (node (ref "S1") (pin "2") (pinfunction "NO_2_2") (pintype "bidirectional"))
    )
    (net (code "370") (name "unconnected-(U12-N{slash}C-Pad4)") (class "Default")
      (node (ref "U12") (pin "4") (pinfunction "N/C_4") (pintype "passive"))
    )
    (net (code "371") (name "unconnected-(U13A-PA0-WKUP-Pad22)") (class "Default")
      (node (ref "U13") (pin "22") (pinfunction "PA0-WKUP_22") (pintype "bidirectional"))
    )
    (net (code "372") (name "unconnected-(U13A-PA5-Pad29)") (class "Default")
      (node (ref "U13") (pin "29") (pinfunction "PA5_29") (pintype "bidirectional"))
    )
    (net (code "373") (name "unconnected-(U13A-PA6-Pad30)") (class "Default")
      (node (ref "U13") (pin "30") (pinfunction "PA6_30") (pintype "bidirectional"))
    )
    (net (code "374") (name "unconnected-(U13A-PA7-Pad31)") (class "Default")
      (node (ref "U13") (pin "31") (pinfunction "PA7_31") (pintype "bidirectional"))
    )
    (net (code "375") (name "unconnected-(U13A-PA9-Pad68)") (class "Default")
      (node (ref "U13") (pin "68") (pinfunction "PA9_68") (pintype "bidirectional"))
    )
    (net (code "376") (name "unconnected-(U13A-PA10-Pad69)") (class "Default")
      (node (ref "U13") (pin "69") (pinfunction "PA10_69") (pintype "bidirectional"))
    )
    (net (code "377") (name "unconnected-(U13A-PA15-Pad77)") (class "Default")
      (node (ref "U13") (pin "77") (pinfunction "PA15_77") (pintype "bidirectional"))
    )
    (net (code "378") (name "unconnected-(U13A-PB0-Pad34)") (class "Default")
      (node (ref "U13") (pin "34") (pinfunction "PB0_34") (pintype "bidirectional"))
    )
    (net (code "379") (name "unconnected-(U13A-PB1-Pad35)") (class "Default")
      (node (ref "U13") (pin "35") (pinfunction "PB1_35") (pintype "bidirectional"))
    )
    (net (code "380") (name "unconnected-(U13A-PB2-Pad36)") (class "Default")
      (node (ref "U13") (pin "36") (pinfunction "PB2_36") (pintype "bidirectional"))
    )
    (net (code "381") (name "unconnected-(U13A-PB4-Pad90)") (class "Default")
      (node (ref "U13") (pin "90") (pinfunction "PB4_90") (pintype "bidirectional"))
    )
    (net (code "382") (name "unconnected-(U13A-PB5-Pad91)") (class "Default")
      (node (ref "U13") (pin "91") (pinfunction "PB5_91") (pintype "bidirectional"))
    )
    (net (code "383") (name "unconnected-(U13A-PB6-Pad92)") (class "Default")
      (node (ref "U13") (pin "92") (pinfunction "PB6_92") (pintype "bidirectional"))
    )
    (net (code "384") (name "unconnected-(U13A-PB7-Pad93)") (class "Default")
      (node (ref "U13") (pin "93") (pinfunction "PB7_93") (pintype "bidirectional"))
    )
    (net (code "385") (name "unconnected-(U13A-PB8-Pad95)") (class "Default")
      (node (ref "U13") (pin "95") (pinfunction "PB8_95") (pintype "bidirectional"))
    )
    (net (code "386") (name "unconnected-(U13A-PB9-Pad96)") (class "Default")
      (node (ref "U13") (pin "96") (pinfunction "PB9_96") (pintype "bidirectional"))
    )
    (net (code "387") (name "unconnected-(U13A-PB10-Pad46)") (class "Default")
      (node (ref "U13") (pin "46") (pinfunction "PB10_46") (pintype "bidirectional"))
    )
    (net (code "388") (name "unconnected-(U13A-PC0-Pad15)") (class "Default")
      (node (ref "U13") (pin "15") (pinfunction "PC0_15") (pintype "bidirectional"))
    )
    (net (code "389") (name "unconnected-(U13A-PC1-Pad16)") (class "Default")
      (node (ref "U13") (pin "16") (pinfunction "PC1_16") (pintype "bidirectional"))
    )
    (net (code "390") (name "unconnected-(U13A-PC2_C-Pad17)") (class "Default")
      (node (ref "U13") (pin "17") (pinfunction "PC2_C_17") (pintype "bidirectional"))
    )
    (net (code "391") (name "unconnected-(U13A-PC3_C-Pad18)") (class "Default")
      (node (ref "U13") (pin "18") (pinfunction "PC3_C_18") (pintype "bidirectional"))
    )
    (net (code "392") (name "unconnected-(U13A-PC4-Pad32)") (class "Default")
      (node (ref "U13") (pin "32") (pinfunction "PC4_32") (pintype "bidirectional"))
    )
    (net (code "393") (name "unconnected-(U13A-PC5-Pad33)") (class "Default")
      (node (ref "U13") (pin "33") (pinfunction "PC5_33") (pintype "bidirectional"))
    )
    (net (code "394") (name "unconnected-(U13A-PC6-Pad63)") (class "Default")
      (node (ref "U13") (pin "63") (pinfunction "PC6_63") (pintype "bidirectional"))
    )
    (net (code "395") (name "unconnected-(U13A-PC7-Pad64)") (class "Default")
      (node (ref "U13") (pin "64") (pinfunction "PC7_64") (pintype "bidirectional"))
    )
    (net (code "396") (name "unconnected-(U13A-PC8-Pad65)") (class "Default")
      (node (ref "U13") (pin "65") (pinfunction "PC8_65") (pintype "bidirectional"))
    )
    (net (code "397") (name "unconnected-(U13A-PC9-Pad66)") (class "Default")
      (node (ref "U13") (pin "66") (pinfunction "PC9_66") (pintype "bidirectional"))
    )
    (net (code "398") (name "unconnected-(U13A-PC10-Pad78)") (class "Default")
      (node (ref "U13") (pin "78") (pinfunction "PC10_78") (pintype "bidirectional"))
    )
    (net (code "399") (name "unconnected-(U13A-PC11-Pad79)") (class "Default")
      (node (ref "U13") (pin "79") (pinfunction "PC11_79") (pintype "bidirectional"))
    )
    (net (code "400") (name "unconnected-(U13A-PC12-Pad80)") (class "Default")
      (node (ref "U13") (pin "80") (pinfunction "PC12_80") (pintype "bidirectional"))
    )
    (net (code "401") (name "unconnected-(U13A-PC13-Pad7)") (class "Default")
      (node (ref "U13") (pin "7") (pinfunction "PC13_7") (pintype "bidirectional"))
    )
    (net (code "402") (name "unconnected-(U13A-PC14-OSC32_IN-Pad8)") (class "Default")
      (node (ref "U13") (pin "8") (pinfunction "PC14-OSC32_IN_8") (pintype "bidirectional"))
    )
    (net (code "403") (name "unconnected-(U13A-PC15-OSC32_OUT-Pad9)") (class "Default")
      (node (ref "U13") (pin "9") (pinfunction "PC15-OSC32_OUT_9") (pintype "bidirectional"))
    )
    (net (code "404") (name "unconnected-(U13A-PD10-Pad57)") (class "Default")
      (node (ref "U13") (pin "57") (pinfunction "PD10_57") (pintype "bidirectional"))
    )
    (net (code "405") (name "unconnected-(U13A-PD11-Pad58)") (class "Default")
      (node (ref "U13") (pin "58") (pinfunction "PD11_58") (pintype "bidirectional"))
    )
    (net (code "406") (name "unconnected-(U13B-PE6-Pad5)") (class "Default")
      (node (ref "U13") (pin "5") (pinfunction "PE6_5") (pintype "bidirectional"))
    )
    (net (code "407") (name "unconnected-(U13B-PE13-Pad43)") (class "Default")
      (node (ref "U13") (pin "43") (pinfunction "PE13_43") (pintype "bidirectional"))
    )
    (net (code "408") (name "unconnected-(U13B-PE15-Pad45)") (class "Default")
      (node (ref "U13") (pin "45") (pinfunction "PE15_45") (pintype "bidirectional"))
    )
    (net (code "409") (name "unconnected-(U14-DONE_N-Pad18)") (class "Default")
      (node (ref "U14") (pin "18") (pinfunction "DONE_N_18") (pintype "output"))
    )
    (net (code "410") (name "unconnected-(U14-NC-Pad24)") (class "Default")
      (node (ref "U14") (pin "24") (pinfunction "NC_24") (pintype "passive+no_connect"))
    )
    (net (code "411") (name "unconnected-(U14-XTAL2-Pad26)") (class "Default")
      (node (ref "U14") (pin "26") (pinfunction "XTAL2_26") (pintype "output+no_connect"))
    )
    (net (code "412") (name "unconnected-(U15-DONE_N-Pad18)") (class "Default")
      (node (ref "U15") (pin "18") (pinfunction "DONE_N_18") (pintype "output"))
    )
    (net (code "413") (name "unconnected-(U15-NC-Pad24)") (class "Default")
      (node (ref "U15") (pin "24") (pinfunction "NC_24") (pintype "passive+no_connect"))
    )
    (net (code "414") (name "unconnected-(U15-XTAL2-Pad26)") (class "Default")
      (node (ref "U15") (pin "26") (pinfunction "XTAL2_26") (pintype "output+no_connect"))
    )
    (net (code "415") (name "unconnected-(U18-DNC-Pad8)") (class "Default")
      (node (ref "U18") (pin "8") (pinfunction "DNC_8") (pintype "passive"))
    )
    (net (code "416") (name "unconnected-(U18-NIC-Pad1)") (class "Default")
      (node (ref "U18") (pin "1") (pinfunction "NIC_1") (pintype "passive"))
    )
    (net (code "417") (name "unconnected-(U18-NIC-Pad3)") (class "Default")
      (node (ref "U18") (pin "3") (pinfunction "NIC_3") (pintype "passive"))
    )
    (net (code "418") (name "unconnected-(U18-NIC-Pad5)") (class "Default")
      (node (ref "U18") (pin "5") (pinfunction "NIC_5") (pintype "passive"))
    )
    (net (code "419") (name "unconnected-(U18-NIC-Pad7)") (class "Default")
      (node (ref "U18") (pin "7") (pinfunction "NIC_7") (pintype "passive"))
    )
  )
)
